# PX4FMUv2_3.net
KiCad netlist of a schematic drawn in EAGLE
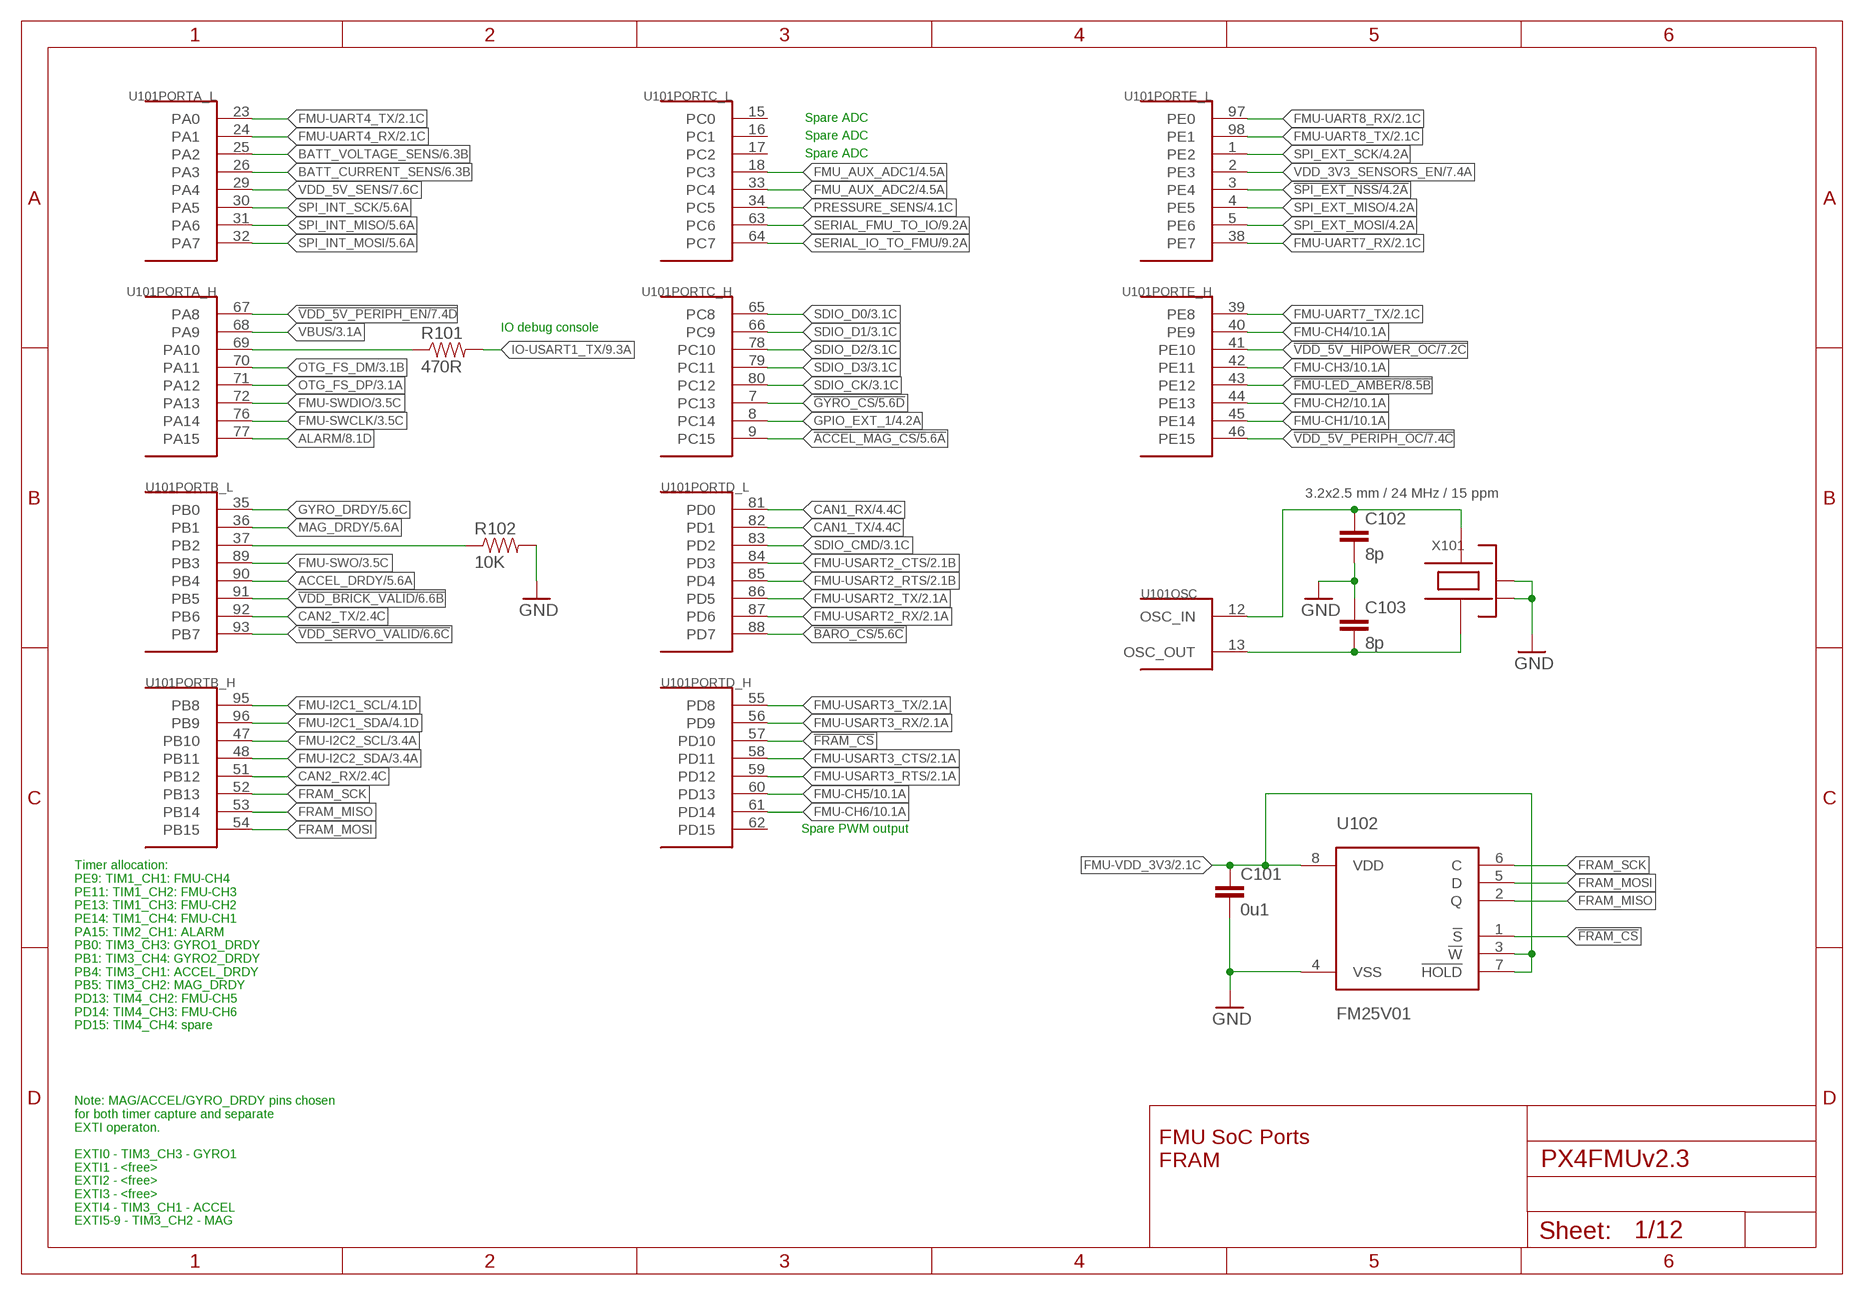
[diagram p0: schematic, sheet 1]
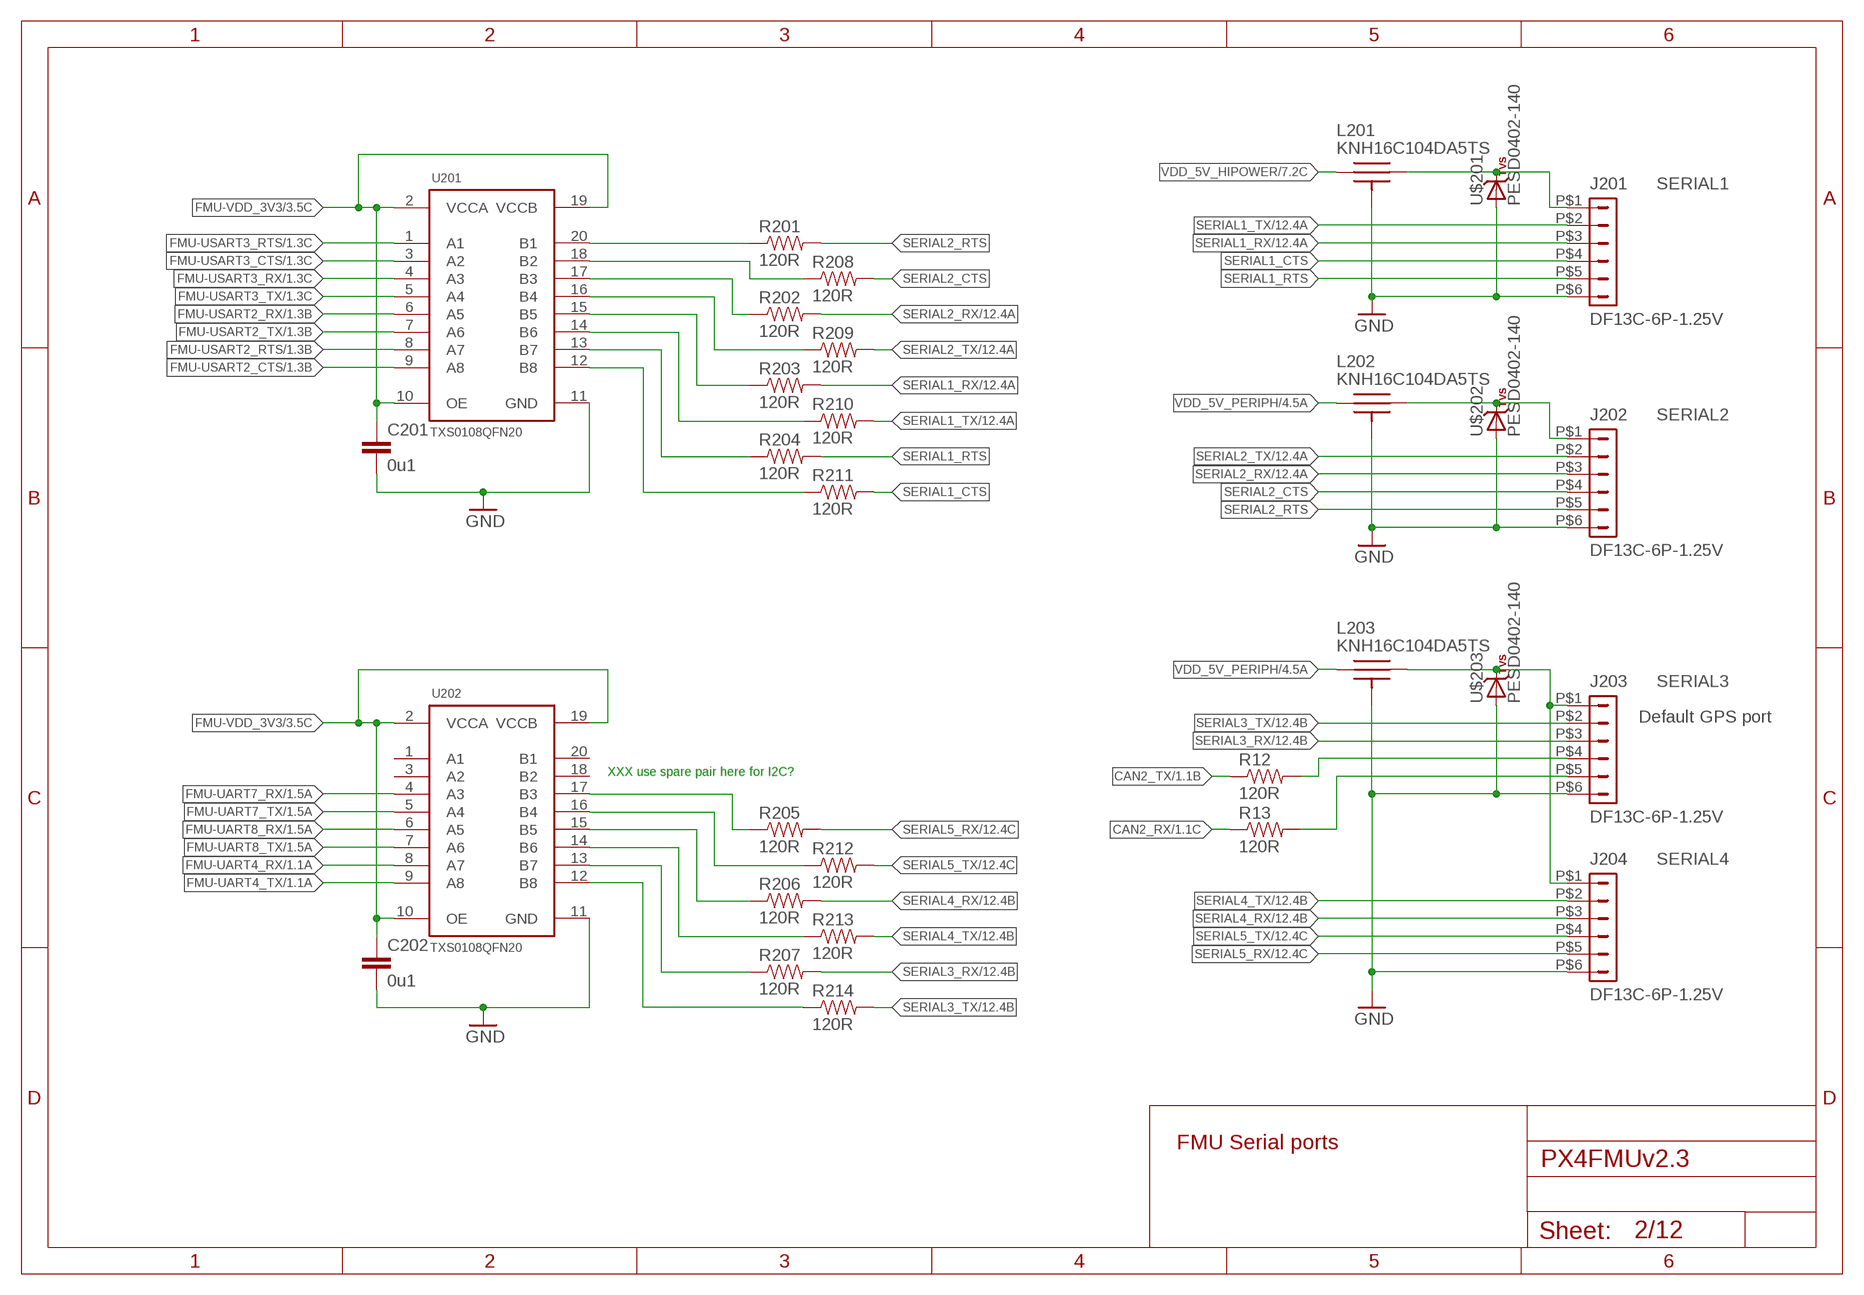
[diagram p1: schematic, sheet 2]
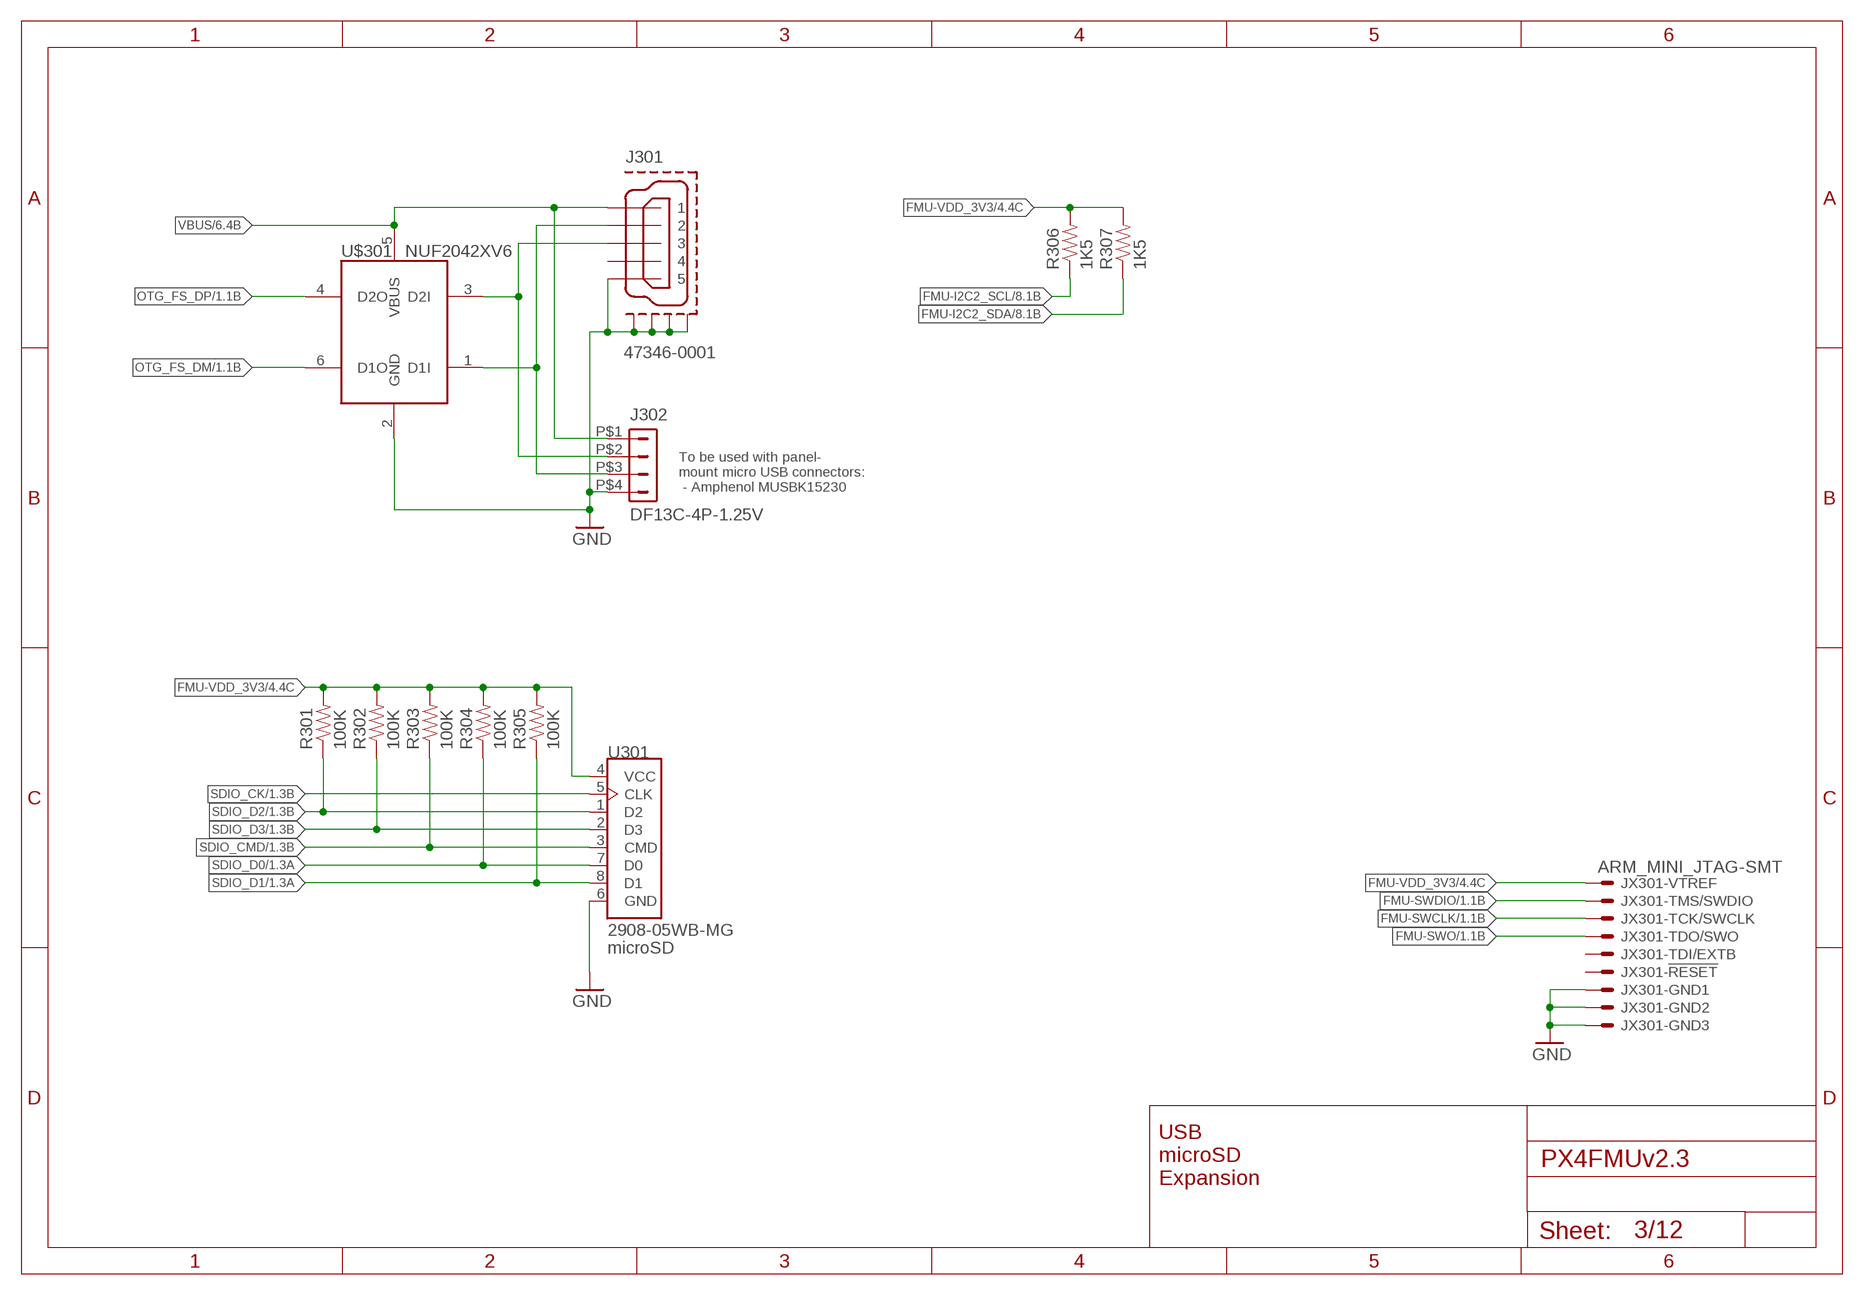
[diagram p2: schematic, sheet 3]
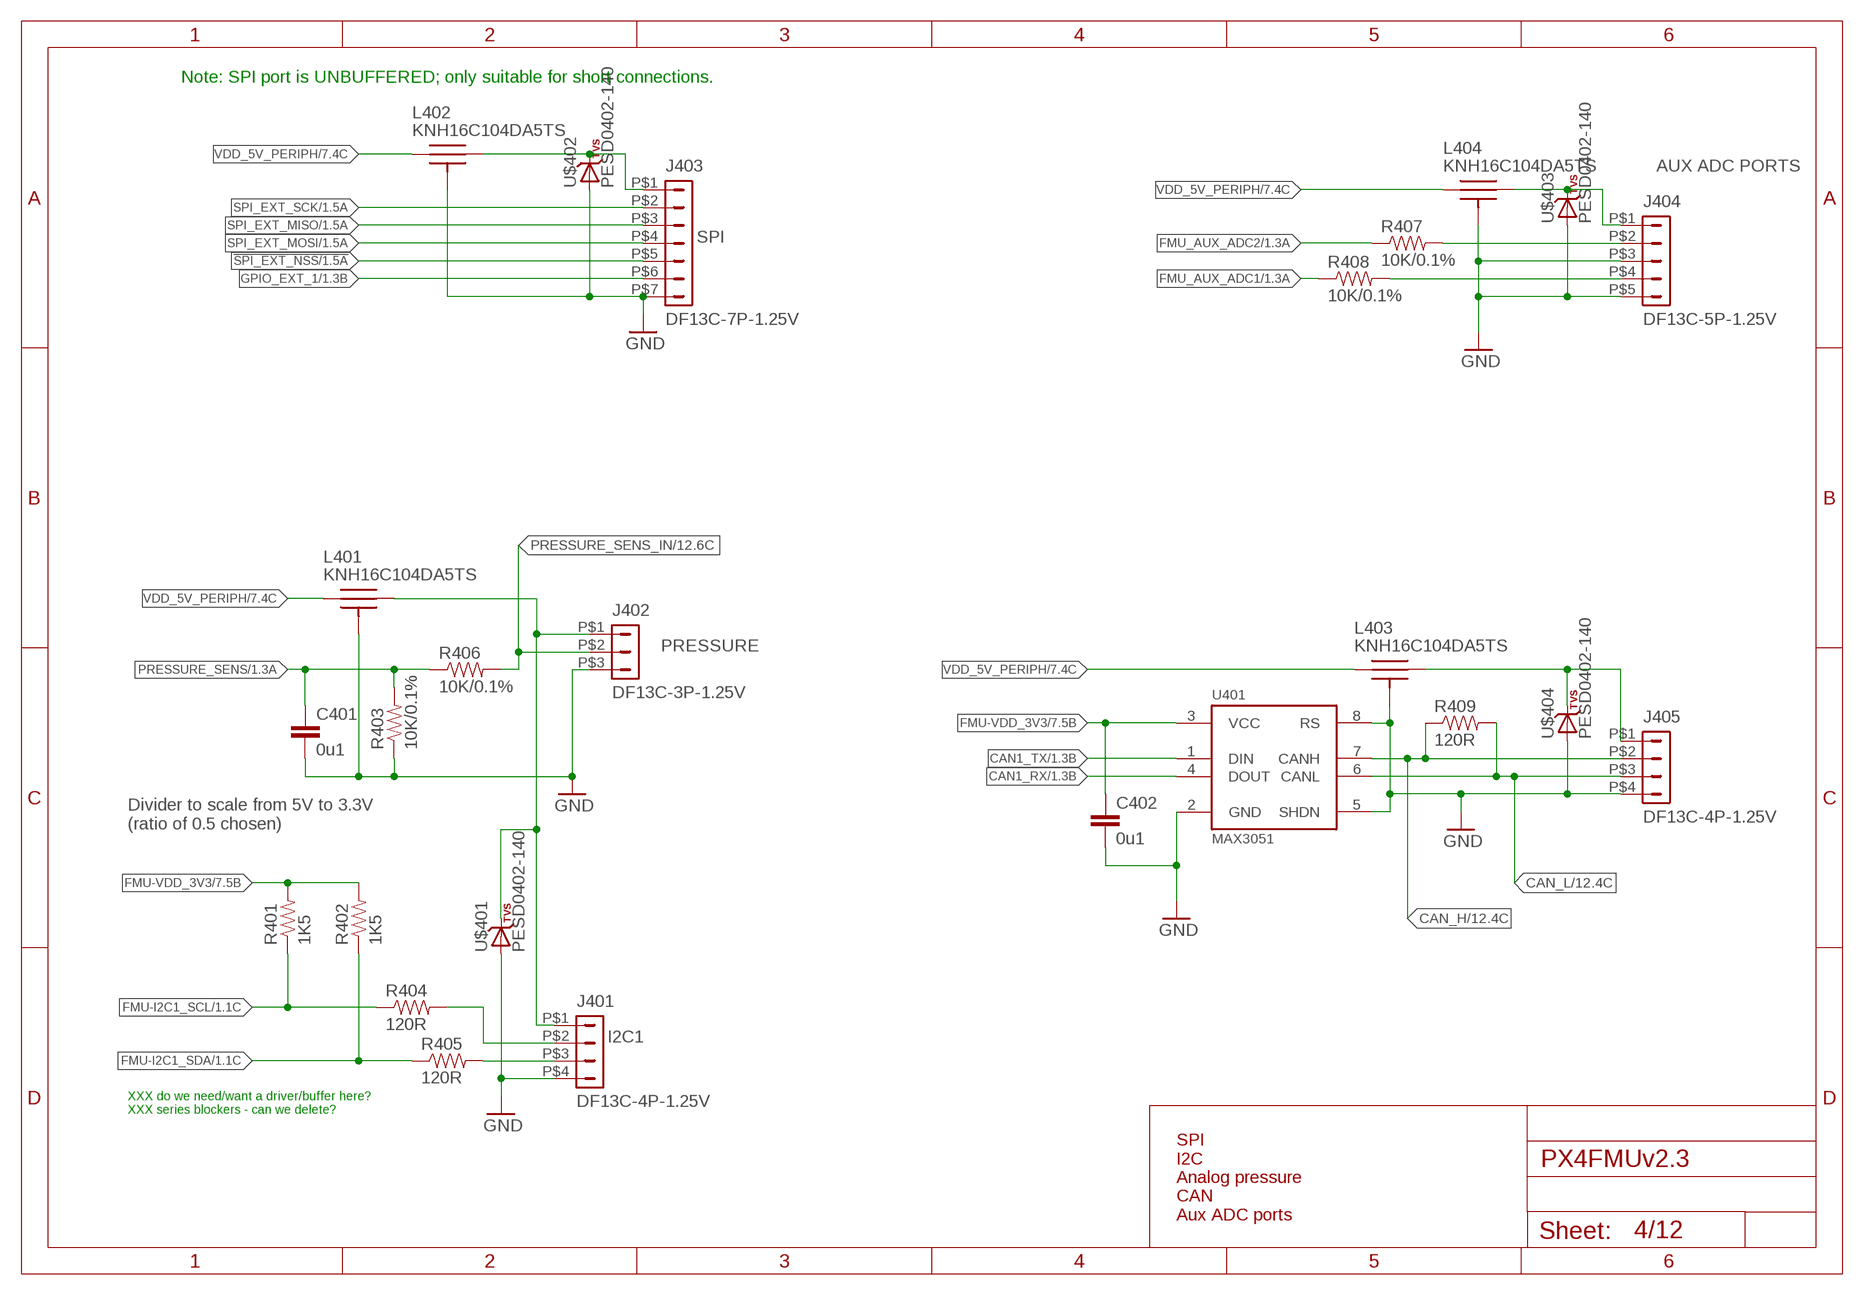
[diagram p3: schematic, sheet 4]
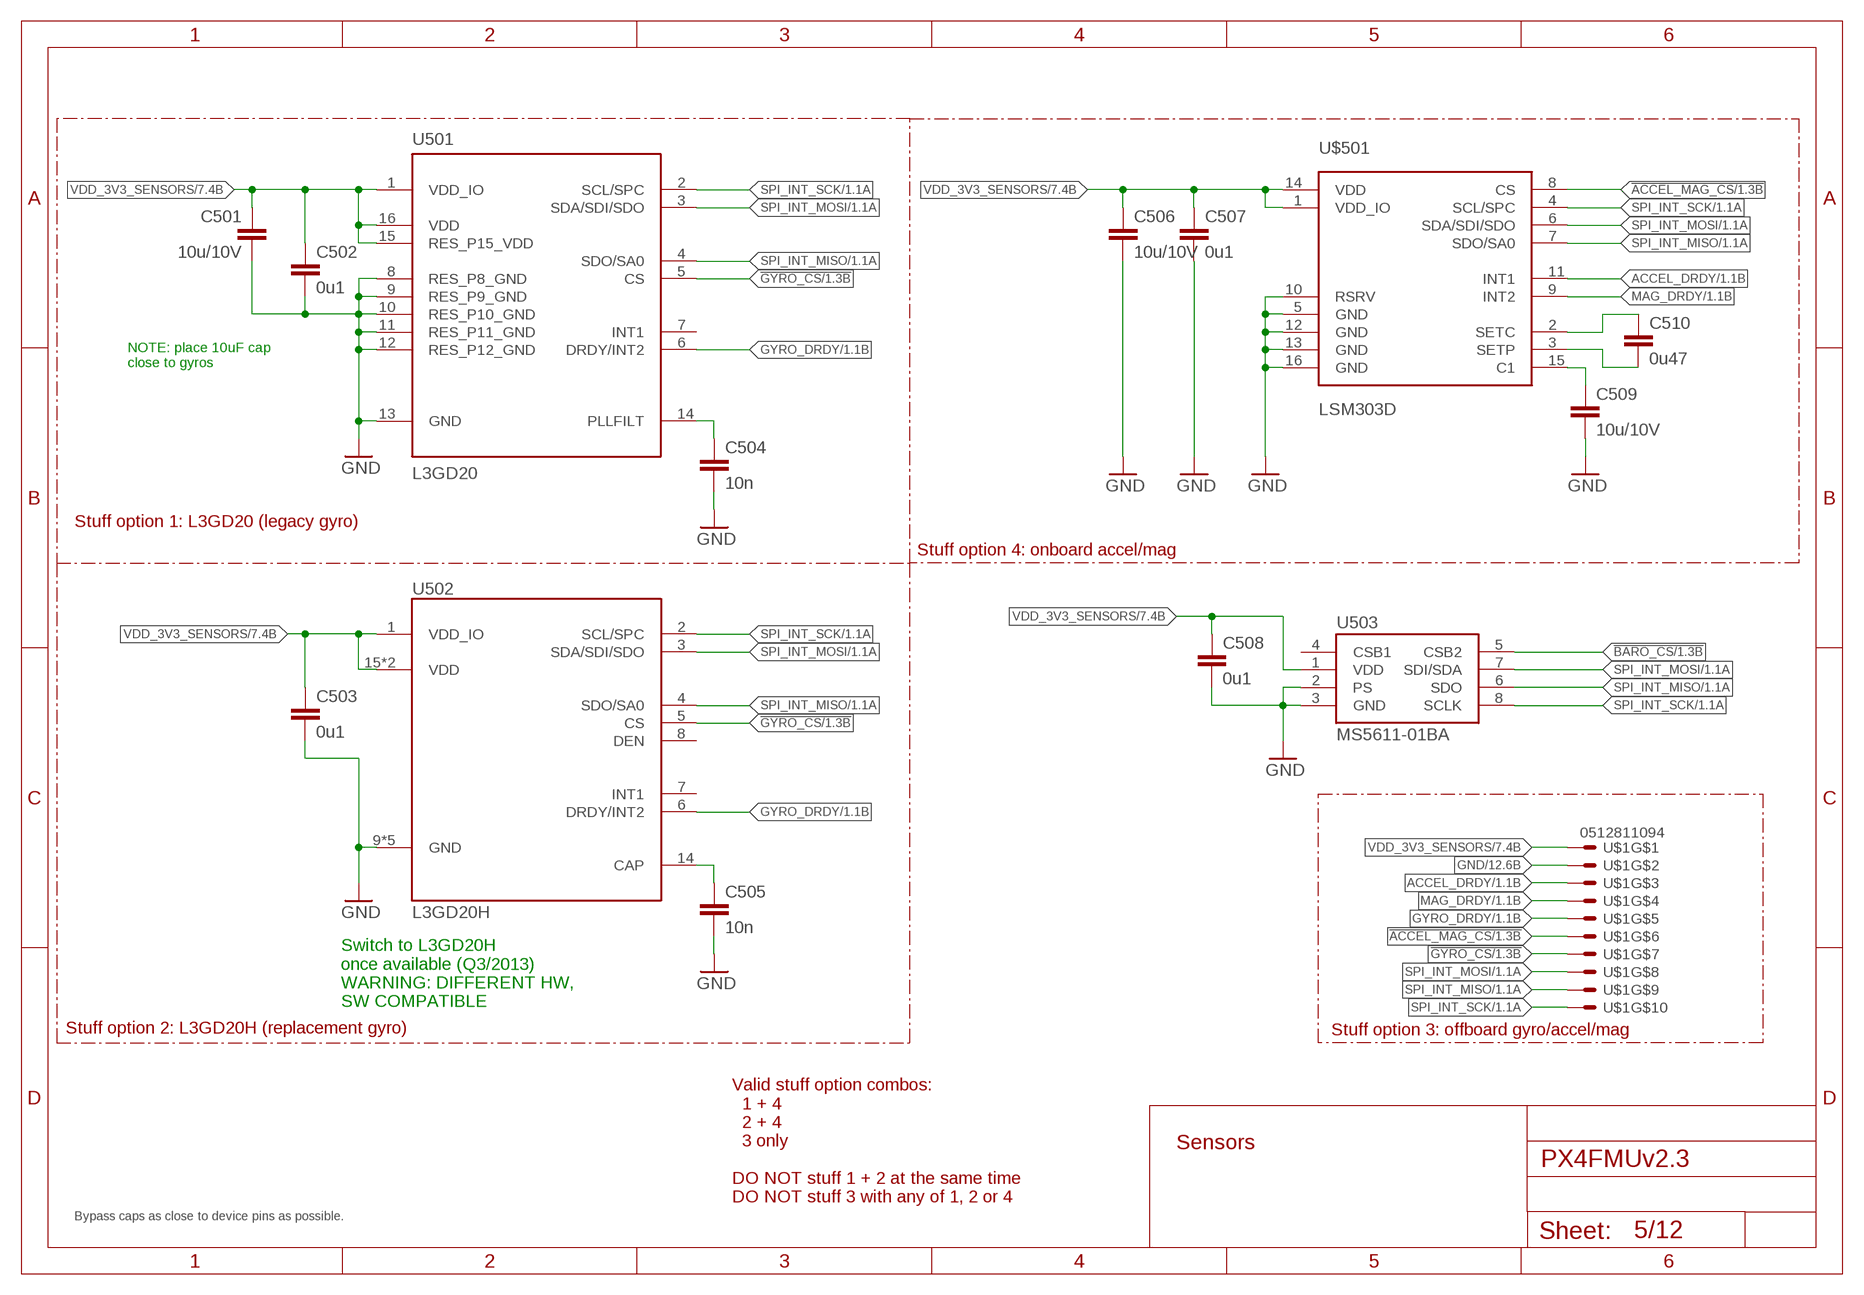
[diagram p4: schematic, sheet 5]
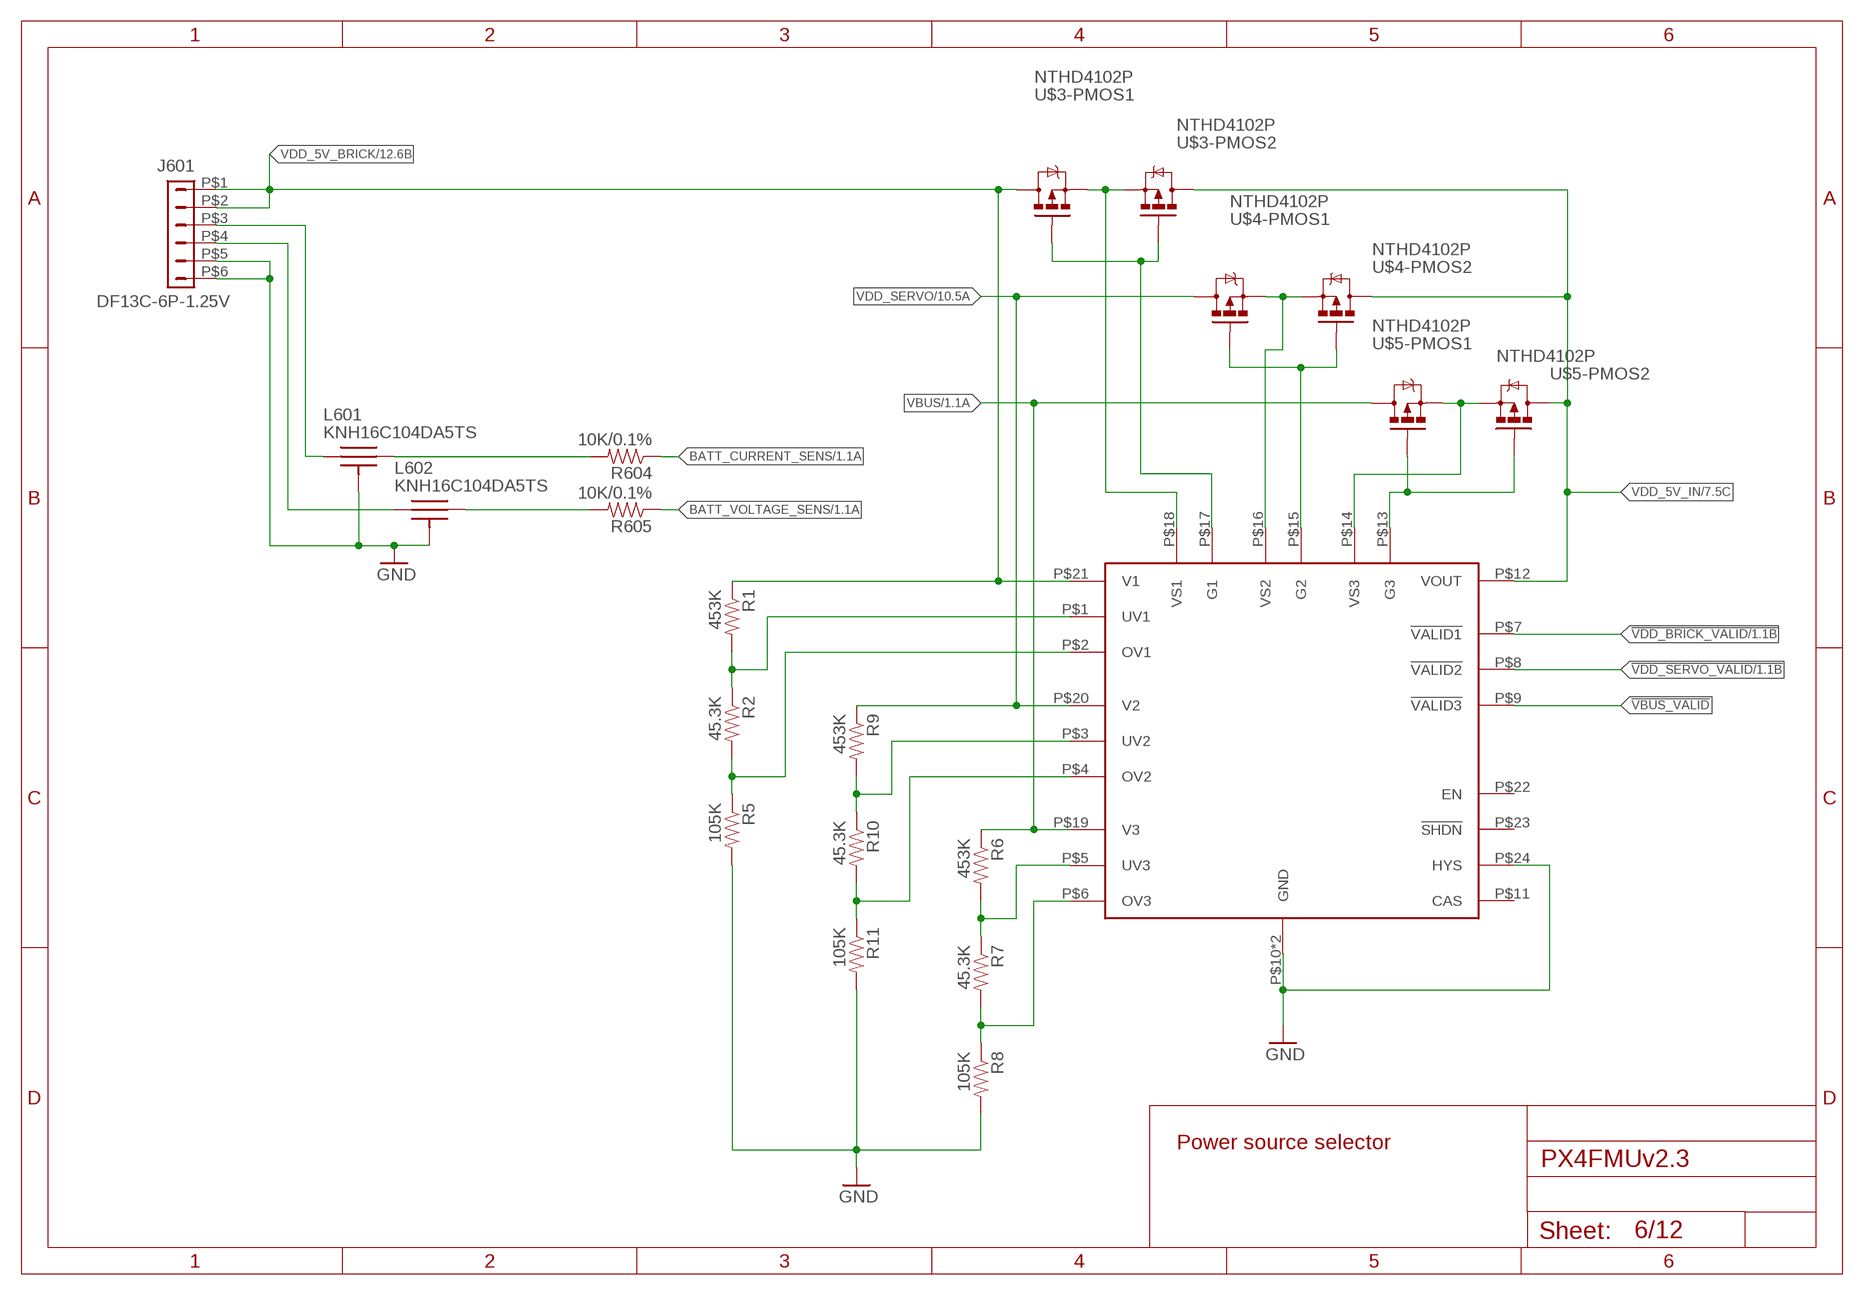
[diagram p5: schematic, sheet 6]
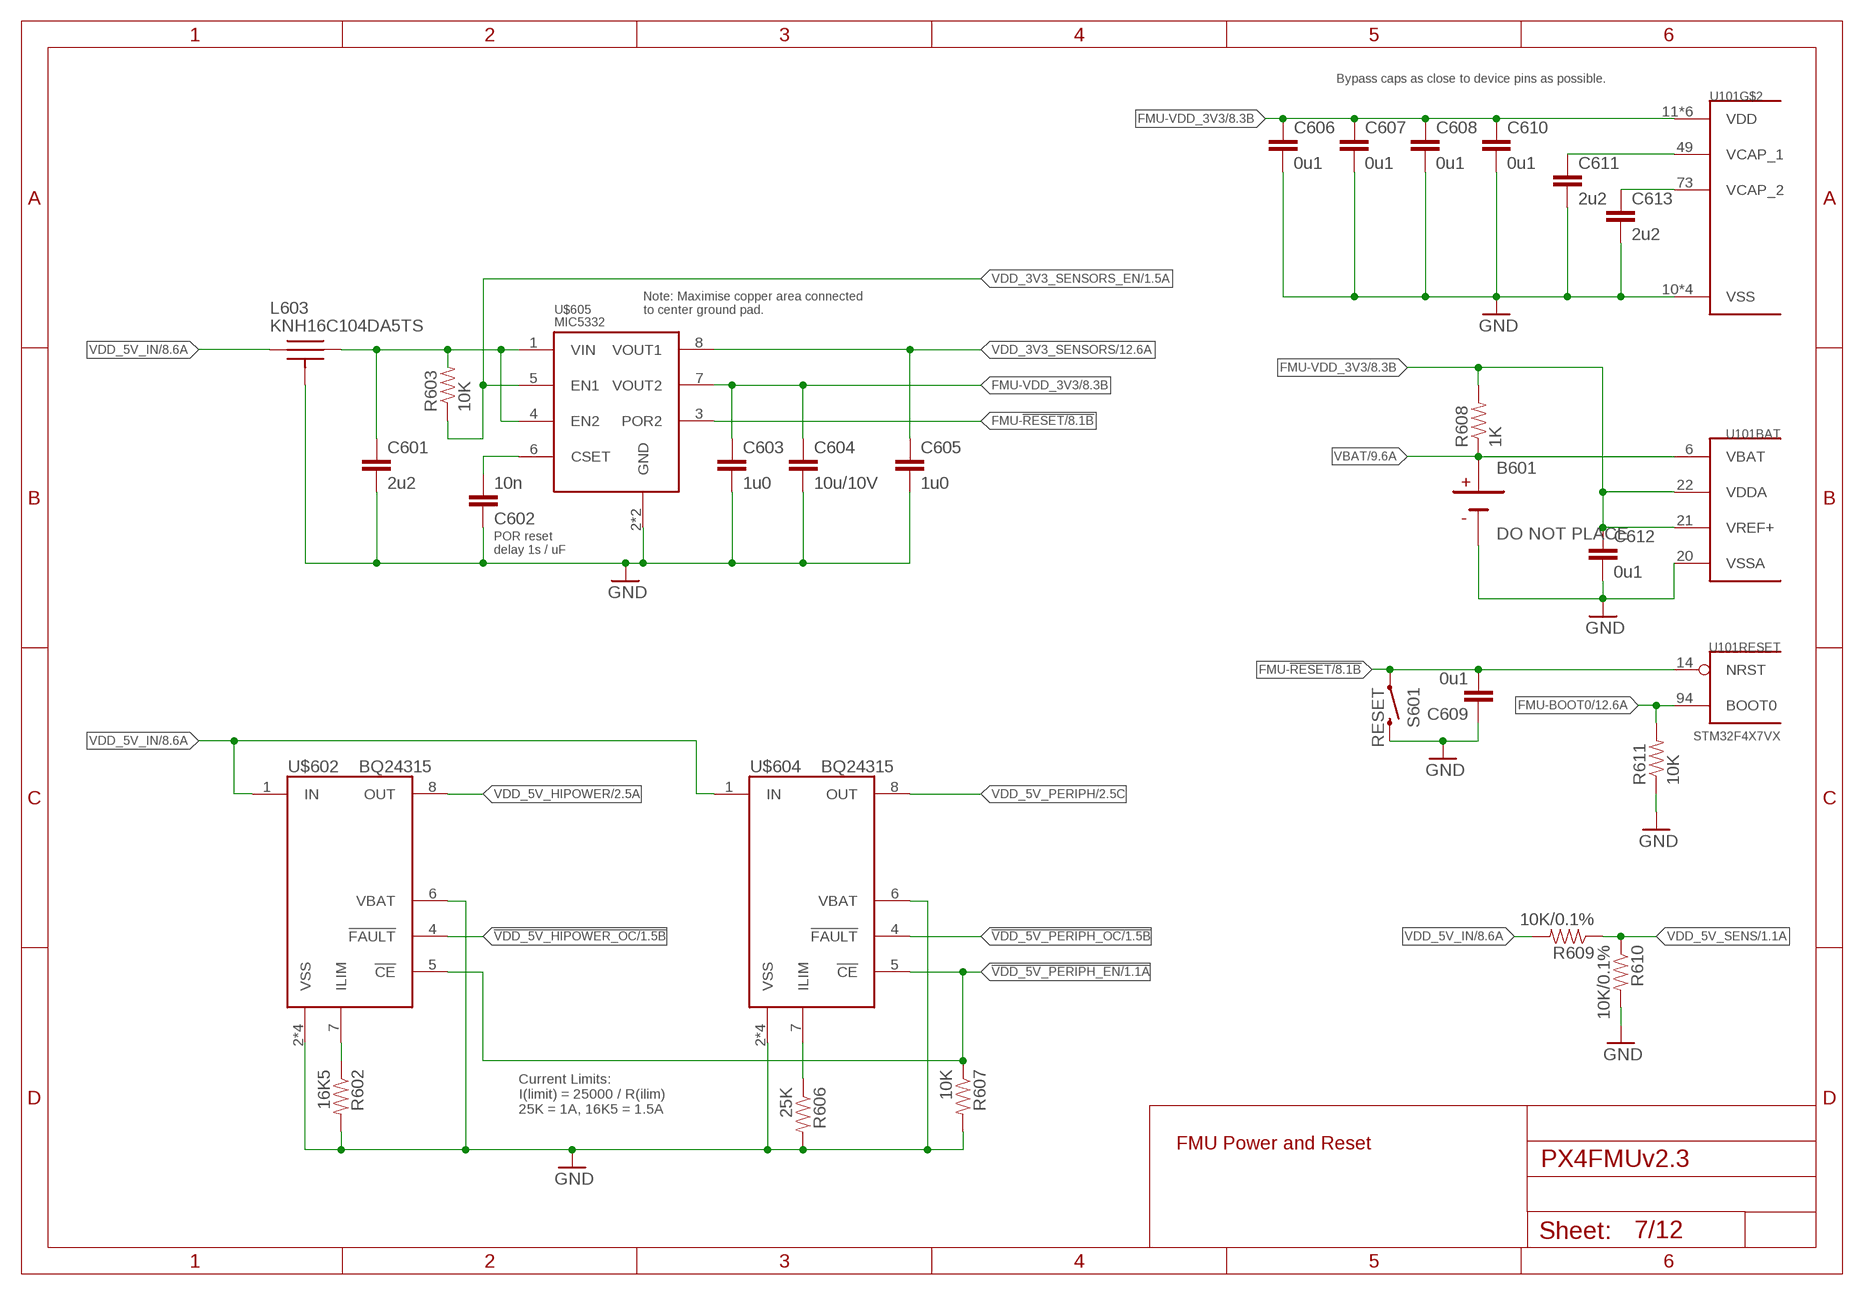
[diagram p6: schematic, sheet 7]
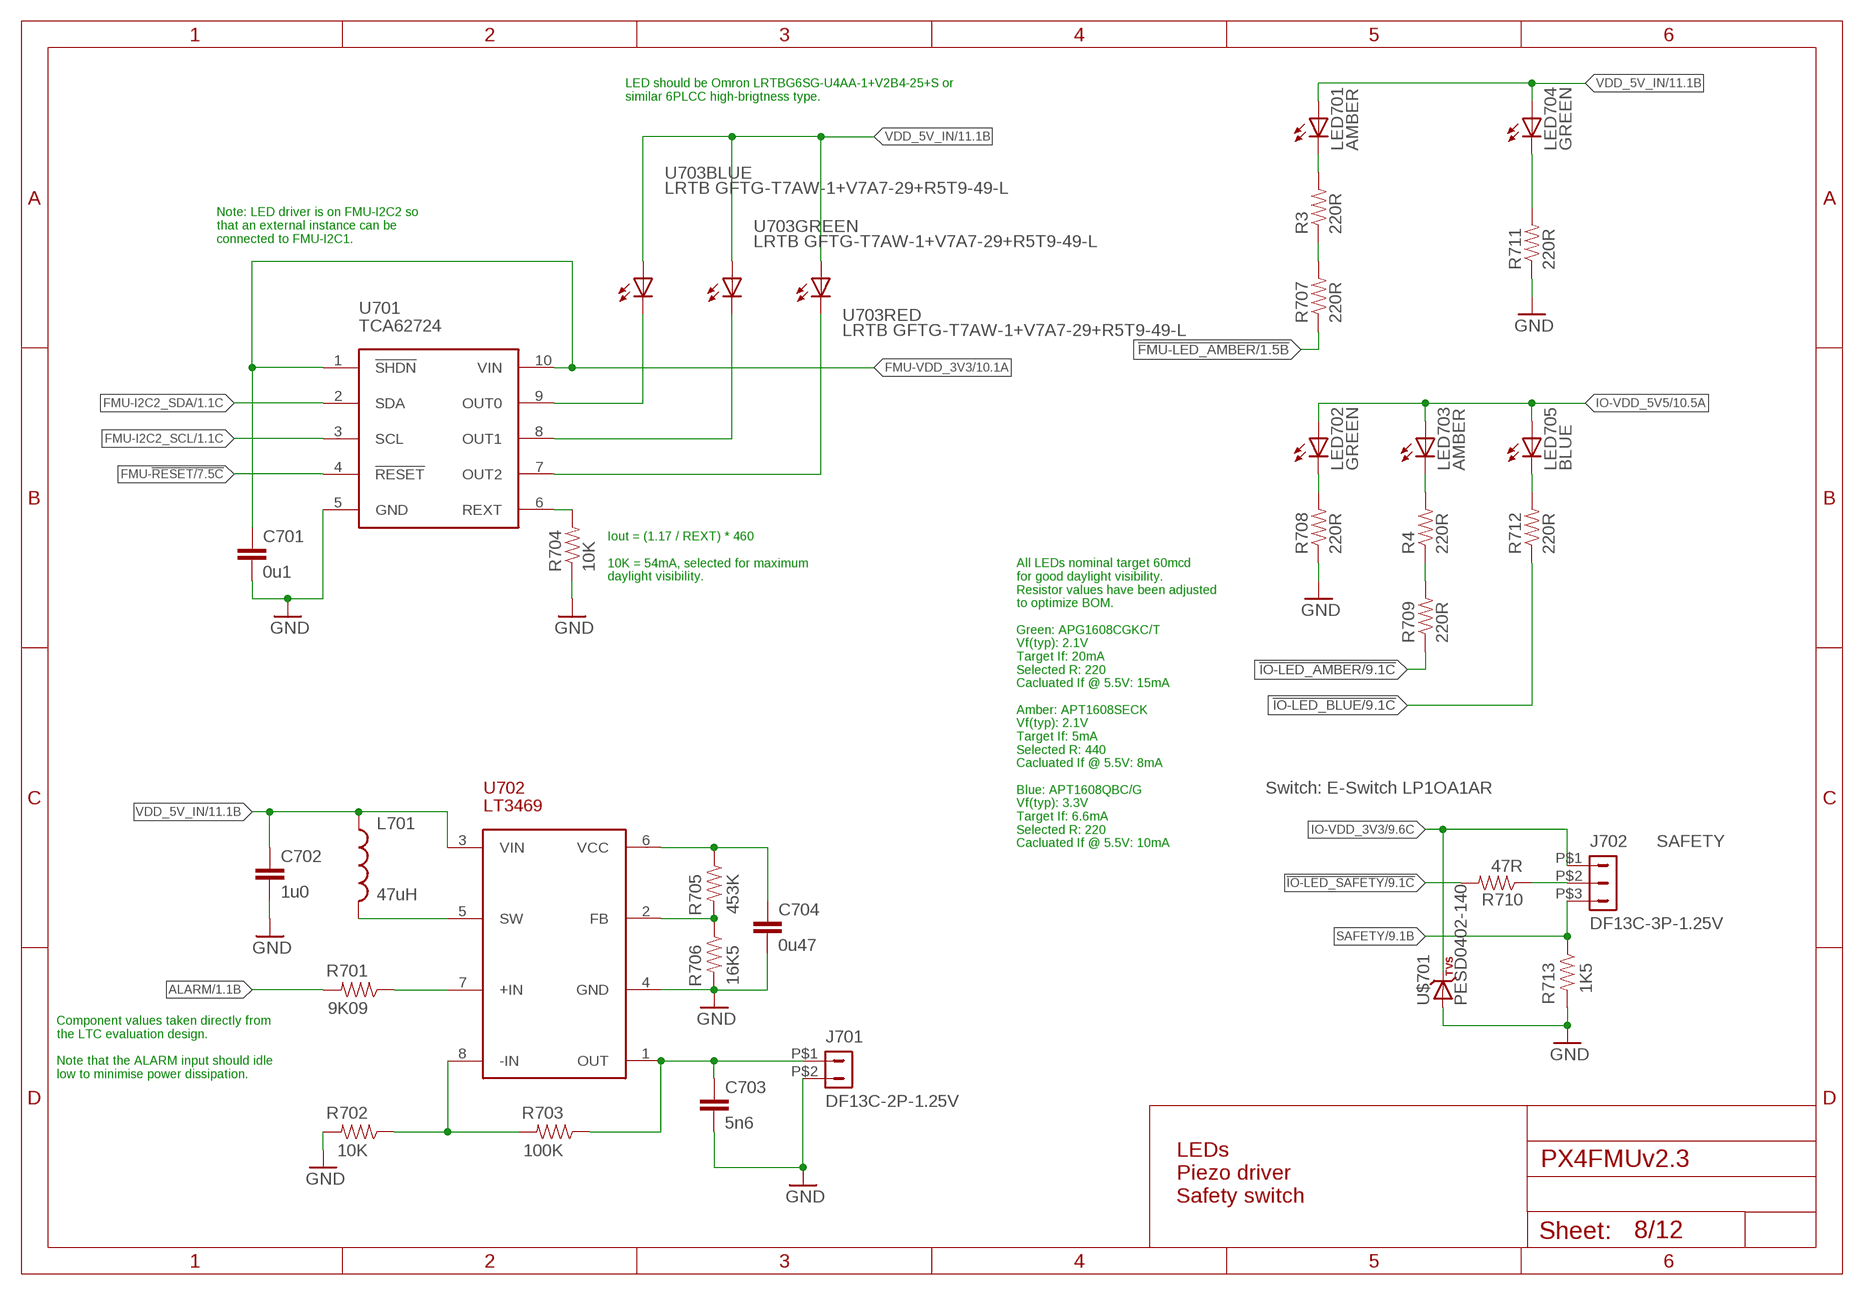
[diagram p7: schematic, sheet 8]
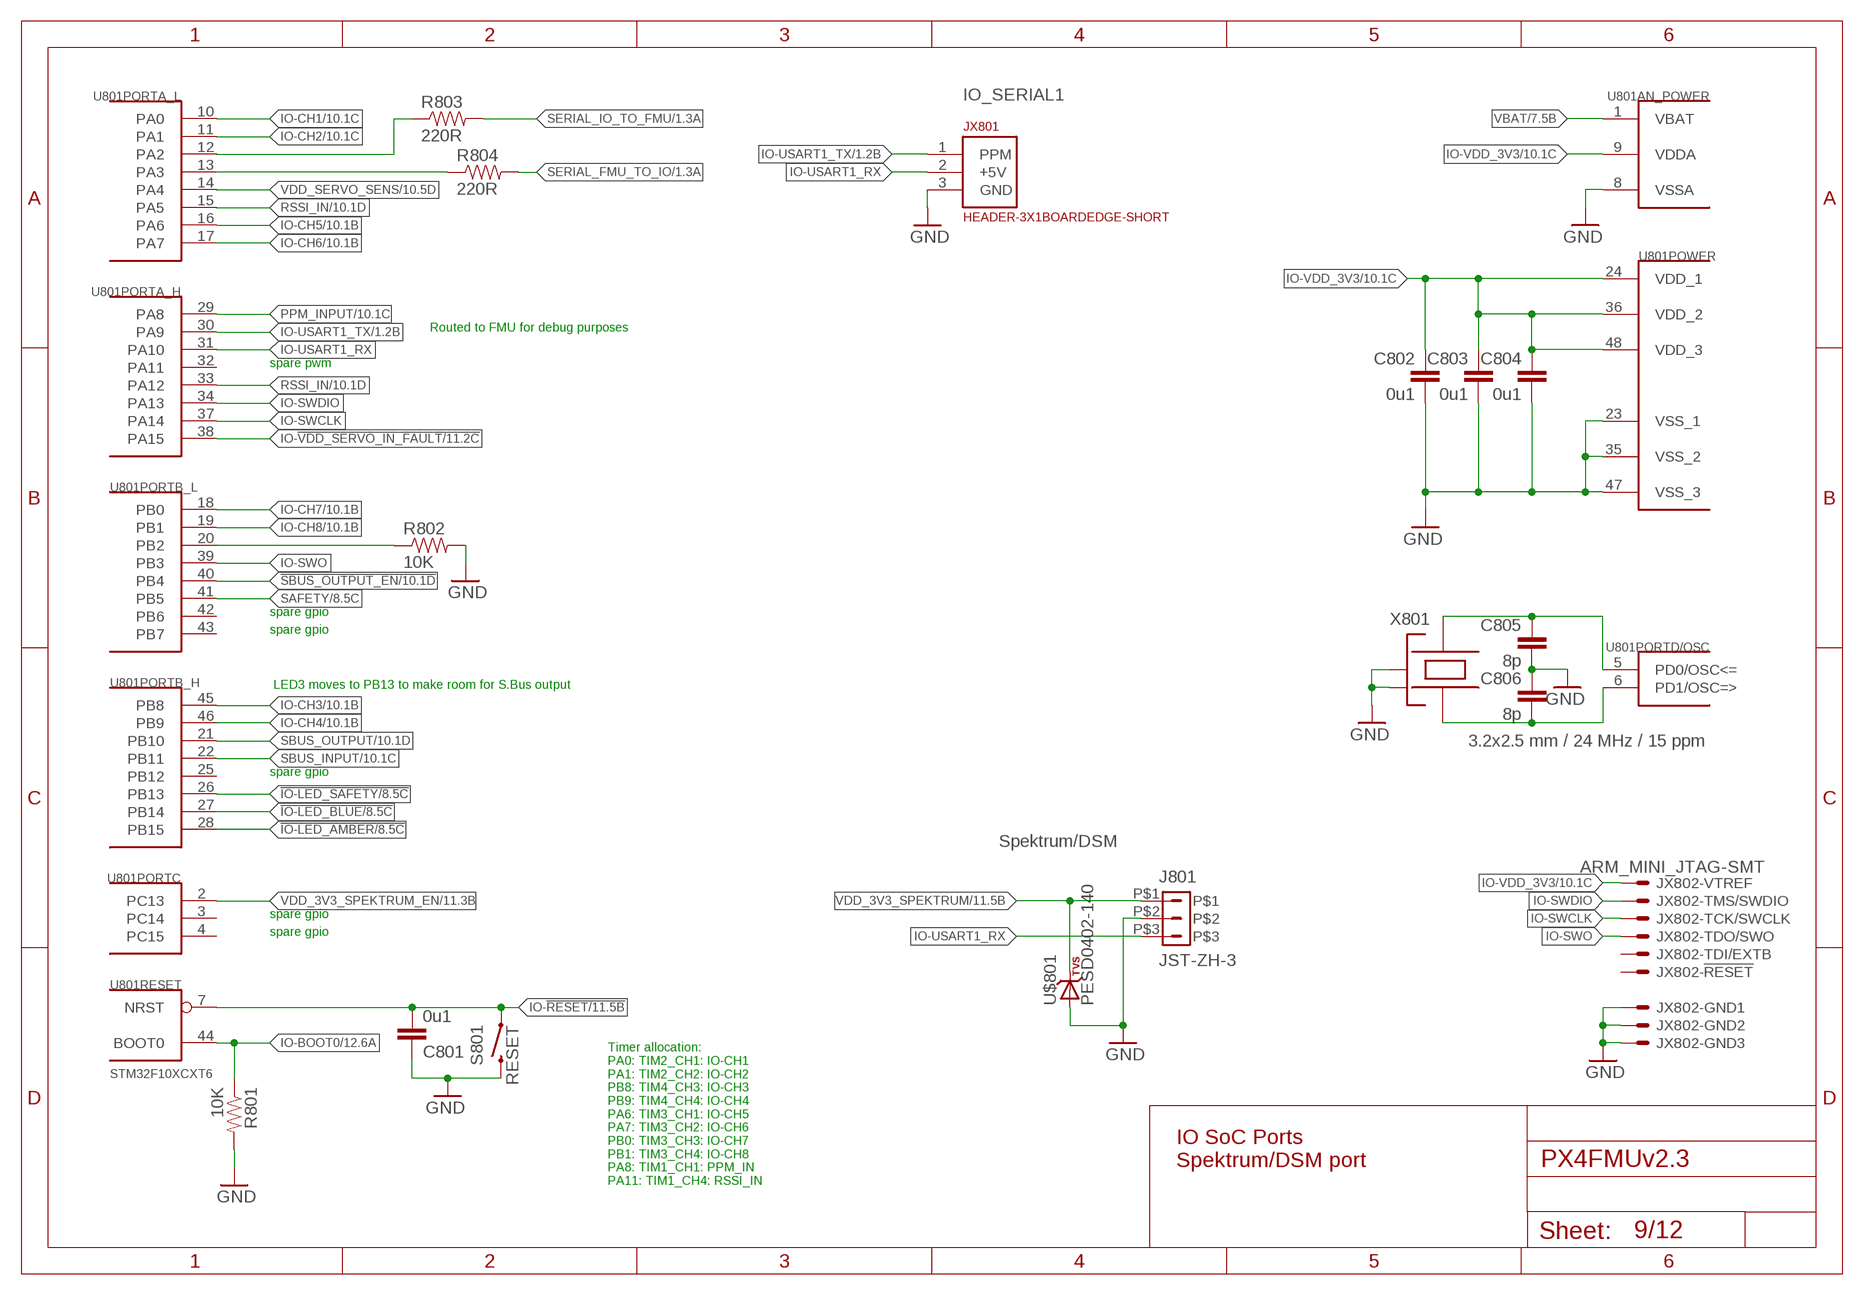
[diagram p8: schematic, sheet 9]
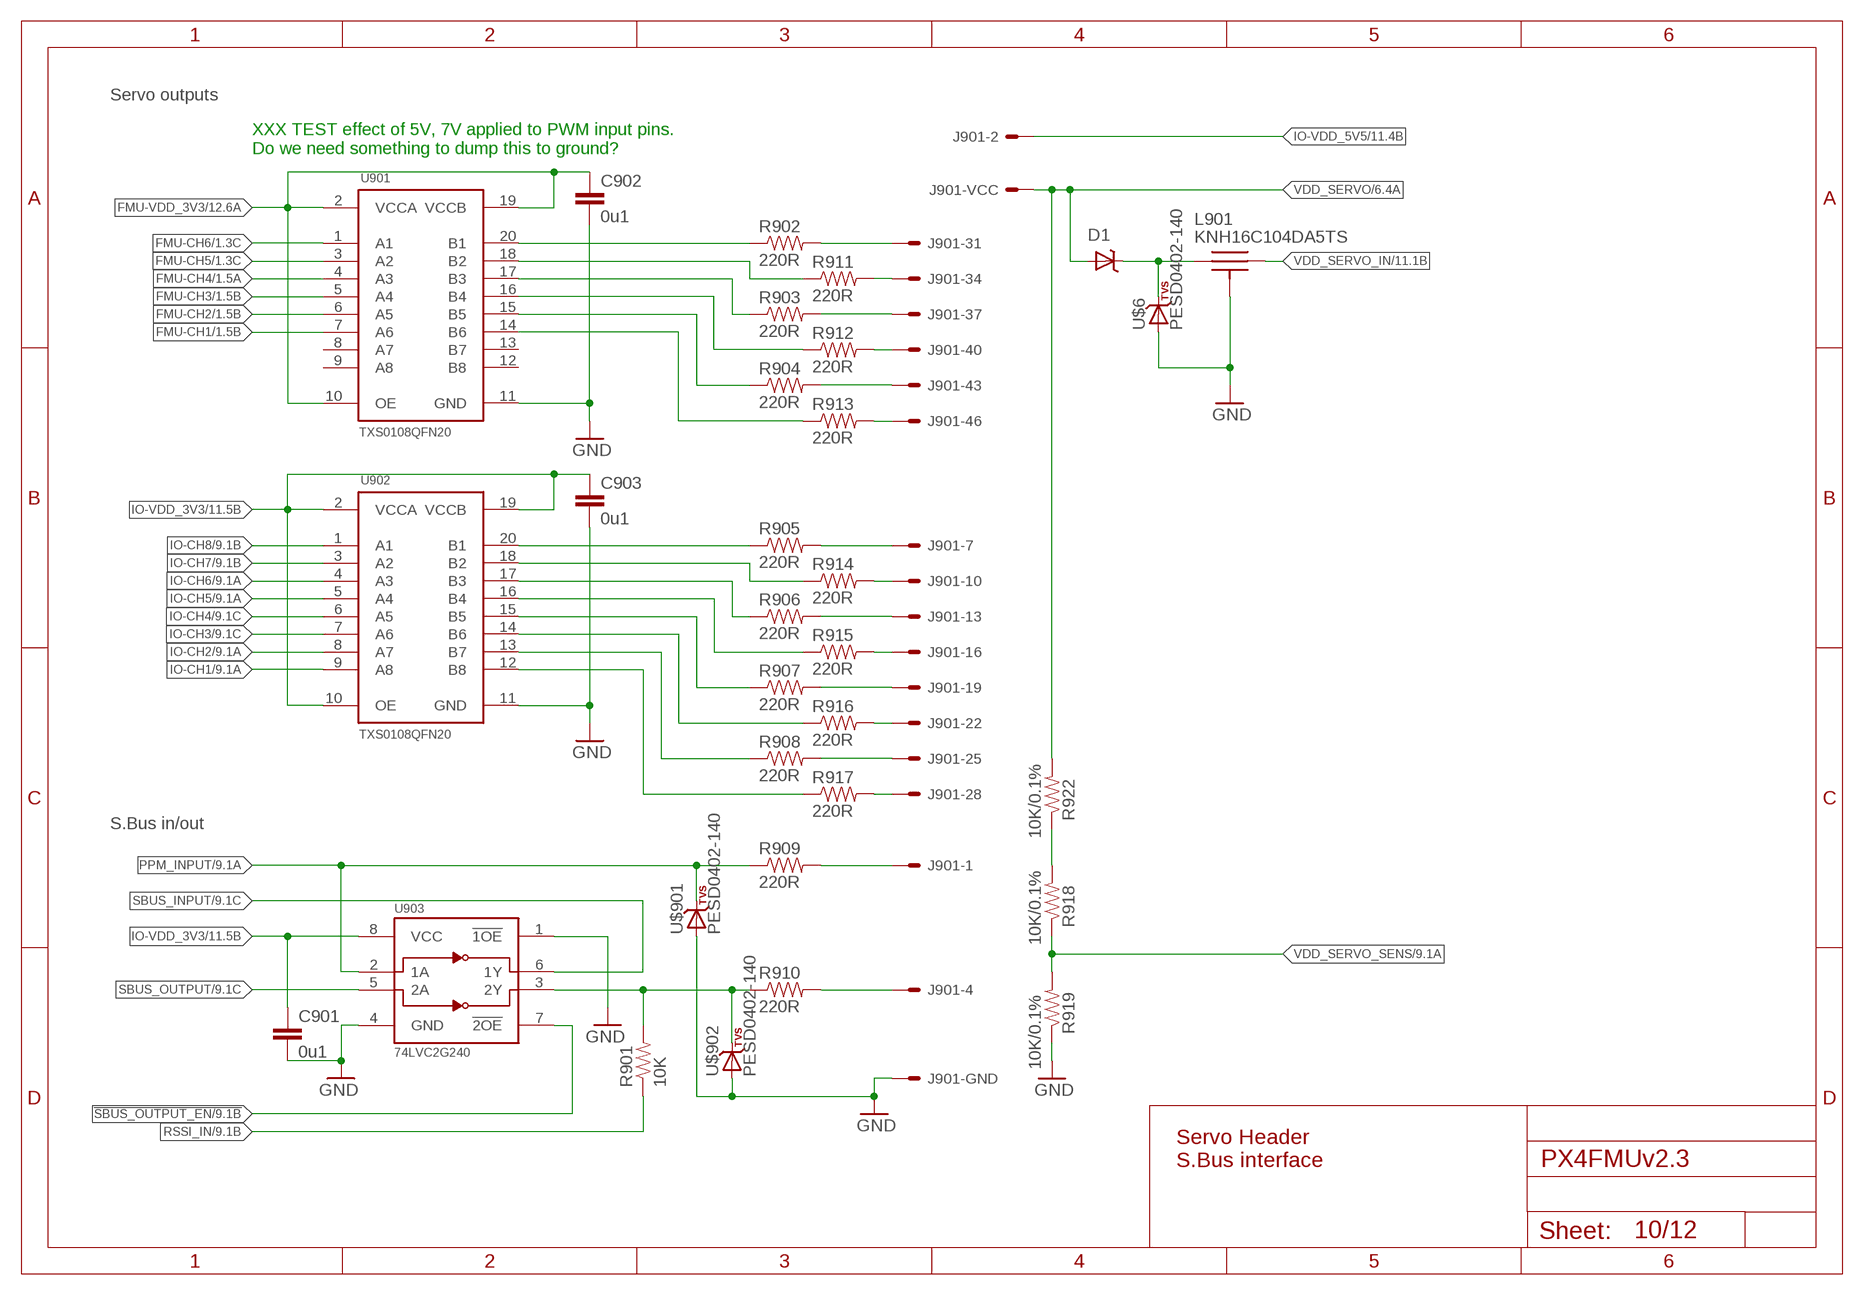
[diagram p9: schematic, sheet 10]
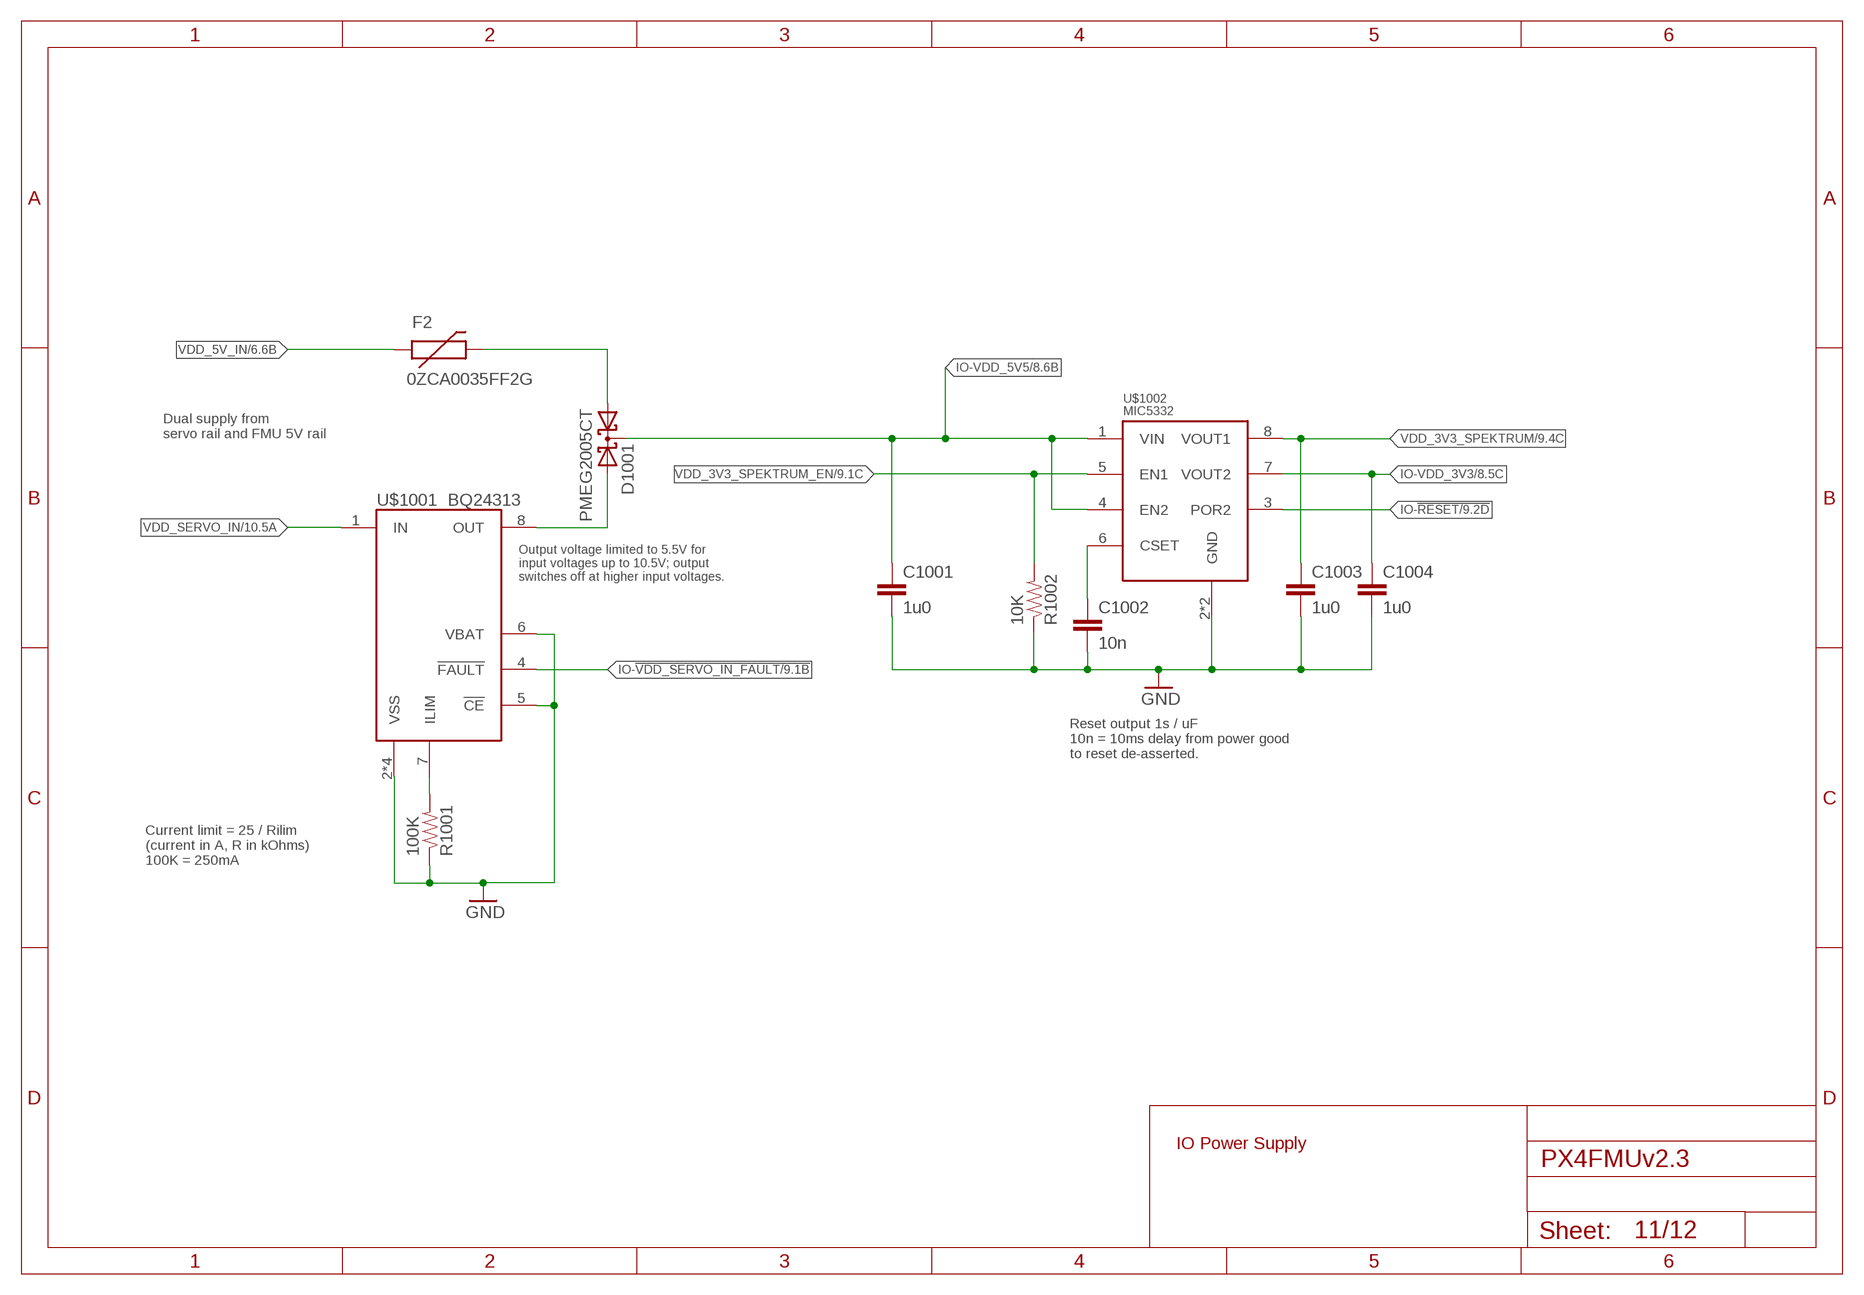
[diagram p10: schematic, sheet 11]
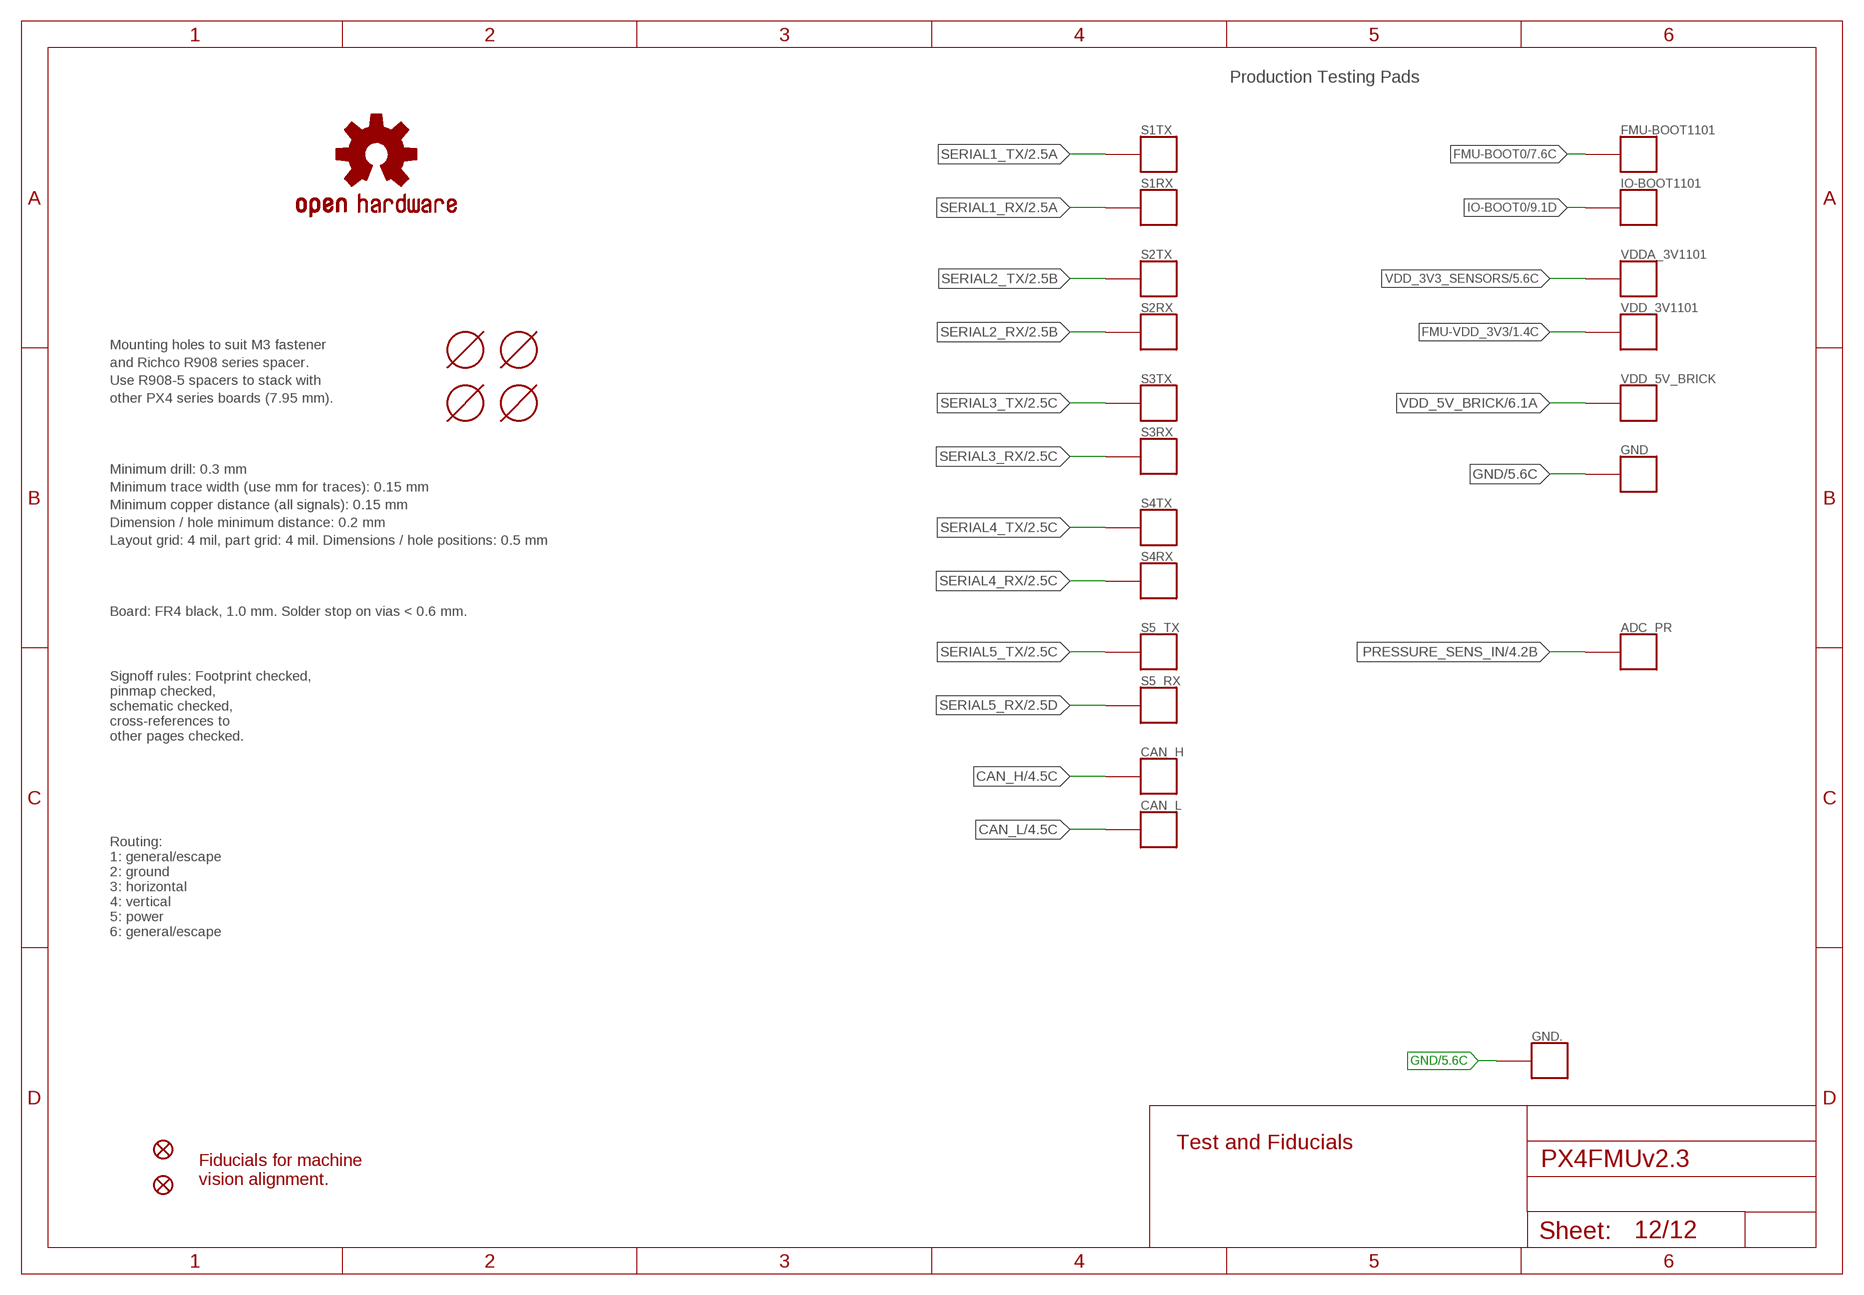
[diagram p11: schematic, sheet 12]

(export (version "E")
  (design (tool "Eeschema 10.0.6"))
  (components
    (comp (ref "C101")
      (value "0u1")
      (footprint "eagle-import:0402-CAP")
      (fields (field (name "PARTNO") "CC0402ZRY5V7BB104"))
      (libsource (lib "eagle-import") (part "CAP0402"))
    )
    (comp (ref "C102")
      (value "8p")
      (footprint "eagle-import:0402-CAP")
      (fields (field (name "PARTNO") "C1005C0G1H080C"))
      (libsource (lib "eagle-import") (part "CAP0402"))
    )
    (comp (ref "C103")
      (value "8p")
      (footprint "eagle-import:0402-CAP")
      (fields (field (name "PARTNO") "C1005C0G1H080C"))
      (libsource (lib "eagle-import") (part "CAP0402"))
    )
    (comp (ref "R101")
      (value "470R")
      (footprint "eagle-import:0402-RES")
      (fields (field (name "PARTNO") "RC0402FR-07470RL"))
      (libsource (lib "eagle-import") (part "RESISTOR0402-RES"))
    )
    (comp (ref "R102")
      (value "10K")
      (footprint "eagle-import:0402-RES")
      (fields (field (name "PARTNO") "RC0402FR-0710KL"))
      (libsource (lib "eagle-import") (part "RESISTOR0402-RES"))
    )
    (comp (ref "U101")
      (value "STM32F4X7VX")
      (footprint "eagle-import:TQFP100")
      (fields (field (name "PARTNO") "STM32F427VI"))
      (libsource (lib "eagle-import") (part "STM32F4X7VX"))
    )
    (comp (ref "U102")
      (value "FM25V01")
      (footprint "eagle-import:SO08")
      (fields (field (name "PARTNO") "FM25V01-G"))
      (libsource (lib "eagle-import") (part "FM25V01"))
    )
    (comp (ref "X101")
      (value "3.2x2.5 mm / 24 MHz / 15 ppm")
      (footprint "eagle-import:OSCILLATOR-3.2X2.5")
      (fields (field (name "PARTNO") "NX3225SA-24.000000MHZ"))
      (libsource (lib "eagle-import") (part "OSCILLATOR-3.2X2.5"))
    )
    (comp (ref "C201")
      (value "0u1")
      (footprint "eagle-import:0402-CAP")
      (fields (field (name "PARTNO") "CC0402ZRY5V7BB104"))
      (libsource (lib "eagle-import") (part "CAP0402"))
    )
    (comp (ref "C202")
      (value "0u1")
      (footprint "eagle-import:0402-CAP")
      (fields (field (name "PARTNO") "CC0402ZRY5V7BB104"))
      (libsource (lib "eagle-import") (part "CAP0402"))
    )
    (comp (ref "J201")
      (value "DF13C-6P-1.25V")
      (footprint "eagle-import:DF13C-6P-1.25V")
      (fields (field (name "PARTNO") "DF13C-6P-1.25V(20)"))
      (libsource (lib "eagle-import") (part "DF13-6P-1.25V"))
    )
    (comp (ref "J202")
      (value "DF13C-6P-1.25V")
      (footprint "eagle-import:DF13C-6P-1.25V")
      (fields (field (name "PARTNO") "DF13C-6P-1.25V(20)"))
      (libsource (lib "eagle-import") (part "DF13-6P-1.25V"))
    )
    (comp (ref "J203")
      (value "DF13C-6P-1.25V")
      (footprint "eagle-import:DF13C-6P-1.25V")
      (fields (field (name "PARTNO") "DF13C-6P-1.25V(20)"))
      (libsource (lib "eagle-import") (part "DF13-6P-1.25V"))
    )
    (comp (ref "J204")
      (value "DF13C-6P-1.25V")
      (footprint "eagle-import:DF13C-6P-1.25V")
      (fields (field (name "PARTNO") "DF13C-6P-1.25V(20)"))
      (libsource (lib "eagle-import") (part "DF13-6P-1.25V"))
    )
    (comp (ref "L201")
      (value "KNH16C104DA5TS")
      (footprint "eagle-import:KYOCERA-KNH16-DA")
      (libsource (lib "eagle-import") (part "KNH16C104DA5TS"))
    )
    (comp (ref "L202")
      (value "KNH16C104DA5TS")
      (footprint "eagle-import:KYOCERA-KNH16-DA")
      (libsource (lib "eagle-import") (part "KNH16C104DA5TS"))
    )
    (comp (ref "L203")
      (value "KNH16C104DA5TS")
      (footprint "eagle-import:KYOCERA-KNH16-DA")
      (libsource (lib "eagle-import") (part "KNH16C104DA5TS"))
    )
    (comp (ref "R12")
      (value "120R")
      (footprint "eagle-import:0402-RES")
      (fields (field (name "PARTNO") "RC0402FR-07120RL"))
      (libsource (lib "eagle-import") (part "RESISTOR0402-RES"))
    )
    (comp (ref "R13")
      (value "120R")
      (footprint "eagle-import:0402-RES")
      (fields (field (name "PARTNO") "RC0402FR-07120RL"))
      (libsource (lib "eagle-import") (part "RESISTOR0402-RES"))
    )
    (comp (ref "R201")
      (value "120R")
      (footprint "eagle-import:0402-RES")
      (fields (field (name "PARTNO") "RC0402FR-07120RL"))
      (libsource (lib "eagle-import") (part "RESISTOR0402-RES"))
    )
    (comp (ref "R202")
      (value "120R")
      (footprint "eagle-import:0402-RES")
      (fields (field (name "PARTNO") "RC0402FR-07120RL"))
      (libsource (lib "eagle-import") (part "RESISTOR0402-RES"))
    )
    (comp (ref "R203")
      (value "120R")
      (footprint "eagle-import:0402-RES")
      (fields (field (name "PARTNO") "RC0402FR-07120RL"))
      (libsource (lib "eagle-import") (part "RESISTOR0402-RES"))
    )
    (comp (ref "R204")
      (value "120R")
      (footprint "eagle-import:0402-RES")
      (fields (field (name "PARTNO") "RC0402FR-07120RL"))
      (libsource (lib "eagle-import") (part "RESISTOR0402-RES"))
    )
    (comp (ref "R205")
      (value "120R")
      (footprint "eagle-import:0402-RES")
      (fields (field (name "PARTNO") "RC0402FR-07120RL"))
      (libsource (lib "eagle-import") (part "RESISTOR0402-RES"))
    )
    (comp (ref "R206")
      (value "120R")
      (footprint "eagle-import:0402-RES")
      (fields (field (name "PARTNO") "RC0402FR-07120RL"))
      (libsource (lib "eagle-import") (part "RESISTOR0402-RES"))
    )
    (comp (ref "R207")
      (value "120R")
      (footprint "eagle-import:0402-RES")
      (fields (field (name "PARTNO") "RC0402FR-07120RL"))
      (libsource (lib "eagle-import") (part "RESISTOR0402-RES"))
    )
    (comp (ref "R208")
      (value "120R")
      (footprint "eagle-import:0402-RES")
      (fields (field (name "PARTNO") "RC0402FR-07120RL"))
      (libsource (lib "eagle-import") (part "RESISTOR0402-RES"))
    )
    (comp (ref "R209")
      (value "120R")
      (footprint "eagle-import:0402-RES")
      (fields (field (name "PARTNO") "RC0402FR-07120RL"))
      (libsource (lib "eagle-import") (part "RESISTOR0402-RES"))
    )
    (comp (ref "R210")
      (value "120R")
      (footprint "eagle-import:0402-RES")
      (fields (field (name "PARTNO") "RC0402FR-07120RL"))
      (libsource (lib "eagle-import") (part "RESISTOR0402-RES"))
    )
    (comp (ref "R211")
      (value "120R")
      (footprint "eagle-import:0402-RES")
      (fields (field (name "PARTNO") "RC0402FR-07120RL"))
      (libsource (lib "eagle-import") (part "RESISTOR0402-RES"))
    )
    (comp (ref "R212")
      (value "120R")
      (footprint "eagle-import:0402-RES")
      (fields (field (name "PARTNO") "RC0402FR-07120RL"))
      (libsource (lib "eagle-import") (part "RESISTOR0402-RES"))
    )
    (comp (ref "R213")
      (value "120R")
      (footprint "eagle-import:0402-RES")
      (fields (field (name "PARTNO") "RC0402FR-07120RL"))
      (libsource (lib "eagle-import") (part "RESISTOR0402-RES"))
    )
    (comp (ref "R214")
      (value "120R")
      (footprint "eagle-import:0402-RES")
      (fields (field (name "PARTNO") "RC0402FR-07120RL"))
      (libsource (lib "eagle-import") (part "RESISTOR0402-RES"))
    )
    (comp (ref "U$201")
      (value "PESD0402-140")
      (footprint "eagle-import:0402-TVS")
      (libsource (lib "eagle-import") (part "DIODE-TVS"))
    )
    (comp (ref "U$202")
      (value "PESD0402-140")
      (footprint "eagle-import:0402-TVS")
      (libsource (lib "eagle-import") (part "DIODE-TVS"))
    )
    (comp (ref "U$203")
      (value "PESD0402-140")
      (footprint "eagle-import:0402-TVS")
      (libsource (lib "eagle-import") (part "DIODE-TVS"))
    )
    (comp (ref "U201")
      (value "TXS0108QFN20")
      (footprint "eagle-import:QFN20-RGY")
      (fields (field (name "PARTNO") "TXS0108ERGYR"))
      (libsource (lib "eagle-import") (part "TXS0108QFN20"))
    )
    (comp (ref "U202")
      (value "TXS0108QFN20")
      (footprint "eagle-import:QFN20-RGY")
      (fields (field (name "PARTNO") "TXS0108ERGYR"))
      (libsource (lib "eagle-import") (part "TXS0108QFN20"))
    )
    (comp (ref "ADC_PR")
      (value "PAD.04")
      (footprint "eagle-import:PAD.04X.04")
      (libsource (lib "eagle-import") (part "PAD.04"))
    )
    (comp (ref "CAN_H")
      (value "PAD.04")
      (footprint "eagle-import:PAD.04X.04")
      (libsource (lib "eagle-import") (part "PAD.04"))
    )
    (comp (ref "CAN_L")
      (value "PAD.04")
      (footprint "eagle-import:PAD.04X.04")
      (libsource (lib "eagle-import") (part "PAD.04"))
    )
    (comp (ref "FMU-BOOT1101")
      (value "PAD.04")
      (footprint "eagle-import:PAD.04X.04")
      (libsource (lib "eagle-import") (part "PAD.04"))
    )
    (comp (ref "GND")
      (value "PAD.04")
      (footprint "eagle-import:PAD.04X.04")
      (libsource (lib "eagle-import") (part "PAD.04"))
    )
    (comp (ref "GND.")
      (value "PAD.04")
      (footprint "eagle-import:PAD.04X.04")
      (libsource (lib "eagle-import") (part "PAD.04"))
    )
    (comp (ref "IO-BOOT1101")
      (value "PAD.04")
      (footprint "eagle-import:PAD.04X.04")
      (libsource (lib "eagle-import") (part "PAD.04"))
    )
    (comp (ref "JP1")
      (value "FIDUCIAL1.5X3")
      (footprint "eagle-import:FIDUCIAL-1.5X3")
      (libsource (lib "eagle-import") (part "FIDUCIAL1.5X3"))
    )
    (comp (ref "JP2")
      (value "FIDUCIAL1.5X3")
      (footprint "eagle-import:FIDUCIAL-1.5X3")
      (libsource (lib "eagle-import") (part "FIDUCIAL1.5X3"))
    )
    (comp (ref "M3_MOUNT1101")
      (value "MOUNT-HOLE3.1MM")
      (footprint "eagle-import:MOUNT-HOLE3.1")
      (libsource (lib "eagle-import") (part "MOUNT-HOLE3.1MM"))
    )
    (comp (ref "M3_MOUNT1102")
      (value "MOUNT-HOLE3.1MM")
      (footprint "eagle-import:MOUNT-HOLE3.1")
      (libsource (lib "eagle-import") (part "MOUNT-HOLE3.1MM"))
    )
    (comp (ref "M3_MOUNT1103")
      (value "MOUNT-HOLE3.1MM")
      (footprint "eagle-import:MOUNT-HOLE3.1")
      (libsource (lib "eagle-import") (part "MOUNT-HOLE3.1MM"))
    )
    (comp (ref "M3_MOUNT1104")
      (value "MOUNT-HOLE3.1MM")
      (footprint "eagle-import:MOUNT-HOLE3.1")
      (libsource (lib "eagle-import") (part "MOUNT-HOLE3.1MM"))
    )
    (comp (ref "OSHW_LOGO")
      (value "OSHW-LOGOS")
      (footprint "eagle-import:OSHW-LOGO-S")
      (libsource (lib "eagle-import") (part "OSHW-LOGOS"))
    )
    (comp (ref "S1RX")
      (value "PAD.04")
      (footprint "eagle-import:PAD.04X.04")
      (libsource (lib "eagle-import") (part "PAD.04"))
    )
    (comp (ref "S1TX")
      (value "PAD.04")
      (footprint "eagle-import:PAD.04X.04")
      (libsource (lib "eagle-import") (part "PAD.04"))
    )
    (comp (ref "S2RX")
      (value "PAD.04")
      (footprint "eagle-import:PAD.04X.04")
      (libsource (lib "eagle-import") (part "PAD.04"))
    )
    (comp (ref "S2TX")
      (value "PAD.04")
      (footprint "eagle-import:PAD.04X.04")
      (libsource (lib "eagle-import") (part "PAD.04"))
    )
    (comp (ref "S3RX")
      (value "PAD.04")
      (footprint "eagle-import:PAD.04X.04")
      (libsource (lib "eagle-import") (part "PAD.04"))
    )
    (comp (ref "S3TX")
      (value "PAD.04")
      (footprint "eagle-import:PAD.04X.04")
      (libsource (lib "eagle-import") (part "PAD.04"))
    )
    (comp (ref "S4RX")
      (value "PAD.04")
      (footprint "eagle-import:PAD.04X.04")
      (libsource (lib "eagle-import") (part "PAD.04"))
    )
    (comp (ref "S4TX")
      (value "PAD.04")
      (footprint "eagle-import:PAD.04X.04")
      (libsource (lib "eagle-import") (part "PAD.04"))
    )
    (comp (ref "S5_RX")
      (value "PAD.04")
      (footprint "eagle-import:PAD.04X.04")
      (libsource (lib "eagle-import") (part "PAD.04"))
    )
    (comp (ref "S5_TX")
      (value "PAD.04")
      (footprint "eagle-import:PAD.04X.04")
      (libsource (lib "eagle-import") (part "PAD.04"))
    )
    (comp (ref "VDDA_3V1101")
      (value "PAD.04")
      (footprint "eagle-import:PAD.04X.04")
      (libsource (lib "eagle-import") (part "PAD.04"))
    )
    (comp (ref "VDD_3V1101")
      (value "PAD.04")
      (footprint "eagle-import:PAD.04X.04")
      (libsource (lib "eagle-import") (part "PAD.04"))
    )
    (comp (ref "VDD_5V_BRICK")
      (value "PAD.04")
      (footprint "eagle-import:PAD.04X.04")
      (libsource (lib "eagle-import") (part "PAD.04"))
    )
    (comp (ref "B601")
      (value "DO NOT PLACE")
      (footprint "eagle-import:MS621FE")
      (fields (field (name "PARTNO") "MS621FE-FL11E"))
      (libsource (lib "eagle-import") (part "MS621FE"))
    )
    (comp (ref "C601")
      (value "2u2")
      (footprint "eagle-import:0603-CAP")
      (fields (field (name "PARTNO") "C1608Y5V1C225Z"))
      (libsource (lib "eagle-import") (part "CAP0603"))
    )
    (comp (ref "C602")
      (value "10n")
      (footprint "eagle-import:0402-CAP")
      (fields (field (name "PARTNO") "CC0402KRX7R7BB103"))
      (libsource (lib "eagle-import") (part "CAP0402"))
    )
    (comp (ref "C603")
      (value "1u0")
      (footprint "eagle-import:0603-CAP")
      (fields (field (name "PARTNO") "CC0603ZRY5V7BB105"))
      (libsource (lib "eagle-import") (part "CAP0603"))
    )
    (comp (ref "C604")
      (value "10u/10V")
      (footprint "eagle-import:0805-CAP")
      (fields (field (name "PARTNO") "CC0805ZKY5V6BB106"))
      (libsource (lib "eagle-import") (part "CAP0805"))
    )
    (comp (ref "C605")
      (value "1u0")
      (footprint "eagle-import:0603-CAP")
      (fields (field (name "PARTNO") "CC0603ZRY5V7BB105"))
      (libsource (lib "eagle-import") (part "CAP0603"))
    )
    (comp (ref "C606")
      (value "0u1")
      (footprint "eagle-import:0402-CAP")
      (fields (field (name "PARTNO") "CC0402ZRY5V7BB104"))
      (libsource (lib "eagle-import") (part "CAP0402"))
    )
    (comp (ref "C607")
      (value "0u1")
      (footprint "eagle-import:0402-CAP")
      (fields (field (name "PARTNO") "CC0402ZRY5V7BB104"))
      (libsource (lib "eagle-import") (part "CAP0402"))
    )
    (comp (ref "C608")
      (value "0u1")
      (footprint "eagle-import:0402-CAP")
      (fields (field (name "PARTNO") "CC0402ZRY5V7BB104"))
      (libsource (lib "eagle-import") (part "CAP0402"))
    )
    (comp (ref "C609")
      (value "0u1")
      (footprint "eagle-import:0402-CAP")
      (fields (field (name "PARTNO") "CC0402ZRY5V7BB104"))
      (libsource (lib "eagle-import") (part "CAP0402"))
    )
    (comp (ref "C610")
      (value "0u1")
      (footprint "eagle-import:0402-CAP")
      (fields (field (name "PARTNO") "CC0402ZRY5V7BB104"))
      (libsource (lib "eagle-import") (part "CAP0402"))
    )
    (comp (ref "C611")
      (value "2u2")
      (footprint "eagle-import:0603-CAP")
      (fields (field (name "PARTNO") "C1608Y5V1C225Z"))
      (libsource (lib "eagle-import") (part "CAP0603"))
    )
    (comp (ref "C612")
      (value "0u1")
      (footprint "eagle-import:0402-CAP")
      (fields (field (name "PARTNO") "CC0402ZRY5V7BB104"))
      (libsource (lib "eagle-import") (part "CAP0402"))
    )
    (comp (ref "C613")
      (value "2u2")
      (footprint "eagle-import:0603-CAP")
      (fields (field (name "PARTNO") "C1608Y5V1C225Z"))
      (libsource (lib "eagle-import") (part "CAP0603"))
    )
    (comp (ref "L603")
      (value "KNH16C104DA5TS")
      (footprint "eagle-import:KYOCERA-KNH16-DA")
      (libsource (lib "eagle-import") (part "KNH16C104DA5TS"))
    )
    (comp (ref "R602")
      (value "16K5")
      (footprint "eagle-import:0402-RES")
      (fields (field (name "PARTNO") "RMCF0402FT16K5"))
      (libsource (lib "eagle-import") (part "RESISTOR0402-RES"))
    )
    (comp (ref "R603")
      (value "10K")
      (footprint "eagle-import:0402-RES")
      (fields (field (name "PARTNO") "RC0402FR-0710KL"))
      (libsource (lib "eagle-import") (part "RESISTOR0402-RES"))
    )
    (comp (ref "R606")
      (value "25K")
      (footprint "eagle-import:0402-RES")
      (fields (field (name "PARTNO") "RMCF0402FT25K5"))
      (libsource (lib "eagle-import") (part "RESISTOR0402-RES"))
    )
    (comp (ref "R607")
      (value "10K")
      (footprint "eagle-import:0402-RES")
      (fields (field (name "PARTNO") "RC0402FR-0710KL"))
      (libsource (lib "eagle-import") (part "RESISTOR0402-RES"))
    )
    (comp (ref "R608")
      (value "1K")
      (footprint "eagle-import:0402-RES")
      (fields (field (name "PARTNO") "RC0402FR-071KL"))
      (libsource (lib "eagle-import") (part "RESISTOR0402-RES"))
    )
    (comp (ref "R609")
      (value "10K/0.1%")
      (footprint "eagle-import:0402-RES")
      (fields (field (name "PARTNO") "ERA-2AEB103X"))
      (libsource (lib "eagle-import") (part "RESISTOR0402-RES"))
    )
    (comp (ref "R610")
      (value "10K/0.1%")
      (footprint "eagle-import:0402-RES")
      (fields (field (name "PARTNO") "ERA-2AEB103X"))
      (libsource (lib "eagle-import") (part "RESISTOR0402-RES"))
    )
    (comp (ref "R611")
      (value "10K")
      (footprint "eagle-import:0402-RES")
      (fields (field (name "PARTNO") "RC0402FR-0710KL"))
      (libsource (lib "eagle-import") (part "RESISTOR0402-RES"))
    )
    (comp (ref "S601")
      (value "RESET")
      (footprint "eagle-import:EVQP7J01K")
      (fields (field (name "PARTNO") "EVQP7J01K"))
      (libsource (lib "eagle-import") (part "SWITCH-MOMENTARY-2"))
    )
    (comp (ref "U$602")
      (value "BQ24315")
      (footprint "eagle-import:QFN8-DSG")
      (fields (field (name "PARTNO") "BQ24315DSGR"))
      (libsource (lib "eagle-import") (part "BQ24315"))
    )
    (comp (ref "U$604")
      (value "BQ24315")
      (footprint "eagle-import:QFN8-DSG")
      (fields (field (name "PARTNO") "BQ24315DSGR"))
      (libsource (lib "eagle-import") (part "BQ24315"))
    )
    (comp (ref "U$605")
      (value "MIC5332")
      (footprint "eagle-import:MLF-8-EPAD")
      (fields (field (name "PARTNO") "MIC5332-SSYMT"))
      (libsource (lib "eagle-import") (part "MIC5332"))
    )
    (comp (ref "J601")
      (value "DF13C-6P-1.25V")
      (footprint "eagle-import:DF13C-6P-1.25V")
      (fields (field (name "PARTNO") "DF13C-6P-1.25V(20)"))
      (libsource (lib "eagle-import") (part "DF13-6P-1.25V"))
    )
    (comp (ref "L601")
      (value "KNH16C104DA5TS")
      (footprint "eagle-import:KYOCERA-KNH16-DA")
      (libsource (lib "eagle-import") (part "KNH16C104DA5TS"))
    )
    (comp (ref "L602")
      (value "KNH16C104DA5TS")
      (footprint "eagle-import:KYOCERA-KNH16-DA")
      (libsource (lib "eagle-import") (part "KNH16C104DA5TS"))
    )
    (comp (ref "R1")
      (value "453K")
      (footprint "eagle-import:0402-RES")
      (fields (field (name "PARTNO") "RMCF0402FT453K"))
      (libsource (lib "eagle-import") (part "RESISTOR0402-RES"))
    )
    (comp (ref "R2")
      (value "45.3K")
      (footprint "eagle-import:0402-RES")
      (libsource (lib "eagle-import") (part "RESISTOR0402-RES"))
    )
    (comp (ref "R5")
      (value "105K")
      (footprint "eagle-import:0402-RES")
      (libsource (lib "eagle-import") (part "RESISTOR0402-RES"))
    )
    (comp (ref "R6")
      (value "453K")
      (footprint "eagle-import:0402-RES")
      (fields (field (name "PARTNO") "RMCF0402FT453K"))
      (libsource (lib "eagle-import") (part "RESISTOR0402-RES"))
    )
    (comp (ref "R7")
      (value "45.3K")
      (footprint "eagle-import:0402-RES")
      (libsource (lib "eagle-import") (part "RESISTOR0402-RES"))
    )
    (comp (ref "R8")
      (value "105K")
      (footprint "eagle-import:0402-RES")
      (libsource (lib "eagle-import") (part "RESISTOR0402-RES"))
    )
    (comp (ref "R9")
      (value "453K")
      (footprint "eagle-import:0402-RES")
      (fields (field (name "PARTNO") "RMCF0402FT453K"))
      (libsource (lib "eagle-import") (part "RESISTOR0402-RES"))
    )
    (comp (ref "R10")
      (value "45.3K")
      (footprint "eagle-import:0402-RES")
      (libsource (lib "eagle-import") (part "RESISTOR0402-RES"))
    )
    (comp (ref "R11")
      (value "105K")
      (footprint "eagle-import:0402-RES")
      (libsource (lib "eagle-import") (part "RESISTOR0402-RES"))
    )
    (comp (ref "R604")
      (value "10K/0.1%")
      (footprint "eagle-import:0402-RES")
      (fields (field (name "PARTNO") "ERA-2AEB103X"))
      (libsource (lib "eagle-import") (part "RESISTOR0402-RES"))
    )
    (comp (ref "R605")
      (value "10K/0.1%")
      (footprint "eagle-import:0402-RES")
      (fields (field (name "PARTNO") "ERA-2AEB103X"))
      (libsource (lib "eagle-import") (part "RESISTOR0402-RES"))
    )
    (comp (ref "U$2")
      (value "LTC4417")
      (footprint "eagle-import:MO-220")
      (libsource (lib "eagle-import") (part "LTC4117"))
    )
    (comp (ref "U$3")
      (value "NTHD4102P")
      (footprint "eagle-import:1206-8")
      (fields (field (name "PARTNO") "*"))
      (libsource (lib "eagle-import") (part "MOSFET-DUAL-PCHANNEL-CHIPFET"))
    )
    (comp (ref "U$4")
      (value "NTHD4102P")
      (footprint "eagle-import:1206-8")
      (fields (field (name "PARTNO") "*"))
      (libsource (lib "eagle-import") (part "MOSFET-DUAL-PCHANNEL-CHIPFET"))
    )
    (comp (ref "U$5")
      (value "NTHD4102P")
      (footprint "eagle-import:1206-8")
      (fields (field (name "PARTNO") "*"))
      (libsource (lib "eagle-import") (part "MOSFET-DUAL-PCHANNEL-CHIPFET"))
    )
    (comp (ref "C701")
      (value "0u1")
      (footprint "eagle-import:0402-CAP")
      (fields (field (name "PARTNO") "CC0402ZRY5V7BB104"))
      (libsource (lib "eagle-import") (part "CAP0402"))
    )
    (comp (ref "C702")
      (value "1u0")
      (footprint "eagle-import:0603-CAP")
      (fields (field (name "PARTNO") "CC0603ZRY5V7BB105"))
      (libsource (lib "eagle-import") (part "CAP0603"))
    )
    (comp (ref "C703")
      (value "5n6")
      (footprint "eagle-import:0402-CAP")
      (fields (field (name "PARTNO") "CC0402KRX7R7BB562"))
      (libsource (lib "eagle-import") (part "CAP0402"))
    )
    (comp (ref "C704")
      (value "0u47")
      (footprint "eagle-import:0402-CAP")
      (fields (field (name "PARTNO") "C1005X5R1C474K050BC"))
      (libsource (lib "eagle-import") (part "CAP0402"))
    )
    (comp (ref "J701")
      (value "DF13C-2P-1.25V")
      (footprint "eagle-import:DF13C-2P-1.25V")
      (fields (field (name "PARTNO") "DF13C-2P-1.25V(20)"))
      (libsource (lib "eagle-import") (part "DF13-2P-1.25V"))
    )
    (comp (ref "J702")
      (value "DF13C-3P-1.25V")
      (footprint "eagle-import:DF13C-3P-1.25V")
      (fields (field (name "PARTNO") "DF13C-3P-1.25V(20)"))
      (libsource (lib "eagle-import") (part "DF13-3P-1.25V"))
    )
    (comp (ref "L701")
      (value "47uH")
      (footprint "eagle-import:0805-IND")
      (fields (field (name "PARTNO") "MLZ2012M470W"))
      (libsource (lib "eagle-import") (part "INDUCTOR0805"))
    )
    (comp (ref "LED701")
      (value "AMBER")
      (footprint "eagle-import:0603-LED")
      (fields (field (name "PARTNO") "APTD1608SECK"))
      (libsource (lib "eagle-import") (part "LED0603"))
    )
    (comp (ref "LED702")
      (value "GREEN")
      (footprint "eagle-import:0603-LED")
      (fields (field (name "PARTNO") "APTD1608CGCK"))
      (libsource (lib "eagle-import") (part "LED0603"))
    )
    (comp (ref "LED703")
      (value "AMBER")
      (footprint "eagle-import:0603-LED")
      (fields (field (name "PARTNO") "APTD1608SECK"))
      (libsource (lib "eagle-import") (part "LED0603"))
    )
    (comp (ref "LED704")
      (value "GREEN")
      (footprint "eagle-import:0603-LED")
      (fields (field (name "PARTNO") "APTD1608CGCK"))
      (libsource (lib "eagle-import") (part "LED0603"))
    )
    (comp (ref "LED705")
      (value "BLUE")
      (footprint "eagle-import:0603-LED")
      (fields (field (name "PARTNO") "APTD1608QBC/D"))
      (libsource (lib "eagle-import") (part "LED0603"))
    )
    (comp (ref "R3")
      (value "220R")
      (footprint "eagle-import:0402-RES")
      (fields (field (name "PARTNO") "RC0402FR-07220RL"))
      (libsource (lib "eagle-import") (part "RESISTOR0402-RES"))
    )
    (comp (ref "R4")
      (value "220R")
      (footprint "eagle-import:0402-RES")
      (fields (field (name "PARTNO") "RC0402FR-07220RL"))
      (libsource (lib "eagle-import") (part "RESISTOR0402-RES"))
    )
    (comp (ref "R701")
      (value "9K09")
      (footprint "eagle-import:0402-RES")
      (fields (field (name "PARTNO") "RMCF0402FT9K09"))
      (libsource (lib "eagle-import") (part "RESISTOR0402-RES"))
    )
    (comp (ref "R702")
      (value "10K")
      (footprint "eagle-import:0402-RES")
      (fields (field (name "PARTNO") "RC0402FR-0710KL"))
      (libsource (lib "eagle-import") (part "RESISTOR0402-RES"))
    )
    (comp (ref "R703")
      (value "100K")
      (footprint "eagle-import:0402-RES")
      (fields (field (name "PARTNO") "RC0402FR-07100KL"))
      (libsource (lib "eagle-import") (part "RESISTOR0402-RES"))
    )
    (comp (ref "R704")
      (value "10K")
      (footprint "eagle-import:0402-RES")
      (fields (field (name "PARTNO") "RC0402FR-0710KL"))
      (libsource (lib "eagle-import") (part "RESISTOR0402-RES"))
    )
    (comp (ref "R705")
      (value "453K")
      (footprint "eagle-import:0402-RES")
      (fields (field (name "PARTNO") "RMCF0402FT453K"))
      (libsource (lib "eagle-import") (part "RESISTOR0402-RES"))
    )
    (comp (ref "R706")
      (value "16K5")
      (footprint "eagle-import:0402-RES")
      (fields (field (name "PARTNO") "RMCF0402FT16K5"))
      (libsource (lib "eagle-import") (part "RESISTOR0402-RES"))
    )
    (comp (ref "R707")
      (value "220R")
      (footprint "eagle-import:0402-RES")
      (fields (field (name "PARTNO") "RC0402FR-07220RL"))
      (libsource (lib "eagle-import") (part "RESISTOR0402-RES"))
    )
    (comp (ref "R708")
      (value "220R")
      (footprint "eagle-import:0402-RES")
      (fields (field (name "PARTNO") "RC0402FR-07220RL"))
      (libsource (lib "eagle-import") (part "RESISTOR0402-RES"))
    )
    (comp (ref "R709")
      (value "220R")
      (footprint "eagle-import:0402-RES")
      (fields (field (name "PARTNO") "RC0402FR-07220RL"))
      (libsource (lib "eagle-import") (part "RESISTOR0402-RES"))
    )
    (comp (ref "R710")
      (value "47R")
      (footprint "eagle-import:0402-RES")
      (fields (field (name "PARTNO") "RC0402JR-0747RL"))
      (libsource (lib "eagle-import") (part "RESISTOR0402-RES"))
    )
    (comp (ref "R711")
      (value "220R")
      (footprint "eagle-import:0402-RES")
      (fields (field (name "PARTNO") "RC0402FR-07220RL"))
      (libsource (lib "eagle-import") (part "RESISTOR0402-RES"))
    )
    (comp (ref "R712")
      (value "220R")
      (footprint "eagle-import:0402-RES")
      (fields (field (name "PARTNO") "RC0402FR-07220RL"))
      (libsource (lib "eagle-import") (part "RESISTOR0402-RES"))
    )
    (comp (ref "R713")
      (value "1K5")
      (footprint "eagle-import:0402-RES")
      (fields (field (name "PARTNO") "RC0402FR-071K5L"))
      (libsource (lib "eagle-import") (part "RESISTOR0402-RES"))
    )
    (comp (ref "U$701")
      (value "PESD0402-140")
      (footprint "eagle-import:0402-TVS")
      (libsource (lib "eagle-import") (part "DIODE-TVS"))
    )
    (comp (ref "U701")
      (value "TCA62724FMG")
      (footprint "eagle-import:SON10")
      (libsource (lib "eagle-import") (part "TCA62724FMG"))
    )
    (comp (ref "U702")
      (value "LT3469")
      (footprint "eagle-import:SOT23-8")
      (fields (field (name "PARTNO") "LT3469ETS8"))
      (libsource (lib "eagle-import") (part "LT3469"))
    )
    (comp (ref "U703")
      (value "LRTB GFTG-T7AW-1+V7A7-29+R5T9-49-L")
      (footprint "eagle-import:6-PLCC")
      (fields (field (name "PARTNO") "LRTB GFTG-T7AW-1+V7A7-29+R5T9-49-L"))
      (libsource (lib "eagle-import") (part "RGB-LED6-PLCC"))
    )
    (comp (ref "C1001")
      (value "1u0")
      (footprint "eagle-import:0603-CAP")
      (fields (field (name "PARTNO") "CC0603ZRY5V7BB105"))
      (libsource (lib "eagle-import") (part "CAP0603"))
    )
    (comp (ref "C1002")
      (value "10n")
      (footprint "eagle-import:0402-CAP")
      (fields (field (name "PARTNO") "CC0402KRX7R7BB103"))
      (libsource (lib "eagle-import") (part "CAP0402"))
    )
    (comp (ref "C1003")
      (value "1u0")
      (footprint "eagle-import:0603-CAP")
      (fields (field (name "PARTNO") "CC0603ZRY5V7BB105"))
      (libsource (lib "eagle-import") (part "CAP0603"))
    )
    (comp (ref "C1004")
      (value "1u0")
      (footprint "eagle-import:0603-CAP")
      (fields (field (name "PARTNO") "CC0603ZRY5V7BB105"))
      (libsource (lib "eagle-import") (part "CAP0603"))
    )
    (comp (ref "D1001")
      (value "PMEG2005CT")
      (footprint "eagle-import:SOT23-3")
      (libsource (lib "eagle-import") (part "PMEG2005CT"))
    )
    (comp (ref "F2")
      (value "0ZCA0035FF2G")
      (footprint "eagle-import:PTC-1206")
      (libsource (lib "eagle-import") (part "PTCSMD"))
    )
    (comp (ref "R1001")
      (value "100K")
      (footprint "eagle-import:0402-RES")
      (fields (field (name "PARTNO") "RC0402FR-07100KL"))
      (libsource (lib "eagle-import") (part "RESISTOR0402-RES"))
    )
    (comp (ref "R1002")
      (value "10K")
      (footprint "eagle-import:0402-RES")
      (fields (field (name "PARTNO") "RC0402FR-0710KL"))
      (libsource (lib "eagle-import") (part "RESISTOR0402-RES"))
    )
    (comp (ref "U$1001")
      (value "BQ24313")
      (footprint "eagle-import:QFN8-DSG")
      (fields (field (name "PARTNO") "BQ24313DSGT"))
      (libsource (lib "eagle-import") (part "BQ24313"))
    )
    (comp (ref "U$1002")
      (value "MIC5332")
      (footprint "eagle-import:MLF-8-EPAD")
      (fields (field (name "PARTNO") "MIC5332-SSYMT"))
      (libsource (lib "eagle-import") (part "MIC5332"))
    )
    (comp (ref "C501")
      (value "10u/10V")
      (footprint "eagle-import:0805-CAP")
      (fields (field (name "PARTNO") "CC0805ZKY5V6BB106"))
      (libsource (lib "eagle-import") (part "CAP0805"))
    )
    (comp (ref "C502")
      (value "0u1")
      (footprint "eagle-import:0402-CAP")
      (fields (field (name "PARTNO") "CC0402ZRY5V7BB104"))
      (libsource (lib "eagle-import") (part "CAP0402"))
    )
    (comp (ref "C503")
      (value "0u1")
      (footprint "eagle-import:0402-CAP")
      (fields (field (name "PARTNO") "CC0402ZRY5V7BB104"))
      (libsource (lib "eagle-import") (part "CAP0402"))
    )
    (comp (ref "C504")
      (value "10n")
      (footprint "eagle-import:0402-CAP")
      (fields (field (name "PARTNO") "CC0402KRX7R7BB103"))
      (libsource (lib "eagle-import") (part "CAP0402"))
    )
    (comp (ref "C505")
      (value "10n")
      (footprint "eagle-import:0402-CAP")
      (fields (field (name "PARTNO") "CC0402KRX7R7BB103"))
      (libsource (lib "eagle-import") (part "CAP0402"))
    )
    (comp (ref "C506")
      (value "10u/10V")
      (footprint "eagle-import:0805-CAP")
      (fields (field (name "PARTNO") "CC0805ZKY5V6BB106"))
      (libsource (lib "eagle-import") (part "CAP0805"))
    )
    (comp (ref "C507")
      (value "0u1")
      (footprint "eagle-import:0402-CAP")
      (fields (field (name "PARTNO") "CC0402ZRY5V7BB104"))
      (libsource (lib "eagle-import") (part "CAP0402"))
    )
    (comp (ref "C508")
      (value "0u1")
      (footprint "eagle-import:0402-CAP")
      (fields (field (name "PARTNO") "CC0402ZRY5V7BB104"))
      (libsource (lib "eagle-import") (part "CAP0402"))
    )
    (comp (ref "C509")
      (value "10u/10V")
      (footprint "eagle-import:0805-CAP")
      (fields (field (name "PARTNO") "CC0805ZKY5V6BB106"))
      (libsource (lib "eagle-import") (part "CAP0805"))
    )
    (comp (ref "C510")
      (value "0u47")
      (footprint "eagle-import:0402-CAP")
      (fields (field (name "PARTNO") "C1005X5R1C474K050BC"))
      (libsource (lib "eagle-import") (part "CAP0402"))
    )
    (comp (ref "U$1")
      (value "0512811094")
      (footprint "eagle-import:51281-1094")
      (fields (field (name "PARTNO") "0781191109"))
      (libsource (lib "eagle-import") (part "CONN_FPC_10RA"))
    )
    (comp (ref "U$501")
      (value "LSM303D")
      (footprint "eagle-import:LGA-16L")
      (libsource (lib "eagle-import") (part "LSM303D"))
    )
    (comp (ref "U501")
      (value "L3GD20")
      (footprint "eagle-import:L3G4200DH-MAN")
      (libsource (lib "eagle-import") (part "L3G4200DH-LL"))
    )
    (comp (ref "U502")
      (value "L3GD20H")
      (footprint "eagle-import:LGA-16L")
      (libsource (lib "eagle-import") (part "L3GD20H"))
    )
    (comp (ref "U503")
      (value "MS5611-01BA")
      (footprint "eagle-import:MS5611-01BA")
      (libsource (lib "eagle-import") (part "MS5611-01BA"))
    )
    (comp (ref "C901")
      (value "0u1")
      (footprint "eagle-import:0402-CAP")
      (fields (field (name "PARTNO") "CC0402ZRY5V7BB104"))
      (libsource (lib "eagle-import") (part "CAP0402"))
    )
    (comp (ref "C902")
      (value "0u1")
      (footprint "eagle-import:0402-CAP")
      (fields (field (name "PARTNO") "CC0402ZRY5V7BB104"))
      (libsource (lib "eagle-import") (part "CAP0402"))
    )
    (comp (ref "C903")
      (value "0u1")
      (footprint "eagle-import:0402-CAP")
      (fields (field (name "PARTNO") "CC0402ZRY5V7BB104"))
      (libsource (lib "eagle-import") (part "CAP0402"))
    )
    (comp (ref "D1")
      (value "MSS1P4-M3")
      (footprint "eagle-import:MICROSMP")
      (fields (field (name "PARTNO") "MSS1P4-M3/89A"))
      (libsource (lib "eagle-import") (part "DIODE-SCHOTTKY_MSMP"))
    )
    (comp (ref "J901")
      (value "HEADER-3X163X16RA")
      (footprint "eagle-import:3X16RA")
      (fields (field (name "BOM") "EXCLUDE"))
      (libsource (lib "eagle-import") (part "HEADER-3X163X16RA"))
    )
    (comp (ref "L901")
      (value "KNH16C104DA5TS")
      (footprint "eagle-import:KYOCERA-KNH16-DA")
      (libsource (lib "eagle-import") (part "KNH16C104DA5TS"))
    )
    (comp (ref "R901")
      (value "10K")
      (footprint "eagle-import:0402-RES")
      (fields (field (name "PARTNO") "RC0402FR-0710KL"))
      (libsource (lib "eagle-import") (part "RESISTOR0402-RES"))
    )
    (comp (ref "R902")
      (value "220R")
      (footprint "eagle-import:0402-RES")
      (fields (field (name "PARTNO") "RC0402FR-07220RL"))
      (libsource (lib "eagle-import") (part "RESISTOR0402-RES"))
    )
    (comp (ref "R903")
      (value "220R")
      (footprint "eagle-import:0402-RES")
      (fields (field (name "PARTNO") "RC0402FR-07220RL"))
      (libsource (lib "eagle-import") (part "RESISTOR0402-RES"))
    )
    (comp (ref "R904")
      (value "220R")
      (footprint "eagle-import:0402-RES")
      (fields (field (name "PARTNO") "RC0402FR-07220RL"))
      (libsource (lib "eagle-import") (part "RESISTOR0402-RES"))
    )
    (comp (ref "R905")
      (value "220R")
      (footprint "eagle-import:0402-RES")
      (fields (field (name "PARTNO") "RC0402FR-07220RL"))
      (libsource (lib "eagle-import") (part "RESISTOR0402-RES"))
    )
    (comp (ref "R906")
      (value "220R")
      (footprint "eagle-import:0402-RES")
      (fields (field (name "PARTNO") "RC0402FR-07220RL"))
      (libsource (lib "eagle-import") (part "RESISTOR0402-RES"))
    )
    (comp (ref "R907")
      (value "220R")
      (footprint "eagle-import:0402-RES")
      (fields (field (name "PARTNO") "RC0402FR-07220RL"))
      (libsource (lib "eagle-import") (part "RESISTOR0402-RES"))
    )
    (comp (ref "R908")
      (value "220R")
      (footprint "eagle-import:0402-RES")
      (fields (field (name "PARTNO") "RC0402FR-07220RL"))
      (libsource (lib "eagle-import") (part "RESISTOR0402-RES"))
    )
    (comp (ref "R909")
      (value "220R")
      (footprint "eagle-import:0402-RES")
      (fields (field (name "PARTNO") "RC0402FR-07220RL"))
      (libsource (lib "eagle-import") (part "RESISTOR0402-RES"))
    )
    (comp (ref "R910")
      (value "220R")
      (footprint "eagle-import:0402-RES")
      (fields (field (name "PARTNO") "RC0402FR-07220RL"))
      (libsource (lib "eagle-import") (part "RESISTOR0402-RES"))
    )
    (comp (ref "R911")
      (value "220R")
      (footprint "eagle-import:0402-RES")
      (fields (field (name "PARTNO") "RC0402FR-07220RL"))
      (libsource (lib "eagle-import") (part "RESISTOR0402-RES"))
    )
    (comp (ref "R912")
      (value "220R")
      (footprint "eagle-import:0402-RES")
      (fields (field (name "PARTNO") "RC0402FR-07220RL"))
      (libsource (lib "eagle-import") (part "RESISTOR0402-RES"))
    )
    (comp (ref "R913")
      (value "220R")
      (footprint "eagle-import:0402-RES")
      (fields (field (name "PARTNO") "RC0402FR-07220RL"))
      (libsource (lib "eagle-import") (part "RESISTOR0402-RES"))
    )
    (comp (ref "R914")
      (value "220R")
      (footprint "eagle-import:0402-RES")
      (fields (field (name "PARTNO") "RC0402FR-07220RL"))
      (libsource (lib "eagle-import") (part "RESISTOR0402-RES"))
    )
    (comp (ref "R915")
      (value "220R")
      (footprint "eagle-import:0402-RES")
      (fields (field (name "PARTNO") "RC0402FR-07220RL"))
      (libsource (lib "eagle-import") (part "RESISTOR0402-RES"))
    )
    (comp (ref "R916")
      (value "220R")
      (footprint "eagle-import:0402-RES")
      (fields (field (name "PARTNO") "RC0402FR-07220RL"))
      (libsource (lib "eagle-import") (part "RESISTOR0402-RES"))
    )
    (comp (ref "R917")
      (value "220R")
      (footprint "eagle-import:0402-RES")
      (fields (field (name "PARTNO") "RC0402FR-07220RL"))
      (libsource (lib "eagle-import") (part "RESISTOR0402-RES"))
    )
    (comp (ref "R918")
      (value "10K/0.1%")
      (footprint "eagle-import:0402-RES")
      (fields (field (name "PARTNO") "ERA-2AEB103X"))
      (libsource (lib "eagle-import") (part "RESISTOR0402-RES"))
    )
    (comp (ref "R919")
      (value "10K/0.1%")
      (footprint "eagle-import:0402-RES")
      (fields (field (name "PARTNO") "ERA-2AEB103X"))
      (libsource (lib "eagle-import") (part "RESISTOR0402-RES"))
    )
    (comp (ref "R922")
      (value "10K/0.1%")
      (footprint "eagle-import:0402-RES")
      (fields (field (name "PARTNO") "ERA-2AEB103X"))
      (libsource (lib "eagle-import") (part "RESISTOR0402-RES"))
    )
    (comp (ref "U$6")
      (value "PESD0402-140")
      (footprint "eagle-import:0402-TVS")
      (libsource (lib "eagle-import") (part "DIODE-TVS"))
    )
    (comp (ref "U$901")
      (value "PESD0402-140")
      (footprint "eagle-import:0402-TVS")
      (libsource (lib "eagle-import") (part "DIODE-TVS"))
    )
    (comp (ref "U$902")
      (value "PESD0402-140")
      (footprint "eagle-import:0402-TVS")
      (libsource (lib "eagle-import") (part "DIODE-TVS"))
    )
    (comp (ref "U901")
      (value "TXS0108QFN20")
      (footprint "eagle-import:QFN20-RGY")
      (fields (field (name "PARTNO") "TXS0108ERGYR"))
      (libsource (lib "eagle-import") (part "TXS0108QFN20"))
    )
    (comp (ref "U902")
      (value "TXS0108QFN20")
      (footprint "eagle-import:QFN20-RGY")
      (fields (field (name "PARTNO") "TXS0108ERGYR"))
      (libsource (lib "eagle-import") (part "TXS0108QFN20"))
    )
    (comp (ref "U903")
      (value "74LVC2G240")
      (footprint "eagle-import:TSSOP8_SOT505-2")
      (fields (field (name "PARTNO") "74LVC2G240DP,125"))
      (libsource (lib "eagle-import") (part "74LVC2G240-TSSOP-8"))
    )
    (comp (ref "C801")
      (value "0u1")
      (footprint "eagle-import:0402-CAP")
      (fields (field (name "PARTNO") "CC0402ZRY5V7BB104"))
      (libsource (lib "eagle-import") (part "CAP0402"))
    )
    (comp (ref "C802")
      (value "0u1")
      (footprint "eagle-import:0402-CAP")
      (fields (field (name "PARTNO") "CC0402ZRY5V7BB104"))
      (libsource (lib "eagle-import") (part "CAP0402"))
    )
    (comp (ref "C803")
      (value "0u1")
      (footprint "eagle-import:0402-CAP")
      (fields (field (name "PARTNO") "CC0402ZRY5V7BB104"))
      (libsource (lib "eagle-import") (part "CAP0402"))
    )
    (comp (ref "C804")
      (value "0u1")
      (footprint "eagle-import:0402-CAP")
      (fields (field (name "PARTNO") "CC0402ZRY5V7BB104"))
      (libsource (lib "eagle-import") (part "CAP0402"))
    )
    (comp (ref "C805")
      (value "8p")
      (footprint "eagle-import:0402-CAP")
      (fields (field (name "PARTNO") "C1005C0G1H080C"))
      (libsource (lib "eagle-import") (part "CAP0402"))
    )
    (comp (ref "C806")
      (value "8p")
      (footprint "eagle-import:0402-CAP")
      (fields (field (name "PARTNO") "C1005C0G1H080C"))
      (libsource (lib "eagle-import") (part "CAP0402"))
    )
    (comp (ref "J801")
      (value "JST-ZH-3")
      (footprint "eagle-import:JST-ZH-SMT-VERTICAL")
      (fields (field (name "PARTNO") "B3B-ZR-SM4-TF (LF)(SN)(P)"))
      (libsource (lib "eagle-import") (part "JST-ZH-3"))
    )
    (comp (ref "JX801")
      (value "HEADER-3X1BOARDEDGE-SHORT")
      (footprint "eagle-import:HEADER_3X01_SMD_H_BOARD_EDGE_SHORT")
      (libsource (lib "eagle-import") (part "HEADER-3X1BOARDEDGE-SHORT"))
    )
    (comp (ref "JX802")
      (value "ARM_MINI_JTAG-SMT")
      (footprint "eagle-import:FTSH-105-01-XXX-DV-K")
      (fields (field (name "BOM") "EXCLUDE") (field (name "PARTNO") "M50-3900542"))
      (libsource (lib "eagle-import") (part "ARM_MINI_JTAG-SMT"))
    )
    (comp (ref "R801")
      (value "10K")
      (footprint "eagle-import:0402-RES")
      (fields (field (name "PARTNO") "RC0402FR-0710KL"))
      (libsource (lib "eagle-import") (part "RESISTOR0402-RES"))
    )
    (comp (ref "R802")
      (value "10K")
      (footprint "eagle-import:0402-RES")
      (fields (field (name "PARTNO") "RC0402FR-0710KL"))
      (libsource (lib "eagle-import") (part "RESISTOR0402-RES"))
    )
    (comp (ref "R803")
      (value "220R")
      (footprint "eagle-import:0402-RES")
      (fields (field (name "PARTNO") "RC0402FR-07220RL"))
      (libsource (lib "eagle-import") (part "RESISTOR0402-RES"))
    )
    (comp (ref "R804")
      (value "220R")
      (footprint "eagle-import:0402-RES")
      (fields (field (name "PARTNO") "RC0402FR-07220RL"))
      (libsource (lib "eagle-import") (part "RESISTOR0402-RES"))
    )
    (comp (ref "S801")
      (value "RESET")
      (footprint "eagle-import:EVQP7J01K")
      (fields (field (name "PARTNO") "EVQP7J01K"))
      (libsource (lib "eagle-import") (part "SWITCH-MOMENTARY-2"))
    )
    (comp (ref "U$801")
      (value "PESD0402-140")
      (footprint "eagle-import:0402-TVS")
      (libsource (lib "eagle-import") (part "DIODE-TVS"))
    )
    (comp (ref "U801")
      (value "STM32F10XCXT6")
      (footprint "eagle-import:TQFP48")
      (fields (field (name "PARTNO") "STM32F100C8T6B"))
      (libsource (lib "eagle-import") (part "STM32F10XCXT6"))
    )
    (comp (ref "X801")
      (value "3.2x2.5 mm / 24 MHz / 15 ppm")
      (footprint "eagle-import:OSCILLATOR-3.2X2.5")
      (fields (field (name "PARTNO") "NX3225SA-24.000000MHZ"))
      (libsource (lib "eagle-import") (part "OSCILLATOR-3.2X2.5"))
    )
    (comp (ref "C401")
      (value "0u1")
      (footprint "eagle-import:0402-CAP")
      (fields (field (name "PARTNO") "CC0402ZRY5V7BB104"))
      (libsource (lib "eagle-import") (part "CAP0402"))
    )
    (comp (ref "C402")
      (value "0u1")
      (footprint "eagle-import:0402-CAP")
      (fields (field (name "PARTNO") "CC0402ZRY5V7BB104"))
      (libsource (lib "eagle-import") (part "CAP0402"))
    )
    (comp (ref "J401")
      (value "DF13C-4P-1.25V")
      (footprint "eagle-import:DF13C-4P-1.25V")
      (fields (field (name "PARTNO") "DF13C-4P-1.25V(20)"))
      (libsource (lib "eagle-import") (part "DF13-4P-1.25V"))
    )
    (comp (ref "J402")
      (value "DF13C-3P-1.25V")
      (footprint "eagle-import:DF13C-3P-1.25V")
      (fields (field (name "PARTNO") "DF13C-3P-1.25V(20)"))
      (libsource (lib "eagle-import") (part "DF13-3P-1.25V"))
    )
    (comp (ref "J403")
      (value "DF13C-7P-1.25V")
      (footprint "eagle-import:DF13C-7P-1.25V")
      (fields (field (name "PARTNO") "DF13C-7P-1.25V(20)"))
      (libsource (lib "eagle-import") (part "DF13-7P-1.25V"))
    )
    (comp (ref "J404")
      (value "DF13C-5P-1.25V")
      (footprint "eagle-import:DF13C-5P-1.25V")
      (fields (field (name "PARTNO") "DF13C-5P-1.25V(20)"))
      (libsource (lib "eagle-import") (part "DF13-5P-1.25V"))
    )
    (comp (ref "J405")
      (value "DF13C-4P-1.25V")
      (footprint "eagle-import:DF13C-4P-1.25V")
      (fields (field (name "PARTNO") "DF13C-4P-1.25V(20)"))
      (libsource (lib "eagle-import") (part "DF13-4P-1.25V"))
    )
    (comp (ref "L401")
      (value "KNH16C104DA5TS")
      (footprint "eagle-import:KYOCERA-KNH16-DA")
      (libsource (lib "eagle-import") (part "KNH16C104DA5TS"))
    )
    (comp (ref "L402")
      (value "KNH16C104DA5TS")
      (footprint "eagle-import:KYOCERA-KNH16-DA")
      (libsource (lib "eagle-import") (part "KNH16C104DA5TS"))
    )
    (comp (ref "L403")
      (value "KNH16C104DA5TS")
      (footprint "eagle-import:KYOCERA-KNH16-DA")
      (libsource (lib "eagle-import") (part "KNH16C104DA5TS"))
    )
    (comp (ref "L404")
      (value "KNH16C104DA5TS")
      (footprint "eagle-import:KYOCERA-KNH16-DA")
      (libsource (lib "eagle-import") (part "KNH16C104DA5TS"))
    )
    (comp (ref "R401")
      (value "1K5")
      (footprint "eagle-import:0402-RES")
      (fields (field (name "PARTNO") "RC0402FR-071K5L"))
      (libsource (lib "eagle-import") (part "RESISTOR0402-RES"))
    )
    (comp (ref "R402")
      (value "1K5")
      (footprint "eagle-import:0402-RES")
      (fields (field (name "PARTNO") "RC0402FR-071K5L"))
      (libsource (lib "eagle-import") (part "RESISTOR0402-RES"))
    )
    (comp (ref "R403")
      (value "10K/0.1%")
      (footprint "eagle-import:0402-RES")
      (fields (field (name "PARTNO") "ERA-2AEB103X"))
      (libsource (lib "eagle-import") (part "RESISTOR0402-RES"))
    )
    (comp (ref "R404")
      (value "120R")
      (footprint "eagle-import:0402-RES")
      (fields (field (name "PARTNO") "RC0402FR-07120RL"))
      (libsource (lib "eagle-import") (part "RESISTOR0402-RES"))
    )
    (comp (ref "R405")
      (value "120R")
      (footprint "eagle-import:0402-RES")
      (fields (field (name "PARTNO") "RC0402FR-07120RL"))
      (libsource (lib "eagle-import") (part "RESISTOR0402-RES"))
    )
    (comp (ref "R406")
      (value "10K/0.1%")
      (footprint "eagle-import:0402-RES")
      (fields (field (name "PARTNO") "ERA-2AEB103X"))
      (libsource (lib "eagle-import") (part "RESISTOR0402-RES"))
    )
    (comp (ref "R407")
      (value "10K/0.1%")
      (footprint "eagle-import:0402-RES")
      (fields (field (name "PARTNO") "ERA-2AEB103X"))
      (libsource (lib "eagle-import") (part "RESISTOR0402-RES"))
    )
    (comp (ref "R408")
      (value "10K/0.1%")
      (footprint "eagle-import:0402-RES")
      (fields (field (name "PARTNO") "ERA-2AEB103X"))
      (libsource (lib "eagle-import") (part "RESISTOR0402-RES"))
    )
    (comp (ref "R409")
      (value "120R")
      (footprint "eagle-import:0402-RES")
      (fields (field (name "PARTNO") "RC0402FR-07120RL"))
      (libsource (lib "eagle-import") (part "RESISTOR0402-RES"))
    )
    (comp (ref "U$401")
      (value "PESD0402-140")
      (footprint "eagle-import:0402-TVS")
      (libsource (lib "eagle-import") (part "DIODE-TVS"))
    )
    (comp (ref "U$402")
      (value "PESD0402-140")
      (footprint "eagle-import:0402-TVS")
      (libsource (lib "eagle-import") (part "DIODE-TVS"))
    )
    (comp (ref "U$403")
      (value "PESD0402-140")
      (footprint "eagle-import:0402-TVS")
      (libsource (lib "eagle-import") (part "DIODE-TVS"))
    )
    (comp (ref "U$404")
      (value "PESD0402-140")
      (footprint "eagle-import:0402-TVS")
      (libsource (lib "eagle-import") (part "DIODE-TVS"))
    )
    (comp (ref "U401")
      (value "MAX3051")
      (footprint "eagle-import:SOT23-8")
      (fields (field (name "PARTNO") "MAX3051EKA"))
      (libsource (lib "eagle-import") (part "MAX3051MAX3051EKA"))
    )
    (comp (ref "J301")
      (value "47346-0001")
      (footprint "eagle-import:MOLEX-47346-0001")
      (libsource (lib "eagle-import") (part "MOLEX-47346-0001"))
    )
    (comp (ref "J302")
      (value "DF13C-4P-1.25V")
      (footprint "eagle-import:DF13C-4P-1.25V")
      (fields (field (name "PARTNO") "DF13C-4P-1.25V(20)"))
      (libsource (lib "eagle-import") (part "DF13-4P-1.25V"))
    )
    (comp (ref "JX301")
      (value "ARM_MINI_JTAG-SMT")
      (footprint "eagle-import:FTSH-105-01-XXX-DV-K")
      (fields (field (name "BOM") "EXCLUDE") (field (name "PARTNO") "M50-3900542"))
      (libsource (lib "eagle-import") (part "ARM_MINI_JTAG-SMT"))
    )
    (comp (ref "R301")
      (value "100K")
      (footprint "eagle-import:0402-RES")
      (fields (field (name "PARTNO") "RC0402FR-07100KL"))
      (libsource (lib "eagle-import") (part "RESISTOR0402-RES"))
    )
    (comp (ref "R302")
      (value "100K")
      (footprint "eagle-import:0402-RES")
      (fields (field (name "PARTNO") "RC0402FR-07100KL"))
      (libsource (lib "eagle-import") (part "RESISTOR0402-RES"))
    )
    (comp (ref "R303")
      (value "100K")
      (footprint "eagle-import:0402-RES")
      (fields (field (name "PARTNO") "RC0402FR-07100KL"))
      (libsource (lib "eagle-import") (part "RESISTOR0402-RES"))
    )
    (comp (ref "R304")
      (value "100K")
      (footprint "eagle-import:0402-RES")
      (fields (field (name "PARTNO") "RC0402FR-07100KL"))
      (libsource (lib "eagle-import") (part "RESISTOR0402-RES"))
    )
    (comp (ref "R305")
      (value "100K")
      (footprint "eagle-import:0402-RES")
      (fields (field (name "PARTNO") "RC0402FR-07100KL"))
      (libsource (lib "eagle-import") (part "RESISTOR0402-RES"))
    )
    (comp (ref "R306")
      (value "1K5")
      (footprint "eagle-import:0402-RES")
      (fields (field (name "PARTNO") "RC0402FR-071K5L"))
      (libsource (lib "eagle-import") (part "RESISTOR0402-RES"))
    )
    (comp (ref "R307")
      (value "1K5")
      (footprint "eagle-import:0402-RES")
      (fields (field (name "PARTNO") "RC0402FR-071K5L"))
      (libsource (lib "eagle-import") (part "RESISTOR0402-RES"))
    )
    (comp (ref "U$301")
      (value "NUF2042XV6")
      (footprint "eagle-import:SOT563-6")
      (fields (field (name "PARTNO") "NUF2042XV6T1G"))
      (libsource (lib "eagle-import") (part "NUF2042XV6"))
    )
    (comp (ref "U301")
      (value "2908-05WB-MG")
      (footprint "eagle-import:MICROSD")
      (libsource (lib "eagle-import") (part "MICROSDSDI"))
    )
  )
  (nets
    (net (code "1") (name "ACCEL_DRDY") (class "Default")
      (node (ref "U$1") (pin "3") (pinfunction "S_3") (pintype "passive"))
      (node (ref "U$501") (pin "11") (pinfunction "INT1_11") (pintype "bidirectional"))
      (node (ref "U101") (pin "90") (pinfunction "PB4_90") (pintype "bidirectional"))
    )
    (net (code "2") (name "ALARM") (class "Default")
      (node (ref "R701") (pin "P$2") (pinfunction "2_P$2") (pintype "passive"))
      (node (ref "U101") (pin "77") (pinfunction "PA15_77") (pintype "bidirectional"))
    )
    (net (code "3") (name "BATT_CURRENT_SENS") (class "Default")
      (node (ref "R604") (pin "P$1") (pinfunction "1_P$1") (pintype "passive"))
      (node (ref "U101") (pin "26") (pinfunction "PA3_26") (pintype "bidirectional"))
    )
    (net (code "4") (name "BATT_VOLTAGE_SENS") (class "Default")
      (node (ref "R605") (pin "P$1") (pinfunction "1_P$1") (pintype "passive"))
      (node (ref "U101") (pin "25") (pinfunction "PA2_25") (pintype "bidirectional"))
    )
    (net (code "5") (name "CAN1_RX") (class "Default")
      (node (ref "U101") (pin "81") (pinfunction "PD0_81") (pintype "bidirectional"))
      (node (ref "U401") (pin "4") (pinfunction "DOUT_4") (pintype "output"))
    )
    (net (code "6") (name "CAN1_TX") (class "Default")
      (node (ref "U101") (pin "82") (pinfunction "PD1_82") (pintype "bidirectional"))
      (node (ref "U401") (pin "1") (pinfunction "DIN_1") (pintype "input"))
    )
    (net (code "7") (name "CAN2_RX") (class "Default")
      (node (ref "R13") (pin "P$1") (pinfunction "1_P$1") (pintype "passive"))
      (node (ref "U101") (pin "51") (pinfunction "PB12_51") (pintype "bidirectional"))
    )
    (net (code "8") (name "CAN2_TX") (class "Default")
      (node (ref "R12") (pin "P$1") (pinfunction "1_P$1") (pintype "passive"))
      (node (ref "U101") (pin "92") (pinfunction "PB6_92") (pintype "bidirectional"))
    )
    (net (code "9") (name "CAN_H") (class "Default")
      (node (ref "CAN_H") (pin "P$1") (pinfunction "P$1_P$1") (pintype "passive"))
      (node (ref "J405") (pin "P$2") (pinfunction "2_P$2") (pintype "passive"))
      (node (ref "R409") (pin "P$1") (pinfunction "1_P$1") (pintype "passive"))
      (node (ref "U401") (pin "7") (pinfunction "CANH_7") (pintype "bidirectional"))
    )
    (net (code "10") (name "CAN_L") (class "Default")
      (node (ref "CAN_L") (pin "P$1") (pinfunction "P$1_P$1") (pintype "passive"))
      (node (ref "J405") (pin "P$3") (pinfunction "3_P$3") (pintype "passive"))
      (node (ref "R409") (pin "P$2") (pinfunction "2_P$2") (pintype "passive"))
      (node (ref "U401") (pin "6") (pinfunction "CANL_6") (pintype "bidirectional"))
    )
    (net (code "11") (name "FMU-BOOT0") (class "Default")
      (node (ref "FMU-BOOT1101") (pin "P$1") (pinfunction "P$1_P$1") (pintype "passive"))
      (node (ref "R611") (pin "P$2") (pinfunction "2_P$2") (pintype "passive"))
      (node (ref "U101") (pin "94") (pinfunction "BOOT0_94") (pintype "input"))
    )
    (net (code "12") (name "FMU-CH1") (class "Default")
      (node (ref "U101") (pin "45") (pinfunction "PE14_45") (pintype "bidirectional"))
      (node (ref "U901") (pin "7") (pinfunction "A6_7") (pintype "bidirectional"))
    )
    (net (code "13") (name "FMU-CH2") (class "Default")
      (node (ref "U101") (pin "44") (pinfunction "PE13_44") (pintype "bidirectional"))
      (node (ref "U901") (pin "6") (pinfunction "A5_6") (pintype "bidirectional"))
    )
    (net (code "14") (name "FMU-CH3") (class "Default")
      (node (ref "U101") (pin "42") (pinfunction "PE11_42") (pintype "bidirectional"))
      (node (ref "U901") (pin "5") (pinfunction "A4_5") (pintype "bidirectional"))
    )
    (net (code "15") (name "FMU-CH4") (class "Default")
      (node (ref "U101") (pin "40") (pinfunction "PE9_40") (pintype "bidirectional"))
      (node (ref "U901") (pin "4") (pinfunction "A3_4") (pintype "bidirectional"))
    )
    (net (code "16") (name "FMU-CH5") (class "Default")
      (node (ref "U101") (pin "60") (pinfunction "PD13_60") (pintype "bidirectional"))
      (node (ref "U901") (pin "3") (pinfunction "A2_3") (pintype "bidirectional"))
    )
    (net (code "17") (name "FMU-CH6") (class "Default")
      (node (ref "U101") (pin "61") (pinfunction "PD14_61") (pintype "bidirectional"))
      (node (ref "U901") (pin "1") (pinfunction "A1_1") (pintype "bidirectional"))
    )
    (net (code "18") (name "FMU-I2C1_SCL") (class "Default")
      (node (ref "R401") (pin "P$1") (pinfunction "1_P$1") (pintype "passive"))
      (node (ref "R404") (pin "P$1") (pinfunction "1_P$1") (pintype "passive"))
      (node (ref "U101") (pin "95") (pinfunction "PB8_95") (pintype "bidirectional"))
    )
    (net (code "19") (name "FMU-I2C1_SDA") (class "Default")
      (node (ref "R402") (pin "P$1") (pinfunction "1_P$1") (pintype "passive"))
      (node (ref "R405") (pin "P$1") (pinfunction "1_P$1") (pintype "passive"))
      (node (ref "U101") (pin "96") (pinfunction "PB9_96") (pintype "bidirectional"))
    )
    (net (code "20") (name "FMU-I2C2_SCL") (class "Default")
      (node (ref "R306") (pin "P$1") (pinfunction "1_P$1") (pintype "passive"))
      (node (ref "U101") (pin "47") (pinfunction "PB10_47") (pintype "bidirectional"))
      (node (ref "U701") (pin "3") (pinfunction "SCL_3") (pintype "bidirectional"))
    )
    (net (code "21") (name "FMU-I2C2_SDA") (class "Default")
      (node (ref "R307") (pin "P$1") (pinfunction "1_P$1") (pintype "passive"))
      (node (ref "U101") (pin "48") (pinfunction "PB11_48") (pintype "bidirectional"))
      (node (ref "U701") (pin "2") (pinfunction "SDA_2") (pintype "bidirectional"))
    )
    (net (code "22") (name "FMU-SWCLK") (class "Default")
      (node (ref "JX301") (pin "4") (pinfunction "S_4") (pintype "passive"))
      (node (ref "U101") (pin "76") (pinfunction "PA14_76") (pintype "bidirectional"))
    )
    (net (code "23") (name "FMU-SWDIO") (class "Default")
      (node (ref "JX301") (pin "2") (pinfunction "S_2") (pintype "passive"))
      (node (ref "U101") (pin "72") (pinfunction "PA13_72") (pintype "bidirectional"))
    )
    (net (code "24") (name "FMU-SWO") (class "Default")
      (node (ref "JX301") (pin "6") (pinfunction "S_6") (pintype "passive"))
      (node (ref "U101") (pin "89") (pinfunction "PB3_89") (pintype "bidirectional"))
    )
    (net (code "25") (name "FMU-UART4_RX") (class "Default")
      (node (ref "U101") (pin "24") (pinfunction "PA1_24") (pintype "bidirectional"))
      (node (ref "U202") (pin "8") (pinfunction "A7_8") (pintype "bidirectional"))
    )
    (net (code "26") (name "FMU-UART4_TX") (class "Default")
      (node (ref "U101") (pin "23") (pinfunction "PA0_23") (pintype "bidirectional"))
      (node (ref "U202") (pin "9") (pinfunction "A8_9") (pintype "bidirectional"))
    )
    (net (code "27") (name "FMU-UART7_RX") (class "Default")
      (node (ref "U101") (pin "38") (pinfunction "PE7_38") (pintype "bidirectional"))
      (node (ref "U202") (pin "4") (pinfunction "A3_4") (pintype "bidirectional"))
    )
    (net (code "28") (name "FMU-UART7_TX") (class "Default")
      (node (ref "U101") (pin "39") (pinfunction "PE8_39") (pintype "bidirectional"))
      (node (ref "U202") (pin "5") (pinfunction "A4_5") (pintype "bidirectional"))
    )
    (net (code "29") (name "FMU-UART8_RX") (class "Default")
      (node (ref "U101") (pin "97") (pinfunction "PE0_97") (pintype "bidirectional"))
      (node (ref "U202") (pin "6") (pinfunction "A5_6") (pintype "bidirectional"))
    )
    (net (code "30") (name "FMU-UART8_TX") (class "Default")
      (node (ref "U101") (pin "98") (pinfunction "PE1_98") (pintype "bidirectional"))
      (node (ref "U202") (pin "7") (pinfunction "A6_7") (pintype "bidirectional"))
    )
    (net (code "31") (name "FMU-USART2_CTS") (class "Default")
      (node (ref "U101") (pin "84") (pinfunction "PD3_84") (pintype "bidirectional"))
      (node (ref "U201") (pin "9") (pinfunction "A8_9") (pintype "bidirectional"))
    )
    (net (code "32") (name "FMU-USART2_RTS") (class "Default")
      (node (ref "U101") (pin "85") (pinfunction "PD4_85") (pintype "bidirectional"))
      (node (ref "U201") (pin "8") (pinfunction "A7_8") (pintype "bidirectional"))
    )
    (net (code "33") (name "FMU-USART2_RX") (class "Default")
      (node (ref "U101") (pin "87") (pinfunction "PD6_87") (pintype "bidirectional"))
      (node (ref "U201") (pin "6") (pinfunction "A5_6") (pintype "bidirectional"))
    )
    (net (code "34") (name "FMU-USART2_TX") (class "Default")
      (node (ref "U101") (pin "86") (pinfunction "PD5_86") (pintype "bidirectional"))
      (node (ref "U201") (pin "7") (pinfunction "A6_7") (pintype "bidirectional"))
    )
    (net (code "35") (name "FMU-USART3_CTS") (class "Default")
      (node (ref "U101") (pin "58") (pinfunction "PD11_58") (pintype "bidirectional"))
      (node (ref "U201") (pin "3") (pinfunction "A2_3") (pintype "bidirectional"))
    )
    (net (code "36") (name "FMU-USART3_RTS") (class "Default")
      (node (ref "U101") (pin "59") (pinfunction "PD12_59") (pintype "bidirectional"))
      (node (ref "U201") (pin "1") (pinfunction "A1_1") (pintype "bidirectional"))
    )
    (net (code "37") (name "FMU-USART3_RX") (class "Default")
      (node (ref "U101") (pin "56") (pinfunction "PD9_56") (pintype "bidirectional"))
      (node (ref "U201") (pin "4") (pinfunction "A3_4") (pintype "bidirectional"))
    )
    (net (code "38") (name "FMU-USART3_TX") (class "Default")
      (node (ref "U101") (pin "55") (pinfunction "PD8_55") (pintype "bidirectional"))
      (node (ref "U201") (pin "5") (pinfunction "A4_5") (pintype "bidirectional"))
    )
    (net (code "39") (name "FMU-VDD_3V3") (class "Default")
      (node (ref "C101") (pin "P$1") (pinfunction "1_P$1") (pintype "passive"))
      (node (ref "C201") (pin "P$1") (pinfunction "1_P$1") (pintype "passive"))
      (node (ref "C202") (pin "P$1") (pinfunction "1_P$1") (pintype "passive"))
      (node (ref "C402") (pin "P$1") (pinfunction "1_P$1") (pintype "passive"))
      (node (ref "C603") (pin "P$1") (pinfunction "1_P$1") (pintype "passive"))
      (node (ref "C604") (pin "P$1") (pinfunction "1_P$1") (pintype "passive"))
      (node (ref "C606") (pin "P$1") (pinfunction "1_P$1") (pintype "passive"))
      (node (ref "C607") (pin "P$1") (pinfunction "1_P$1") (pintype "passive"))
      (node (ref "C608") (pin "P$1") (pinfunction "1_P$1") (pintype "passive"))
      (node (ref "C610") (pin "P$1") (pinfunction "1_P$1") (pintype "passive"))
      (node (ref "C612") (pin "P$1") (pinfunction "1_P$1") (pintype "passive"))
      (node (ref "C701") (pin "P$1") (pinfunction "1_P$1") (pintype "passive"))
      (node (ref "C902") (pin "P$1") (pinfunction "1_P$1") (pintype "passive"))
      (node (ref "JX301") (pin "1") (pinfunction "S_1") (pintype "passive"))
      (node (ref "R301") (pin "P$2") (pinfunction "2_P$2") (pintype "passive"))
      (node (ref "R302") (pin "P$2") (pinfunction "2_P$2") (pintype "passive"))
      (node (ref "R303") (pin "P$2") (pinfunction "2_P$2") (pintype "passive"))
      (node (ref "R304") (pin "P$2") (pinfunction "2_P$2") (pintype "passive"))
      (node (ref "R305") (pin "P$2") (pinfunction "2_P$2") (pintype "passive"))
      (node (ref "R306") (pin "P$2") (pinfunction "2_P$2") (pintype "passive"))
      (node (ref "R307") (pin "P$2") (pinfunction "2_P$2") (pintype "passive"))
      (node (ref "R401") (pin "P$2") (pinfunction "2_P$2") (pintype "passive"))
      (node (ref "R402") (pin "P$2") (pinfunction "2_P$2") (pintype "passive"))
      (node (ref "R608") (pin "P$2") (pinfunction "2_P$2") (pintype "passive"))
      (node (ref "U$605") (pin "7") (pinfunction "VOUT2_7") (pintype "bidirectional"))
      (node (ref "U101") (pin "100") (pinfunction "VDD_100") (pintype "power_in"))
      (node (ref "U101") (pin "11") (pinfunction "VDD_11") (pintype "power_in"))
      (node (ref "U101") (pin "19") (pinfunction "VDD_19") (pintype "power_in"))
      (node (ref "U101") (pin "21") (pinfunction "VREF+_21") (pintype "input"))
      (node (ref "U101") (pin "22") (pinfunction "VDDA_22") (pintype "power_in"))
      (node (ref "U101") (pin "28") (pinfunction "VDD_28") (pintype "power_in"))
      (node (ref "U101") (pin "50") (pinfunction "VDD_50") (pintype "power_in"))
      (node (ref "U101") (pin "75") (pinfunction "VDD_75") (pintype "power_in"))
      (node (ref "U102") (pin "3") (pinfunction "~{W}_3") (pintype "bidirectional"))
      (node (ref "U102") (pin "7") (pinfunction "~{HOLD}_7") (pintype "bidirectional"))
      (node (ref "U102") (pin "8") (pinfunction "VDD_8") (pintype "bidirectional"))
      (node (ref "U201") (pin "10") (pinfunction "OE_10") (pintype "input"))
      (node (ref "U201") (pin "19") (pinfunction "VCCB_19") (pintype "input"))
      (node (ref "U201") (pin "2") (pinfunction "VCCA_2") (pintype "input"))
      (node (ref "U202") (pin "10") (pinfunction "OE_10") (pintype "input"))
      (node (ref "U202") (pin "19") (pinfunction "VCCB_19") (pintype "input"))
      (node (ref "U202") (pin "2") (pinfunction "VCCA_2") (pintype "input"))
      (node (ref "U301") (pin "4") (pinfunction "VCC_4") (pintype "passive"))
      (node (ref "U401") (pin "3") (pinfunction "VCC_3") (pintype "input"))
      (node (ref "U701") (pin "1") (pinfunction "~{SHDN}_1") (pintype "input"))
      (node (ref "U701") (pin "10") (pinfunction "VIN_10") (pintype "power_in"))
      (node (ref "U901") (pin "10") (pinfunction "OE_10") (pintype "input"))
      (node (ref "U901") (pin "19") (pinfunction "VCCB_19") (pintype "input"))
      (node (ref "U901") (pin "2") (pinfunction "VCCA_2") (pintype "input"))
      (node (ref "VDD_3V1101") (pin "P$1") (pinfunction "P$1_P$1") (pintype "passive"))
    )
    (net (code "40") (name "FMU-~{RESET}") (class "Default")
      (node (ref "C609") (pin "P$2") (pinfunction "2_P$2") (pintype "passive"))
      (node (ref "S601") (pin "A1") (pinfunction "1_A1") (pintype "passive"))
      (node (ref "U$605") (pin "3") (pinfunction "POR2_3") (pintype "bidirectional"))
      (node (ref "U101") (pin "14") (pinfunction "NRST_14") (pintype "input"))
      (node (ref "U701") (pin "4") (pinfunction "~{RESET}_4") (pintype "input"))
    )
    (net (code "41") (name "FMU_AUX_ADC1") (class "Default")
      (node (ref "R408") (pin "P$1") (pinfunction "1_P$1") (pintype "passive"))
      (node (ref "U101") (pin "18") (pinfunction "PC3_18") (pintype "bidirectional"))
    )
    (net (code "42") (name "FMU_AUX_ADC2") (class "Default")
      (node (ref "R407") (pin "P$1") (pinfunction "1_P$1") (pintype "passive"))
      (node (ref "U101") (pin "33") (pinfunction "PC4_33") (pintype "bidirectional"))
    )
    (net (code "43") (name "FRAM_MISO") (class "Default")
      (node (ref "U101") (pin "53") (pinfunction "PB14_53") (pintype "bidirectional"))
      (node (ref "U102") (pin "2") (pinfunction "Q_2") (pintype "bidirectional"))
    )
    (net (code "44") (name "FRAM_MOSI") (class "Default")
      (node (ref "U101") (pin "54") (pinfunction "PB15_54") (pintype "bidirectional"))
      (node (ref "U102") (pin "5") (pinfunction "D_5") (pintype "bidirectional"))
    )
    (net (code "45") (name "FRAM_SCK") (class "Default")
      (node (ref "U101") (pin "52") (pinfunction "PB13_52") (pintype "bidirectional"))
      (node (ref "U102") (pin "6") (pinfunction "C_6") (pintype "bidirectional"))
    )
    (net (code "46") (name "GND") (class "Default")
      (node (ref "B601") (pin "2") (pinfunction "NEG_2") (pintype "bidirectional"))
      (node (ref "C1001") (pin "P$2") (pinfunction "2_P$2") (pintype "passive"))
      (node (ref "C1002") (pin "P$2") (pinfunction "2_P$2") (pintype "passive"))
      (node (ref "C1003") (pin "P$2") (pinfunction "2_P$2") (pintype "passive"))
      (node (ref "C1004") (pin "P$2") (pinfunction "2_P$2") (pintype "passive"))
      (node (ref "C101") (pin "P$2") (pinfunction "2_P$2") (pintype "passive"))
      (node (ref "C102") (pin "P$2") (pinfunction "2_P$2") (pintype "passive"))
      (node (ref "C103") (pin "P$1") (pinfunction "1_P$1") (pintype "passive"))
      (node (ref "C201") (pin "P$2") (pinfunction "2_P$2") (pintype "passive"))
      (node (ref "C202") (pin "P$2") (pinfunction "2_P$2") (pintype "passive"))
      (node (ref "C401") (pin "P$2") (pinfunction "2_P$2") (pintype "passive"))
      (node (ref "C402") (pin "P$2") (pinfunction "2_P$2") (pintype "passive"))
      (node (ref "C501") (pin "P$2") (pinfunction "2_P$2") (pintype "passive"))
      (node (ref "C502") (pin "P$2") (pinfunction "2_P$2") (pintype "passive"))
      (node (ref "C503") (pin "P$2") (pinfunction "2_P$2") (pintype "passive"))
      (node (ref "C504") (pin "P$2") (pinfunction "2_P$2") (pintype "passive"))
      (node (ref "C505") (pin "P$2") (pinfunction "2_P$2") (pintype "passive"))
      (node (ref "C506") (pin "P$2") (pinfunction "2_P$2") (pintype "passive"))
      (node (ref "C507") (pin "P$2") (pinfunction "2_P$2") (pintype "passive"))
      (node (ref "C508") (pin "P$2") (pinfunction "2_P$2") (pintype "passive"))
      (node (ref "C509") (pin "P$2") (pinfunction "2_P$2") (pintype "passive"))
      (node (ref "C601") (pin "P$2") (pinfunction "2_P$2") (pintype "passive"))
      (node (ref "C602") (pin "P$1") (pinfunction "1_P$1") (pintype "passive"))
      (node (ref "C603") (pin "P$2") (pinfunction "2_P$2") (pintype "passive"))
      (node (ref "C604") (pin "P$2") (pinfunction "2_P$2") (pintype "passive"))
      (node (ref "C605") (pin "P$2") (pinfunction "2_P$2") (pintype "passive"))
      (node (ref "C606") (pin "P$2") (pinfunction "2_P$2") (pintype "passive"))
      (node (ref "C607") (pin "P$2") (pinfunction "2_P$2") (pintype "passive"))
      (node (ref "C608") (pin "P$2") (pinfunction "2_P$2") (pintype "passive"))
      (node (ref "C609") (pin "P$1") (pinfunction "1_P$1") (pintype "passive"))
      (node (ref "C610") (pin "P$2") (pinfunction "2_P$2") (pintype "passive"))
      (node (ref "C611") (pin "P$2") (pinfunction "2_P$2") (pintype "passive"))
      (node (ref "C612") (pin "P$2") (pinfunction "2_P$2") (pintype "passive"))
      (node (ref "C613") (pin "P$2") (pinfunction "2_P$2") (pintype "passive"))
      (node (ref "C701") (pin "P$2") (pinfunction "2_P$2") (pintype "passive"))
      (node (ref "C702") (pin "P$2") (pinfunction "2_P$2") (pintype "passive"))
      (node (ref "C703") (pin "P$2") (pinfunction "2_P$2") (pintype "passive"))
      (node (ref "C704") (pin "P$2") (pinfunction "2_P$2") (pintype "passive"))
      (node (ref "C801") (pin "P$1") (pinfunction "1_P$1") (pintype "passive"))
      (node (ref "C802") (pin "P$2") (pinfunction "2_P$2") (pintype "passive"))
      (node (ref "C803") (pin "P$2") (pinfunction "2_P$2") (pintype "passive"))
      (node (ref "C804") (pin "P$2") (pinfunction "2_P$2") (pintype "passive"))
      (node (ref "C805") (pin "P$2") (pinfunction "2_P$2") (pintype "passive"))
      (node (ref "C806") (pin "P$1") (pinfunction "1_P$1") (pintype "passive"))
      (node (ref "C901") (pin "P$2") (pinfunction "2_P$2") (pintype "passive"))
      (node (ref "C902") (pin "P$2") (pinfunction "2_P$2") (pintype "passive"))
      (node (ref "C903") (pin "P$2") (pinfunction "2_P$2") (pintype "passive"))
      (node (ref "GND") (pin "P$1") (pinfunction "P$1_P$1") (pintype "passive"))
      (node (ref "GND.") (pin "P$1") (pinfunction "P$1_P$1") (pintype "passive"))
      (node (ref "J201") (pin "P$6") (pinfunction "6_P$6") (pintype "passive"))
      (node (ref "J202") (pin "P$6") (pinfunction "6_P$6") (pintype "passive"))
      (node (ref "J203") (pin "P$6") (pinfunction "6_P$6") (pintype "passive"))
      (node (ref "J204") (pin "P$6") (pinfunction "6_P$6") (pintype "passive"))
      (node (ref "J301") (pin "GND") (pinfunction "5_GND") (pintype "power_in"))
      (node (ref "J301") (pin "GND1") (pinfunction "GND1_GND1") (pintype "bidirectional"))
      (node (ref "J301") (pin "GND2") (pinfunction "GND2_GND2") (pintype "bidirectional"))
      (node (ref "J301") (pin "GND3") (pinfunction "GND3_GND3") (pintype "bidirectional"))
      (node (ref "J301") (pin "GND4") (pinfunction "GND4_GND4") (pintype "bidirectional"))
      (node (ref "J302") (pin "P$4") (pinfunction "4_P$4") (pintype "passive"))
      (node (ref "J401") (pin "P$4") (pinfunction "4_P$4") (pintype "passive"))
      (node (ref "J402") (pin "P$3") (pinfunction "3_P$3") (pintype "passive"))
      (node (ref "J403") (pin "P$7") (pinfunction "7_P$7") (pintype "passive"))
      (node (ref "J404") (pin "P$3") (pinfunction "3_P$3") (pintype "passive"))
      (node (ref "J404") (pin "P$5") (pinfunction "5_P$5") (pintype "passive"))
      (node (ref "J405") (pin "P$4") (pinfunction "4_P$4") (pintype "passive"))
      (node (ref "J601") (pin "P$5") (pinfunction "5_P$5") (pintype "passive"))
      (node (ref "J601") (pin "P$6") (pinfunction "6_P$6") (pintype "passive"))
      (node (ref "J701") (pin "P$2") (pinfunction "2_P$2") (pintype "passive"))
      (node (ref "J801") (pin "P$2") (pinfunction "P$2_P$2") (pintype "bidirectional"))
      (node (ref "J901") (pin "12") (pinfunction "S_12") (pintype "passive"))
      (node (ref "J901") (pin "15") (pinfunction "S_15") (pintype "passive"))
      (node (ref "J901") (pin "18") (pinfunction "S_18") (pintype "passive"))
      (node (ref "J901") (pin "21") (pinfunction "S_21") (pintype "passive"))
      (node (ref "J901") (pin "24") (pinfunction "S_24") (pintype "passive"))
      (node (ref "J901") (pin "27") (pinfunction "S_27") (pintype "passive"))
      (node (ref "J901") (pin "3") (pinfunction "S_3") (pintype "passive"))
      (node (ref "J901") (pin "30") (pinfunction "S_30") (pintype "passive"))
      (node (ref "J901") (pin "33") (pinfunction "S_33") (pintype "passive"))
      (node (ref "J901") (pin "36") (pinfunction "S_36") (pintype "passive"))
      (node (ref "J901") (pin "39") (pinfunction "S_39") (pintype "passive"))
      (node (ref "J901") (pin "42") (pinfunction "S_42") (pintype "passive"))
      (node (ref "J901") (pin "45") (pinfunction "S_45") (pintype "passive"))
      (node (ref "J901") (pin "48") (pinfunction "S_48") (pintype "passive"))
      (node (ref "J901") (pin "6") (pinfunction "S_6") (pintype "passive"))
      (node (ref "J901") (pin "9") (pinfunction "S_9") (pintype "passive"))
      (node (ref "JX301") (pin "3") (pinfunction "S_3") (pintype "passive"))
      (node (ref "JX301") (pin "5") (pinfunction "S_5") (pintype "passive"))
      (node (ref "JX301") (pin "9") (pinfunction "S_9") (pintype "passive"))
      (node (ref "JX801") (pin "3") (pinfunction "GND_3") (pintype "bidirectional"))
      (node (ref "JX802") (pin "3") (pinfunction "S_3") (pintype "passive"))
      (node (ref "JX802") (pin "5") (pinfunction "S_5") (pintype "passive"))
      (node (ref "JX802") (pin "9") (pinfunction "S_9") (pintype "passive"))
      (node (ref "L201") (pin "P$3") (pinfunction "P$3_P$3") (pintype "bidirectional"))
      (node (ref "L201") (pin "P$4") (pinfunction "P$3_P$4") (pintype "bidirectional"))
      (node (ref "L201") (pin "P$5") (pinfunction "P$3_P$5") (pintype "bidirectional"))
      (node (ref "L202") (pin "P$3") (pinfunction "P$3_P$3") (pintype "bidirectional"))
      (node (ref "L202") (pin "P$4") (pinfunction "P$3_P$4") (pintype "bidirectional"))
      (node (ref "L202") (pin "P$5") (pinfunction "P$3_P$5") (pintype "bidirectional"))
      (node (ref "L203") (pin "P$3") (pinfunction "P$3_P$3") (pintype "bidirectional"))
      (node (ref "L203") (pin "P$4") (pinfunction "P$3_P$4") (pintype "bidirectional"))
      (node (ref "L203") (pin "P$5") (pinfunction "P$3_P$5") (pintype "bidirectional"))
      (node (ref "L401") (pin "P$3") (pinfunction "P$3_P$3") (pintype "bidirectional"))
      (node (ref "L401") (pin "P$4") (pinfunction "P$3_P$4") (pintype "bidirectional"))
      (node (ref "L401") (pin "P$5") (pinfunction "P$3_P$5") (pintype "bidirectional"))
      (node (ref "L402") (pin "P$3") (pinfunction "P$3_P$3") (pintype "bidirectional"))
      (node (ref "L402") (pin "P$4") (pinfunction "P$3_P$4") (pintype "bidirectional"))
      (node (ref "L402") (pin "P$5") (pinfunction "P$3_P$5") (pintype "bidirectional"))
      (node (ref "L403") (pin "P$3") (pinfunction "P$3_P$3") (pintype "bidirectional"))
      (node (ref "L403") (pin "P$4") (pinfunction "P$3_P$4") (pintype "bidirectional"))
      (node (ref "L403") (pin "P$5") (pinfunction "P$3_P$5") (pintype "bidirectional"))
      (node (ref "L404") (pin "P$3") (pinfunction "P$3_P$3") (pintype "bidirectional"))
      (node (ref "L404") (pin "P$4") (pinfunction "P$3_P$4") (pintype "bidirectional"))
      (node (ref "L404") (pin "P$5") (pinfunction "P$3_P$5") (pintype "bidirectional"))
      (node (ref "L601") (pin "P$3") (pinfunction "P$3_P$3") (pintype "bidirectional"))
      (node (ref "L601") (pin "P$4") (pinfunction "P$3_P$4") (pintype "bidirectional"))
      (node (ref "L601") (pin "P$5") (pinfunction "P$3_P$5") (pintype "bidirectional"))
      (node (ref "L602") (pin "P$3") (pinfunction "P$3_P$3") (pintype "bidirectional"))
      (node (ref "L602") (pin "P$4") (pinfunction "P$3_P$4") (pintype "bidirectional"))
      (node (ref "L602") (pin "P$5") (pinfunction "P$3_P$5") (pintype "bidirectional"))
      (node (ref "L603") (pin "P$3") (pinfunction "P$3_P$3") (pintype "bidirectional"))
      (node (ref "L603") (pin "P$4") (pinfunction "P$3_P$4") (pintype "bidirectional"))
      (node (ref "L603") (pin "P$5") (pinfunction "P$3_P$5") (pintype "bidirectional"))
      (node (ref "L901") (pin "P$3") (pinfunction "P$3_P$3") (pintype "bidirectional"))
      (node (ref "L901") (pin "P$4") (pinfunction "P$3_P$4") (pintype "bidirectional"))
      (node (ref "L901") (pin "P$5") (pinfunction "P$3_P$5") (pintype "bidirectional"))
      (node (ref "R1001") (pin "P$1") (pinfunction "1_P$1") (pintype "passive"))
      (node (ref "R1002") (pin "P$1") (pinfunction "1_P$1") (pintype "passive"))
      (node (ref "R102") (pin "P$2") (pinfunction "2_P$2") (pintype "passive"))
      (node (ref "R11") (pin "P$2") (pinfunction "2_P$2") (pintype "passive"))
      (node (ref "R403") (pin "P$1") (pinfunction "1_P$1") (pintype "passive"))
      (node (ref "R5") (pin "P$2") (pinfunction "2_P$2") (pintype "passive"))
      (node (ref "R602") (pin "P$2") (pinfunction "2_P$2") (pintype "passive"))
      (node (ref "R606") (pin "P$2") (pinfunction "2_P$2") (pintype "passive"))
      (node (ref "R607") (pin "P$2") (pinfunction "2_P$2") (pintype "passive"))
      (node (ref "R610") (pin "P$2") (pinfunction "2_P$2") (pintype "passive"))
      (node (ref "R611") (pin "P$1") (pinfunction "1_P$1") (pintype "passive"))
      (node (ref "R702") (pin "P$2") (pinfunction "2_P$2") (pintype "passive"))
      (node (ref "R704") (pin "P$1") (pinfunction "1_P$1") (pintype "passive"))
      (node (ref "R706") (pin "P$2") (pinfunction "2_P$2") (pintype "passive"))
      (node (ref "R708") (pin "P$1") (pinfunction "1_P$1") (pintype "passive"))
      (node (ref "R711") (pin "P$1") (pinfunction "1_P$1") (pintype "passive"))
      (node (ref "R713") (pin "P$2") (pinfunction "2_P$2") (pintype "passive"))
      (node (ref "R8") (pin "P$2") (pinfunction "2_P$2") (pintype "passive"))
      (node (ref "R801") (pin "P$2") (pinfunction "2_P$2") (pintype "passive"))
      (node (ref "R802") (pin "P$2") (pinfunction "2_P$2") (pintype "passive"))
      (node (ref "R919") (pin "P$1") (pinfunction "1_P$1") (pintype "passive"))
      (node (ref "S601") (pin "B3") (pinfunction "2_B3") (pintype "passive"))
      (node (ref "S801") (pin "B3") (pinfunction "2_B3") (pintype "passive"))
      (node (ref "U$1") (pin "2") (pinfunction "S_2") (pintype "passive"))
      (node (ref "U$1001") (pin "2") (pinfunction "VSS_2") (pintype "bidirectional"))
      (node (ref "U$1001") (pin "5") (pinfunction "~{CE}_5") (pintype "bidirectional"))
      (node (ref "U$1001") (pin "6") (pinfunction "VBAT_6") (pintype "bidirectional"))
      (node (ref "U$1001") (pin "GND") (pinfunction "VSS_GND") (pintype "bidirectional"))
      (node (ref "U$1001") (pin "P$2") (pinfunction "VSS_P$2") (pintype "bidirectional"))
      (node (ref "U$1001") (pin "P$3") (pinfunction "VSS_P$3") (pintype "bidirectional"))
      (node (ref "U$1002") (pin "2") (pinfunction "GND_2") (pintype "bidirectional"))
      (node (ref "U$1002") (pin "GND") (pinfunction "GND_GND") (pintype "bidirectional"))
      (node (ref "U$2") (pin "P$10") (pinfunction "GND_P$10") (pintype "bidirectional"))
      (node (ref "U$2") (pin "P$24") (pinfunction "HYS_P$24") (pintype "bidirectional"))
      (node (ref "U$2") (pin "P$25") (pinfunction "GND_P$25") (pintype "bidirectional"))
      (node (ref "U$201") (pin "A") (pinfunction "A_A") (pintype "passive"))
      (node (ref "U$202") (pin "A") (pinfunction "A_A") (pintype "passive"))
      (node (ref "U$203") (pin "A") (pinfunction "A_A") (pintype "passive"))
      (node (ref "U$301") (pin "2") (pinfunction "GND_2") (pintype "bidirectional"))
      (node (ref "U$401") (pin "A") (pinfunction "A_A") (pintype "passive"))
      (node (ref "U$402") (pin "A") (pinfunction "A_A") (pintype "passive"))
      (node (ref "U$403") (pin "A") (pinfunction "A_A") (pintype "passive"))
      (node (ref "U$404") (pin "A") (pinfunction "A_A") (pintype "passive"))
      (node (ref "U$501") (pin "10") (pinfunction "RSRV_10") (pintype "bidirectional"))
      (node (ref "U$501") (pin "12") (pinfunction "GND_12") (pintype "bidirectional"))
      (node (ref "U$501") (pin "13") (pinfunction "GND_13") (pintype "bidirectional"))
      (node (ref "U$501") (pin "16") (pinfunction "GND_16") (pintype "bidirectional"))
      (node (ref "U$501") (pin "5") (pinfunction "GND_5") (pintype "bidirectional"))
      (node (ref "U$6") (pin "A") (pinfunction "A_A") (pintype "passive"))
      (node (ref "U$602") (pin "2") (pinfunction "VSS_2") (pintype "bidirectional"))
      (node (ref "U$602") (pin "6") (pinfunction "VBAT_6") (pintype "bidirectional"))
      (node (ref "U$602") (pin "GND") (pinfunction "VSS_GND") (pintype "bidirectional"))
      (node (ref "U$602") (pin "P$2") (pinfunction "VSS_P$2") (pintype "bidirectional"))
      (node (ref "U$602") (pin "P$3") (pinfunction "VSS_P$3") (pintype "bidirectional"))
      (node (ref "U$604") (pin "2") (pinfunction "VSS_2") (pintype "bidirectional"))
      (node (ref "U$604") (pin "6") (pinfunction "VBAT_6") (pintype "bidirectional"))
      (node (ref "U$604") (pin "GND") (pinfunction "VSS_GND") (pintype "bidirectional"))
      (node (ref "U$604") (pin "P$2") (pinfunction "VSS_P$2") (pintype "bidirectional"))
      (node (ref "U$604") (pin "P$3") (pinfunction "VSS_P$3") (pintype "bidirectional"))
      (node (ref "U$605") (pin "2") (pinfunction "GND_2") (pintype "bidirectional"))
      (node (ref "U$605") (pin "GND") (pinfunction "GND_GND") (pintype "bidirectional"))
      (node (ref "U$701") (pin "A") (pinfunction "A_A") (pintype "passive"))
      (node (ref "U$801") (pin "A") (pinfunction "A_A") (pintype "passive"))
      (node (ref "U$901") (pin "A") (pinfunction "A_A") (pintype "passive"))
      (node (ref "U$902") (pin "A") (pinfunction "A_A") (pintype "passive"))
      (node (ref "U101") (pin "10") (pinfunction "VSS_10") (pintype "power_in"))
      (node (ref "U101") (pin "20") (pinfunction "VSSA_20") (pintype "power_in"))
      (node (ref "U101") (pin "27") (pinfunction "VSS_27") (pintype "power_in"))
      (node (ref "U101") (pin "74") (pinfunction "VSS_74") (pintype "power_in"))
      (node (ref "U101") (pin "99") (pinfunction "VSS_99") (pintype "power_in"))
      (node (ref "U102") (pin "4") (pinfunction "VSS_4") (pintype "bidirectional"))
      (node (ref "U201") (pin "11") (pinfunction "GND_11") (pintype "power_in"))
      (node (ref "U202") (pin "11") (pinfunction "GND_11") (pintype "power_in"))
      (node (ref "U301") (pin "6") (pinfunction "GND_6") (pintype "power_in"))
      (node (ref "U401") (pin "2") (pinfunction "GND_2") (pintype "power_in"))
      (node (ref "U401") (pin "5") (pinfunction "SHDN_5") (pintype "input"))
      (node (ref "U401") (pin "8") (pinfunction "RS_8") (pintype "input"))
      (node (ref "U501") (pin "10") (pinfunction "RES_P10_GND_10") (pintype "bidirectional"))
      (node (ref "U501") (pin "11") (pinfunction "RES_P11_GND_11") (pintype "bidirectional"))
      (node (ref "U501") (pin "12") (pinfunction "RES_P12_GND_12") (pintype "bidirectional"))
      (node (ref "U501") (pin "13") (pinfunction "GND_13") (pintype "bidirectional"))
      (node (ref "U501") (pin "8") (pinfunction "RES_P8_GND_8") (pintype "bidirectional"))
      (node (ref "U501") (pin "9") (pinfunction "RES_P9_GND_9") (pintype "bidirectional"))
      (node (ref "U502") (pin "10") (pinfunction "GND_10") (pintype "bidirectional"))
      (node (ref "U502") (pin "11") (pinfunction "GND_11") (pintype "bidirectional"))
      (node (ref "U502") (pin "12") (pinfunction "GND_12") (pintype "bidirectional"))
      (node (ref "U502") (pin "13") (pinfunction "GND_13") (pintype "bidirectional"))
      (node (ref "U502") (pin "9") (pinfunction "GND_9") (pintype "bidirectional"))
      (node (ref "U503") (pin "2") (pinfunction "PS_2") (pintype "bidirectional"))
      (node (ref "U503") (pin "3") (pinfunction "GND_3") (pintype "bidirectional"))
      (node (ref "U701") (pin "5") (pinfunction "GND_5") (pintype "power_in"))
      (node (ref "U702") (pin "4") (pinfunction "GND_4") (pintype "power_in"))
      (node (ref "U801") (pin "23") (pinfunction "VSS_1_23") (pintype "power_in"))
      (node (ref "U801") (pin "35") (pinfunction "VSS_2_35") (pintype "power_in"))
      (node (ref "U801") (pin "47") (pinfunction "VSS_3_47") (pintype "power_in"))
      (node (ref "U801") (pin "8") (pinfunction "VSSA_8") (pintype "power_in"))
      (node (ref "U901") (pin "11") (pinfunction "GND_11") (pintype "power_in"))
      (node (ref "U902") (pin "11") (pinfunction "GND_11") (pintype "power_in"))
      (node (ref "U903") (pin "1") (pinfunction "~{1OE}_1") (pintype "input"))
      (node (ref "U903") (pin "4") (pinfunction "GND_4") (pintype "power_in"))
      (node (ref "X101") (pin "2") (pinfunction "NC_2_2") (pintype "power_in"))
      (node (ref "X101") (pin "4") (pinfunction "NC_4_4") (pintype "power_in"))
      (node (ref "X801") (pin "2") (pinfunction "NC_2_2") (pintype "power_in"))
      (node (ref "X801") (pin "4") (pinfunction "NC_4_4") (pintype "power_in"))
    )
    (net (code "47") (name "GPIO_EXT_1") (class "Default")
      (node (ref "J403") (pin "P$6") (pinfunction "6_P$6") (pintype "passive"))
      (node (ref "U101") (pin "8") (pinfunction "PC14_8") (pintype "bidirectional"))
    )
    (net (code "48") (name "GYRO_DRDY") (class "Default")
      (node (ref "U$1") (pin "5") (pinfunction "S_5") (pintype "passive"))
      (node (ref "U101") (pin "35") (pinfunction "PB0_35") (pintype "bidirectional"))
      (node (ref "U501") (pin "6") (pinfunction "DRDY/INT2_6") (pintype "output"))
      (node (ref "U502") (pin "6") (pinfunction "DRDY/INT2_6") (pintype "bidirectional"))
    )
    (net (code "49") (name "IO-BOOT0") (class "Default")
      (node (ref "IO-BOOT1101") (pin "P$1") (pinfunction "P$1_P$1") (pintype "passive"))
      (node (ref "R801") (pin "P$1") (pinfunction "1_P$1") (pintype "passive"))
      (node (ref "U801") (pin "44") (pinfunction "BOOT0_44") (pintype "input"))
    )
    (net (code "50") (name "IO-CH1") (class "Default")
      (node (ref "U801") (pin "10") (pinfunction "PA0_10") (pintype "bidirectional"))
      (node (ref "U902") (pin "9") (pinfunction "A8_9") (pintype "bidirectional"))
    )
    (net (code "51") (name "IO-CH2") (class "Default")
      (node (ref "U801") (pin "11") (pinfunction "PA1_11") (pintype "bidirectional"))
      (node (ref "U902") (pin "8") (pinfunction "A7_8") (pintype "bidirectional"))
    )
    (net (code "52") (name "IO-CH3") (class "Default")
      (node (ref "U801") (pin "45") (pinfunction "PB8_45") (pintype "bidirectional"))
      (node (ref "U902") (pin "7") (pinfunction "A6_7") (pintype "bidirectional"))
    )
    (net (code "53") (name "IO-CH4") (class "Default")
      (node (ref "U801") (pin "46") (pinfunction "PB9_46") (pintype "bidirectional"))
      (node (ref "U902") (pin "6") (pinfunction "A5_6") (pintype "bidirectional"))
    )
    (net (code "54") (name "IO-CH5") (class "Default")
      (node (ref "U801") (pin "16") (pinfunction "PA6_16") (pintype "bidirectional"))
      (node (ref "U902") (pin "5") (pinfunction "A4_5") (pintype "bidirectional"))
    )
    (net (code "55") (name "IO-CH6") (class "Default")
      (node (ref "U801") (pin "17") (pinfunction "PA7_17") (pintype "bidirectional"))
      (node (ref "U902") (pin "4") (pinfunction "A3_4") (pintype "bidirectional"))
    )
    (net (code "56") (name "IO-CH7") (class "Default")
      (node (ref "U801") (pin "18") (pinfunction "PB0_18") (pintype "bidirectional"))
      (node (ref "U902") (pin "3") (pinfunction "A2_3") (pintype "bidirectional"))
    )
    (net (code "57") (name "IO-CH8") (class "Default")
      (node (ref "U801") (pin "19") (pinfunction "PB1_19") (pintype "bidirectional"))
      (node (ref "U902") (pin "1") (pinfunction "A1_1") (pintype "bidirectional"))
    )
    (net (code "58") (name "IO-SWCLK") (class "Default")
      (node (ref "JX802") (pin "4") (pinfunction "S_4") (pintype "passive"))
      (node (ref "U801") (pin "37") (pinfunction "PA14_37") (pintype "bidirectional"))
    )
    (net (code "59") (name "IO-SWDIO") (class "Default")
      (node (ref "JX802") (pin "2") (pinfunction "S_2") (pintype "passive"))
      (node (ref "U801") (pin "34") (pinfunction "PA13_34") (pintype "bidirectional"))
    )
    (net (code "60") (name "IO-SWO") (class "Default")
      (node (ref "JX802") (pin "6") (pinfunction "S_6") (pintype "passive"))
      (node (ref "U801") (pin "39") (pinfunction "PB3_39") (pintype "bidirectional"))
    )
    (net (code "61") (name "IO-USART1_RX") (class "Default")
      (node (ref "J801") (pin "P$3") (pinfunction "P$3_P$3") (pintype "bidirectional"))
      (node (ref "JX801") (pin "2") (pinfunction "+5V_2") (pintype "bidirectional"))
      (node (ref "U801") (pin "31") (pinfunction "PA10_31") (pintype "bidirectional"))
    )
    (net (code "62") (name "IO-USART1_TX") (class "Default")
      (node (ref "JX801") (pin "1") (pinfunction "PPM_1") (pintype "bidirectional"))
      (node (ref "R101") (pin "P$2") (pinfunction "2_P$2") (pintype "passive"))
      (node (ref "U801") (pin "30") (pinfunction "PA9_30") (pintype "bidirectional"))
    )
    (net (code "63") (name "IO-VDD_3V3") (class "Default")
      (node (ref "C1004") (pin "P$1") (pinfunction "1_P$1") (pintype "passive"))
      (node (ref "C802") (pin "P$1") (pinfunction "1_P$1") (pintype "passive"))
      (node (ref "C803") (pin "P$1") (pinfunction "1_P$1") (pintype "passive"))
      (node (ref "C804") (pin "P$1") (pinfunction "1_P$1") (pintype "passive"))
      (node (ref "C901") (pin "P$1") (pinfunction "1_P$1") (pintype "passive"))
      (node (ref "C903") (pin "P$1") (pinfunction "1_P$1") (pintype "passive"))
      (node (ref "J702") (pin "P$1") (pinfunction "1_P$1") (pintype "passive"))
      (node (ref "JX802") (pin "1") (pinfunction "S_1") (pintype "passive"))
      (node (ref "U$1002") (pin "7") (pinfunction "VOUT2_7") (pintype "bidirectional"))
      (node (ref "U$701") (pin "C") (pinfunction "C_C") (pintype "passive"))
      (node (ref "U801") (pin "24") (pinfunction "VDD_1_24") (pintype "power_in"))
      (node (ref "U801") (pin "36") (pinfunction "VDD_2_36") (pintype "power_in"))
      (node (ref "U801") (pin "48") (pinfunction "VDD_3_48") (pintype "power_in"))
      (node (ref "U801") (pin "9") (pinfunction "VDDA_9") (pintype "power_in"))
      (node (ref "U902") (pin "10") (pinfunction "OE_10") (pintype "input"))
      (node (ref "U902") (pin "19") (pinfunction "VCCB_19") (pintype "input"))
      (node (ref "U902") (pin "2") (pinfunction "VCCA_2") (pintype "input"))
      (node (ref "U903") (pin "8") (pinfunction "VCC_8") (pintype "power_in"))
    )
    (net (code "64") (name "IO-VDD_5V5") (class "Default")
      (node (ref "C1001") (pin "P$1") (pinfunction "1_P$1") (pintype "passive"))
      (node (ref "D1001") (pin "3") (pinfunction "CC_3") (pintype "passive"))
      (node (ref "J901") (pin "2") (pinfunction "S_2") (pintype "passive"))
      (node (ref "LED702") (pin "A") (pinfunction "A_A") (pintype "passive"))
      (node (ref "LED703") (pin "A") (pinfunction "A_A") (pintype "passive"))
      (node (ref "LED705") (pin "A") (pinfunction "A_A") (pintype "passive"))
      (node (ref "U$1002") (pin "1") (pinfunction "VIN_1") (pintype "bidirectional"))
      (node (ref "U$1002") (pin "4") (pinfunction "EN2_4") (pintype "bidirectional"))
    )
    (net (code "65") (name "IO-~{RESET}") (class "Default")
      (node (ref "C801") (pin "P$2") (pinfunction "2_P$2") (pintype "passive"))
      (node (ref "S801") (pin "A1") (pinfunction "1_A1") (pintype "passive"))
      (node (ref "U$1002") (pin "3") (pinfunction "POR2_3") (pintype "bidirectional"))
      (node (ref "U801") (pin "7") (pinfunction "NRST_7") (pintype "input"))
    )
    (net (code "66") (name "IO-~{VDD_SERVO_IN_FAULT}") (class "Default")
      (node (ref "U$1001") (pin "4") (pinfunction "~{FAULT}_4") (pintype "bidirectional"))
      (node (ref "U801") (pin "38") (pinfunction "PA15_38") (pintype "bidirectional"))
    )
    (net (code "67") (name "MAG_DRDY") (class "Default")
      (node (ref "U$1") (pin "4") (pinfunction "S_4") (pintype "passive"))
      (node (ref "U$501") (pin "9") (pinfunction "INT2_9") (pintype "bidirectional"))
      (node (ref "U101") (pin "36") (pinfunction "PB1_36") (pintype "bidirectional"))
    )
    (net (code "68") (name "Net-(C102-1)") (class "Default")
      (node (ref "C102") (pin "P$1") (pinfunction "1_P$1") (pintype "passive"))
      (node (ref "U101") (pin "12") (pinfunction "OSC_IN_12") (pintype "input"))
      (node (ref "X101") (pin "3") (pinfunction "3_3") (pintype "bidirectional"))
    )
    (net (code "69") (name "Net-(C103-2)") (class "Default")
      (node (ref "C103") (pin "P$2") (pinfunction "2_P$2") (pintype "passive"))
      (node (ref "U101") (pin "13") (pinfunction "OSC_OUT_13") (pintype "output"))
      (node (ref "X101") (pin "1") (pinfunction "1_1") (pintype "bidirectional"))
    )
    (net (code "70") (name "Net-(C504-1)") (class "Default")
      (node (ref "C504") (pin "P$1") (pinfunction "1_P$1") (pintype "passive"))
      (node (ref "U501") (pin "14") (pinfunction "PLLFILT_14") (pintype "bidirectional"))
    )
    (net (code "71") (name "Net-(C505-1)") (class "Default")
      (node (ref "C505") (pin "P$1") (pinfunction "1_P$1") (pintype "passive"))
      (node (ref "U502") (pin "14") (pinfunction "CAP_14") (pintype "bidirectional"))
    )
    (net (code "72") (name "Net-(C509-1)") (class "Default")
      (node (ref "C509") (pin "P$1") (pinfunction "1_P$1") (pintype "passive"))
      (node (ref "U$501") (pin "15") (pinfunction "C1_15") (pintype "bidirectional"))
    )
    (net (code "73") (name "Net-(C510-1)") (class "Default")
      (node (ref "C510") (pin "P$1") (pinfunction "1_P$1") (pintype "passive"))
      (node (ref "U$501") (pin "2") (pinfunction "SETC_2") (pintype "bidirectional"))
    )
    (net (code "74") (name "Net-(C510-2)") (class "Default")
      (node (ref "C510") (pin "P$2") (pinfunction "2_P$2") (pintype "passive"))
      (node (ref "U$501") (pin "3") (pinfunction "SETP_3") (pintype "bidirectional"))
    )
    (net (code "75") (name "Net-(C601-1)") (class "Default")
      (node (ref "C601") (pin "P$1") (pinfunction "1_P$1") (pintype "passive"))
      (node (ref "L603") (pin "P$2") (pinfunction "P$2_P$2") (pintype "bidirectional"))
      (node (ref "R603") (pin "P$2") (pinfunction "2_P$2") (pintype "passive"))
      (node (ref "U$605") (pin "1") (pinfunction "VIN_1") (pintype "bidirectional"))
      (node (ref "U$605") (pin "4") (pinfunction "EN2_4") (pintype "bidirectional"))
    )
    (net (code "76") (name "Net-(C602-2)") (class "Default")
      (node (ref "C602") (pin "P$2") (pinfunction "2_P$2") (pintype "passive"))
      (node (ref "U$605") (pin "6") (pinfunction "CSET_6") (pintype "bidirectional"))
    )
    (net (code "77") (name "Net-(C611-1)") (class "Default")
      (node (ref "C611") (pin "P$1") (pinfunction "1_P$1") (pintype "passive"))
      (node (ref "U101") (pin "49") (pinfunction "VCAP_1_49") (pintype "power_in"))
    )
    (net (code "78") (name "Net-(C613-1)") (class "Default")
      (node (ref "C613") (pin "P$1") (pinfunction "1_P$1") (pintype "passive"))
      (node (ref "U101") (pin "73") (pinfunction "VCAP_2_73") (pintype "power_in"))
    )
    (net (code "79") (name "Net-(C703-1)") (class "Default")
      (node (ref "C703") (pin "P$1") (pinfunction "1_P$1") (pintype "passive"))
      (node (ref "J701") (pin "P$1") (pinfunction "1_P$1") (pintype "passive"))
      (node (ref "R703") (pin "P$1") (pinfunction "1_P$1") (pintype "passive"))
      (node (ref "U702") (pin "1") (pinfunction "OUT_1") (pintype "output"))
    )
    (net (code "80") (name "Net-(C704-1)") (class "Default")
      (node (ref "C704") (pin "P$1") (pinfunction "1_P$1") (pintype "passive"))
      (node (ref "R705") (pin "P$1") (pinfunction "1_P$1") (pintype "passive"))
      (node (ref "U702") (pin "6") (pinfunction "VCC_6") (pintype "bidirectional"))
    )
    (net (code "81") (name "Net-(C805-1)") (class "Default")
      (node (ref "C805") (pin "P$1") (pinfunction "1_P$1") (pintype "passive"))
      (node (ref "U801") (pin "5") (pinfunction "PD0/OSC<=_5") (pintype "bidirectional"))
      (node (ref "X801") (pin "3") (pinfunction "3_3") (pintype "bidirectional"))
    )
    (net (code "82") (name "Net-(C806-2)") (class "Default")
      (node (ref "C806") (pin "P$2") (pinfunction "2_P$2") (pintype "passive"))
      (node (ref "U801") (pin "6") (pinfunction "PD1/OSC=>_6") (pintype "bidirectional"))
      (node (ref "X801") (pin "1") (pinfunction "1_1") (pintype "bidirectional"))
    )
    (net (code "83") (name "Net-(C1002-1)") (class "Default")
      (node (ref "C1002") (pin "P$1") (pinfunction "1_P$1") (pintype "passive"))
      (node (ref "U$1002") (pin "6") (pinfunction "CSET_6") (pintype "bidirectional"))
    )
    (net (code "84") (name "Net-(D1-C)") (class "Default")
      (node (ref "D1") (pin "CATHODE") (pinfunction "C_CATHODE") (pintype "passive"))
      (node (ref "L901") (pin "P$1") (pinfunction "P$1_P$1") (pintype "bidirectional"))
      (node (ref "U$6") (pin "C") (pinfunction "C_C") (pintype "passive"))
    )
    (net (code "85") (name "Net-(D1001-A1)") (class "Default")
      (node (ref "D1001") (pin "1") (pinfunction "A1_1") (pintype "passive"))
      (node (ref "F2") (pin "2") (pinfunction "2_2") (pintype "bidirectional"))
    )
    (net (code "86") (name "Net-(D1001-A2)") (class "Default")
      (node (ref "D1001") (pin "2") (pinfunction "A2_2") (pintype "passive"))
      (node (ref "U$1001") (pin "8") (pinfunction "OUT_8") (pintype "bidirectional"))
    )
    (net (code "87") (name "Net-(J201-1)") (class "Default")
      (node (ref "J201") (pin "P$1") (pinfunction "1_P$1") (pintype "passive"))
      (node (ref "L201") (pin "P$2") (pinfunction "P$2_P$2") (pintype "bidirectional"))
      (node (ref "U$201") (pin "C") (pinfunction "C_C") (pintype "passive"))
    )
    (net (code "88") (name "Net-(J202-1)") (class "Default")
      (node (ref "J202") (pin "P$1") (pinfunction "1_P$1") (pintype "passive"))
      (node (ref "L202") (pin "P$2") (pinfunction "P$2_P$2") (pintype "bidirectional"))
      (node (ref "U$202") (pin "C") (pinfunction "C_C") (pintype "passive"))
    )
    (net (code "89") (name "Net-(J203-1)") (class "Default")
      (node (ref "J203") (pin "P$1") (pinfunction "1_P$1") (pintype "passive"))
      (node (ref "J204") (pin "P$1") (pinfunction "1_P$1") (pintype "passive"))
      (node (ref "L203") (pin "P$2") (pinfunction "P$2_P$2") (pintype "bidirectional"))
      (node (ref "U$203") (pin "C") (pinfunction "C_C") (pintype "passive"))
    )
    (net (code "90") (name "Net-(J203-4)") (class "Default")
      (node (ref "J203") (pin "P$4") (pinfunction "4_P$4") (pintype "passive"))
      (node (ref "R12") (pin "P$2") (pinfunction "2_P$2") (pintype "passive"))
    )
    (net (code "91") (name "Net-(J203-5)") (class "Default")
      (node (ref "J203") (pin "P$5") (pinfunction "5_P$5") (pintype "passive"))
      (node (ref "R13") (pin "P$2") (pinfunction "2_P$2") (pintype "passive"))
    )
    (net (code "92") (name "Net-(J301-2)") (class "Default")
      (node (ref "J301") (pin "D-") (pinfunction "2_D-") (pintype "bidirectional"))
      (node (ref "J302") (pin "P$3") (pinfunction "3_P$3") (pintype "passive"))
      (node (ref "U$301") (pin "1") (pinfunction "D1I_1") (pintype "bidirectional"))
    )
    (net (code "93") (name "Net-(J301-3)") (class "Default")
      (node (ref "J301") (pin "D+") (pinfunction "3_D+") (pintype "bidirectional"))
      (node (ref "J302") (pin "P$2") (pinfunction "2_P$2") (pintype "passive"))
      (node (ref "U$301") (pin "3") (pinfunction "D2I_3") (pintype "bidirectional"))
    )
    (net (code "94") (name "Net-(J401-1)") (class "Default")
      (node (ref "J401") (pin "P$1") (pinfunction "1_P$1") (pintype "passive"))
      (node (ref "J402") (pin "P$1") (pinfunction "1_P$1") (pintype "passive"))
      (node (ref "L401") (pin "P$2") (pinfunction "P$2_P$2") (pintype "bidirectional"))
      (node (ref "U$401") (pin "C") (pinfunction "C_C") (pintype "passive"))
    )
    (net (code "95") (name "Net-(J401-2)") (class "Default")
      (node (ref "J401") (pin "P$2") (pinfunction "2_P$2") (pintype "passive"))
      (node (ref "R404") (pin "P$2") (pinfunction "2_P$2") (pintype "passive"))
    )
    (net (code "96") (name "Net-(J401-3)") (class "Default")
      (node (ref "J401") (pin "P$3") (pinfunction "3_P$3") (pintype "passive"))
      (node (ref "R405") (pin "P$2") (pinfunction "2_P$2") (pintype "passive"))
    )
    (net (code "97") (name "Net-(J403-1)") (class "Default")
      (node (ref "J403") (pin "P$1") (pinfunction "1_P$1") (pintype "passive"))
      (node (ref "L402") (pin "P$2") (pinfunction "P$2_P$2") (pintype "bidirectional"))
      (node (ref "U$402") (pin "C") (pinfunction "C_C") (pintype "passive"))
    )
    (net (code "98") (name "Net-(J404-1)") (class "Default")
      (node (ref "J404") (pin "P$1") (pinfunction "1_P$1") (pintype "passive"))
      (node (ref "L404") (pin "P$2") (pinfunction "P$2_P$2") (pintype "bidirectional"))
      (node (ref "U$403") (pin "C") (pinfunction "C_C") (pintype "passive"))
    )
    (net (code "99") (name "Net-(J404-2)") (class "Default")
      (node (ref "J404") (pin "P$2") (pinfunction "2_P$2") (pintype "passive"))
      (node (ref "R407") (pin "P$2") (pinfunction "2_P$2") (pintype "passive"))
    )
    (net (code "100") (name "Net-(J404-4)") (class "Default")
      (node (ref "J404") (pin "P$4") (pinfunction "4_P$4") (pintype "passive"))
      (node (ref "R408") (pin "P$2") (pinfunction "2_P$2") (pintype "passive"))
    )
    (net (code "101") (name "Net-(J405-1)") (class "Default")
      (node (ref "J405") (pin "P$1") (pinfunction "1_P$1") (pintype "passive"))
      (node (ref "L403") (pin "P$2") (pinfunction "P$2_P$2") (pintype "bidirectional"))
      (node (ref "U$404") (pin "C") (pinfunction "C_C") (pintype "passive"))
    )
    (net (code "102") (name "Net-(J601-3)") (class "Default")
      (node (ref "J601") (pin "P$3") (pinfunction "3_P$3") (pintype "passive"))
      (node (ref "L601") (pin "P$1") (pinfunction "P$1_P$1") (pintype "bidirectional"))
    )
    (net (code "103") (name "Net-(J601-4)") (class "Default")
      (node (ref "J601") (pin "P$4") (pinfunction "4_P$4") (pintype "passive"))
      (node (ref "L602") (pin "P$1") (pinfunction "P$1_P$1") (pintype "bidirectional"))
    )
    (net (code "104") (name "Net-(J702-2)") (class "Default")
      (node (ref "J702") (pin "P$2") (pinfunction "2_P$2") (pintype "passive"))
      (node (ref "R710") (pin "P$1") (pinfunction "1_P$1") (pintype "passive"))
    )
    (net (code "105") (name "Net-(J901A-S)") (class "Default")
      (node (ref "J901") (pin "1") (pinfunction "S_1") (pintype "passive"))
      (node (ref "R909") (pin "P$2") (pinfunction "2_P$2") (pintype "passive"))
    )
    (net (code "106") (name "Net-(J901B-S)") (class "Default")
      (node (ref "J901") (pin "10") (pinfunction "S_10") (pintype "passive"))
      (node (ref "R914") (pin "P$2") (pinfunction "2_P$2") (pintype "passive"))
    )
    (net (code "107") (name "Net-(J901C-S)") (class "Default")
      (node (ref "J901") (pin "13") (pinfunction "S_13") (pintype "passive"))
      (node (ref "R906") (pin "P$2") (pinfunction "2_P$2") (pintype "passive"))
    )
    (net (code "108") (name "Net-(J901D-S)") (class "Default")
      (node (ref "J901") (pin "16") (pinfunction "S_16") (pintype "passive"))
      (node (ref "R915") (pin "P$2") (pinfunction "2_P$2") (pintype "passive"))
    )
    (net (code "109") (name "Net-(J901E-S)") (class "Default")
      (node (ref "J901") (pin "19") (pinfunction "S_19") (pintype "passive"))
      (node (ref "R907") (pin "P$2") (pinfunction "2_P$2") (pintype "passive"))
    )
    (net (code "110") (name "Net-(J901G-S)") (class "Default")
      (node (ref "J901") (pin "22") (pinfunction "S_22") (pintype "passive"))
      (node (ref "R916") (pin "P$2") (pinfunction "2_P$2") (pintype "passive"))
    )
    (net (code "111") (name "Net-(J901H-S)") (class "Default")
      (node (ref "J901") (pin "25") (pinfunction "S_25") (pintype "passive"))
      (node (ref "R908") (pin "P$2") (pinfunction "2_P$2") (pintype "passive"))
    )
    (net (code "112") (name "Net-(J901I-S)") (class "Default")
      (node (ref "J901") (pin "28") (pinfunction "S_28") (pintype "passive"))
      (node (ref "R917") (pin "P$2") (pinfunction "2_P$2") (pintype "passive"))
    )
    (net (code "113") (name "Net-(J901J-S)") (class "Default")
      (node (ref "J901") (pin "31") (pinfunction "S_31") (pintype "passive"))
      (node (ref "R902") (pin "P$2") (pinfunction "2_P$2") (pintype "passive"))
    )
    (net (code "114") (name "Net-(J901K-S)") (class "Default")
      (node (ref "J901") (pin "34") (pinfunction "S_34") (pintype "passive"))
      (node (ref "R911") (pin "P$2") (pinfunction "2_P$2") (pintype "passive"))
    )
    (net (code "115") (name "Net-(J901L-S)") (class "Default")
      (node (ref "J901") (pin "37") (pinfunction "S_37") (pintype "passive"))
      (node (ref "R903") (pin "P$2") (pinfunction "2_P$2") (pintype "passive"))
    )
    (net (code "116") (name "Net-(J901M-S)") (class "Default")
      (node (ref "J901") (pin "4") (pinfunction "S_4") (pintype "passive"))
      (node (ref "R910") (pin "P$2") (pinfunction "2_P$2") (pintype "passive"))
    )
    (net (code "117") (name "Net-(J901N-S)") (class "Default")
      (node (ref "J901") (pin "40") (pinfunction "S_40") (pintype "passive"))
      (node (ref "R912") (pin "P$2") (pinfunction "2_P$2") (pintype "passive"))
    )
    (net (code "118") (name "Net-(J901O-S)") (class "Default")
      (node (ref "J901") (pin "43") (pinfunction "S_43") (pintype "passive"))
      (node (ref "R904") (pin "P$2") (pinfunction "2_P$2") (pintype "passive"))
    )
    (net (code "119") (name "Net-(J901P-S)") (class "Default")
      (node (ref "J901") (pin "46") (pinfunction "S_46") (pintype "passive"))
      (node (ref "R913") (pin "P$2") (pinfunction "2_P$2") (pintype "passive"))
    )
    (net (code "120") (name "Net-(J901Q-S)") (class "Default")
      (node (ref "J901") (pin "7") (pinfunction "S_7") (pintype "passive"))
      (node (ref "R905") (pin "P$2") (pinfunction "2_P$2") (pintype "passive"))
    )
    (net (code "121") (name "Net-(L701-2)") (class "Default")
      (node (ref "L701") (pin "P$2") (pinfunction "2_P$2") (pintype "passive"))
      (node (ref "U702") (pin "5") (pinfunction "SW_5") (pintype "passive"))
    )
    (net (code "122") (name "Net-(R1-2)") (class "Default")
      (node (ref "R1") (pin "P$2") (pinfunction "2_P$2") (pintype "passive"))
      (node (ref "R2") (pin "P$1") (pinfunction "1_P$1") (pintype "passive"))
      (node (ref "U$2") (pin "P$1") (pinfunction "UV1_P$1") (pintype "bidirectional"))
    )
    (net (code "123") (name "Net-(R2-2)") (class "Default")
      (node (ref "R2") (pin "P$2") (pinfunction "2_P$2") (pintype "passive"))
      (node (ref "R5") (pin "P$1") (pinfunction "1_P$1") (pintype "passive"))
      (node (ref "U$2") (pin "P$2") (pinfunction "OV1_P$2") (pintype "bidirectional"))
    )
    (net (code "124") (name "Net-(R3-1)") (class "Default")
      (node (ref "R3") (pin "P$1") (pinfunction "1_P$1") (pintype "passive"))
      (node (ref "R707") (pin "P$2") (pinfunction "2_P$2") (pintype "passive"))
    )
    (net (code "125") (name "Net-(R3-2)") (class "Default")
      (node (ref "LED701") (pin "C") (pinfunction "C_C") (pintype "passive"))
      (node (ref "R3") (pin "P$2") (pinfunction "2_P$2") (pintype "passive"))
    )
    (net (code "126") (name "Net-(R4-1)") (class "Default")
      (node (ref "R4") (pin "P$1") (pinfunction "1_P$1") (pintype "passive"))
      (node (ref "R709") (pin "P$2") (pinfunction "2_P$2") (pintype "passive"))
    )
    (net (code "127") (name "Net-(R4-2)") (class "Default")
      (node (ref "LED703") (pin "C") (pinfunction "C_C") (pintype "passive"))
      (node (ref "R4") (pin "P$2") (pinfunction "2_P$2") (pintype "passive"))
    )
    (net (code "128") (name "Net-(R6-2)") (class "Default")
      (node (ref "R6") (pin "P$2") (pinfunction "2_P$2") (pintype "passive"))
      (node (ref "R7") (pin "P$1") (pinfunction "1_P$1") (pintype "passive"))
      (node (ref "U$2") (pin "P$5") (pinfunction "UV3_P$5") (pintype "bidirectional"))
    )
    (net (code "129") (name "Net-(R7-2)") (class "Default")
      (node (ref "R7") (pin "P$2") (pinfunction "2_P$2") (pintype "passive"))
      (node (ref "R8") (pin "P$1") (pinfunction "1_P$1") (pintype "passive"))
      (node (ref "U$2") (pin "P$6") (pinfunction "OV3_P$6") (pintype "bidirectional"))
    )
    (net (code "130") (name "Net-(R10-1)") (class "Default")
      (node (ref "R10") (pin "P$1") (pinfunction "1_P$1") (pintype "passive"))
      (node (ref "R9") (pin "P$2") (pinfunction "2_P$2") (pintype "passive"))
      (node (ref "U$2") (pin "P$3") (pinfunction "UV2_P$3") (pintype "bidirectional"))
    )
    (net (code "131") (name "Net-(R10-2)") (class "Default")
      (node (ref "R10") (pin "P$2") (pinfunction "2_P$2") (pintype "passive"))
      (node (ref "R11") (pin "P$1") (pinfunction "1_P$1") (pintype "passive"))
      (node (ref "U$2") (pin "P$4") (pinfunction "OV2_P$4") (pintype "bidirectional"))
    )
    (net (code "132") (name "Net-(R101-1)") (class "Default")
      (node (ref "R101") (pin "P$1") (pinfunction "1_P$1") (pintype "passive"))
      (node (ref "U101") (pin "69") (pinfunction "PA10_69") (pintype "bidirectional"))
    )
    (net (code "133") (name "Net-(R102-1)") (class "Default")
      (node (ref "R102") (pin "P$1") (pinfunction "1_P$1") (pintype "passive"))
      (node (ref "U101") (pin "37") (pinfunction "PB2_37") (pintype "bidirectional"))
    )
    (net (code "134") (name "Net-(R201-1)") (class "Default")
      (node (ref "R201") (pin "P$1") (pinfunction "1_P$1") (pintype "passive"))
      (node (ref "U201") (pin "20") (pinfunction "B1_20") (pintype "bidirectional"))
    )
    (net (code "135") (name "Net-(R202-1)") (class "Default")
      (node (ref "R202") (pin "P$1") (pinfunction "1_P$1") (pintype "passive"))
      (node (ref "U201") (pin "17") (pinfunction "B3_17") (pintype "bidirectional"))
    )
    (net (code "136") (name "Net-(R203-1)") (class "Default")
      (node (ref "R203") (pin "P$1") (pinfunction "1_P$1") (pintype "passive"))
      (node (ref "U201") (pin "15") (pinfunction "B5_15") (pintype "bidirectional"))
    )
    (net (code "137") (name "Net-(R204-1)") (class "Default")
      (node (ref "R204") (pin "P$1") (pinfunction "1_P$1") (pintype "passive"))
      (node (ref "U201") (pin "13") (pinfunction "B7_13") (pintype "bidirectional"))
    )
    (net (code "138") (name "Net-(R205-1)") (class "Default")
      (node (ref "R205") (pin "P$1") (pinfunction "1_P$1") (pintype "passive"))
      (node (ref "U202") (pin "17") (pinfunction "B3_17") (pintype "bidirectional"))
    )
    (net (code "139") (name "Net-(R206-1)") (class "Default")
      (node (ref "R206") (pin "P$1") (pinfunction "1_P$1") (pintype "passive"))
      (node (ref "U202") (pin "15") (pinfunction "B5_15") (pintype "bidirectional"))
    )
    (net (code "140") (name "Net-(R207-1)") (class "Default")
      (node (ref "R207") (pin "P$1") (pinfunction "1_P$1") (pintype "passive"))
      (node (ref "U202") (pin "13") (pinfunction "B7_13") (pintype "bidirectional"))
    )
    (net (code "141") (name "Net-(R208-1)") (class "Default")
      (node (ref "R208") (pin "P$1") (pinfunction "1_P$1") (pintype "passive"))
      (node (ref "U201") (pin "18") (pinfunction "B2_18") (pintype "bidirectional"))
    )
    (net (code "142") (name "Net-(R209-1)") (class "Default")
      (node (ref "R209") (pin "P$1") (pinfunction "1_P$1") (pintype "passive"))
      (node (ref "U201") (pin "16") (pinfunction "B4_16") (pintype "bidirectional"))
    )
    (net (code "143") (name "Net-(R210-1)") (class "Default")
      (node (ref "R210") (pin "P$1") (pinfunction "1_P$1") (pintype "passive"))
      (node (ref "U201") (pin "14") (pinfunction "B6_14") (pintype "bidirectional"))
    )
    (net (code "144") (name "Net-(R211-1)") (class "Default")
      (node (ref "R211") (pin "P$1") (pinfunction "1_P$1") (pintype "passive"))
      (node (ref "U201") (pin "12") (pinfunction "B8_12") (pintype "bidirectional"))
    )
    (net (code "145") (name "Net-(R212-1)") (class "Default")
      (node (ref "R212") (pin "P$1") (pinfunction "1_P$1") (pintype "passive"))
      (node (ref "U202") (pin "16") (pinfunction "B4_16") (pintype "bidirectional"))
    )
    (net (code "146") (name "Net-(R213-1)") (class "Default")
      (node (ref "R213") (pin "P$1") (pinfunction "1_P$1") (pintype "passive"))
      (node (ref "U202") (pin "14") (pinfunction "B6_14") (pintype "bidirectional"))
    )
    (net (code "147") (name "Net-(R214-1)") (class "Default")
      (node (ref "R214") (pin "P$1") (pinfunction "1_P$1") (pintype "passive"))
      (node (ref "U202") (pin "12") (pinfunction "B8_12") (pintype "bidirectional"))
    )
    (net (code "148") (name "Net-(R602-1)") (class "Default")
      (node (ref "R602") (pin "P$1") (pinfunction "1_P$1") (pintype "passive"))
      (node (ref "U$602") (pin "7") (pinfunction "ILIM_7") (pintype "bidirectional"))
    )
    (net (code "149") (name "Net-(R604-2)") (class "Default")
      (node (ref "L601") (pin "P$2") (pinfunction "P$2_P$2") (pintype "bidirectional"))
      (node (ref "R604") (pin "P$2") (pinfunction "2_P$2") (pintype "passive"))
    )
    (net (code "150") (name "Net-(R605-2)") (class "Default")
      (node (ref "L602") (pin "P$2") (pinfunction "P$2_P$2") (pintype "bidirectional"))
      (node (ref "R605") (pin "P$2") (pinfunction "2_P$2") (pintype "passive"))
    )
    (net (code "151") (name "Net-(R606-1)") (class "Default")
      (node (ref "R606") (pin "P$1") (pinfunction "1_P$1") (pintype "passive"))
      (node (ref "U$604") (pin "7") (pinfunction "ILIM_7") (pintype "bidirectional"))
    )
    (net (code "152") (name "Net-(R701-1)") (class "Default")
      (node (ref "R701") (pin "P$1") (pinfunction "1_P$1") (pintype "passive"))
      (node (ref "U702") (pin "7") (pinfunction "+IN_7") (pintype "input"))
    )
    (net (code "153") (name "Net-(R702-1)") (class "Default")
      (node (ref "R702") (pin "P$1") (pinfunction "1_P$1") (pintype "passive"))
      (node (ref "R703") (pin "P$2") (pinfunction "2_P$2") (pintype "passive"))
      (node (ref "U702") (pin "8") (pinfunction "-IN_8") (pintype "input"))
    )
    (net (code "154") (name "Net-(R704-2)") (class "Default")
      (node (ref "R704") (pin "P$2") (pinfunction "2_P$2") (pintype "passive"))
      (node (ref "U701") (pin "6") (pinfunction "REXT_6") (pintype "bidirectional"))
    )
    (net (code "155") (name "Net-(R705-2)") (class "Default")
      (node (ref "R705") (pin "P$2") (pinfunction "2_P$2") (pintype "passive"))
      (node (ref "R706") (pin "P$1") (pinfunction "1_P$1") (pintype "passive"))
      (node (ref "U702") (pin "2") (pinfunction "FB_2") (pintype "bidirectional"))
    )
    (net (code "156") (name "Net-(R708-2)") (class "Default")
      (node (ref "LED702") (pin "C") (pinfunction "C_C") (pintype "passive"))
      (node (ref "R708") (pin "P$2") (pinfunction "2_P$2") (pintype "passive"))
    )
    (net (code "157") (name "Net-(R711-2)") (class "Default")
      (node (ref "LED704") (pin "C") (pinfunction "C_C") (pintype "passive"))
      (node (ref "R711") (pin "P$2") (pinfunction "2_P$2") (pintype "passive"))
    )
    (net (code "158") (name "Net-(R712-2)") (class "Default")
      (node (ref "LED705") (pin "C") (pinfunction "C_C") (pintype "passive"))
      (node (ref "R712") (pin "P$2") (pinfunction "2_P$2") (pintype "passive"))
    )
    (net (code "159") (name "Net-(R802-1)") (class "Default")
      (node (ref "R802") (pin "P$1") (pinfunction "1_P$1") (pintype "passive"))
      (node (ref "U801") (pin "20") (pinfunction "PB2_20") (pintype "bidirectional"))
    )
    (net (code "160") (name "Net-(R803-1)") (class "Default")
      (node (ref "R803") (pin "P$1") (pinfunction "1_P$1") (pintype "passive"))
      (node (ref "U801") (pin "12") (pinfunction "PA2_12") (pintype "bidirectional"))
    )
    (net (code "161") (name "Net-(R804-1)") (class "Default")
      (node (ref "R804") (pin "P$1") (pinfunction "1_P$1") (pintype "passive"))
      (node (ref "U801") (pin "13") (pinfunction "PA3_13") (pintype "bidirectional"))
    )
    (net (code "162") (name "Net-(R901-2)") (class "Default")
      (node (ref "R901") (pin "P$2") (pinfunction "2_P$2") (pintype "passive"))
      (node (ref "R910") (pin "P$1") (pinfunction "1_P$1") (pintype "passive"))
      (node (ref "U$902") (pin "C") (pinfunction "C_C") (pintype "passive"))
      (node (ref "U903") (pin "3") (pinfunction "2Y_3") (pintype "bidirectional"))
    )
    (net (code "163") (name "Net-(R902-1)") (class "Default")
      (node (ref "R902") (pin "P$1") (pinfunction "1_P$1") (pintype "passive"))
      (node (ref "U901") (pin "20") (pinfunction "B1_20") (pintype "bidirectional"))
    )
    (net (code "164") (name "Net-(R903-1)") (class "Default")
      (node (ref "R903") (pin "P$1") (pinfunction "1_P$1") (pintype "passive"))
      (node (ref "U901") (pin "17") (pinfunction "B3_17") (pintype "bidirectional"))
    )
    (net (code "165") (name "Net-(R904-1)") (class "Default")
      (node (ref "R904") (pin "P$1") (pinfunction "1_P$1") (pintype "passive"))
      (node (ref "U901") (pin "15") (pinfunction "B5_15") (pintype "bidirectional"))
    )
    (net (code "166") (name "Net-(R905-1)") (class "Default")
      (node (ref "R905") (pin "P$1") (pinfunction "1_P$1") (pintype "passive"))
      (node (ref "U902") (pin "20") (pinfunction "B1_20") (pintype "bidirectional"))
    )
    (net (code "167") (name "Net-(R906-1)") (class "Default")
      (node (ref "R906") (pin "P$1") (pinfunction "1_P$1") (pintype "passive"))
      (node (ref "U902") (pin "17") (pinfunction "B3_17") (pintype "bidirectional"))
    )
    (net (code "168") (name "Net-(R907-1)") (class "Default")
      (node (ref "R907") (pin "P$1") (pinfunction "1_P$1") (pintype "passive"))
      (node (ref "U902") (pin "15") (pinfunction "B5_15") (pintype "bidirectional"))
    )
    (net (code "169") (name "Net-(R908-1)") (class "Default")
      (node (ref "R908") (pin "P$1") (pinfunction "1_P$1") (pintype "passive"))
      (node (ref "U902") (pin "13") (pinfunction "B7_13") (pintype "bidirectional"))
    )
    (net (code "170") (name "Net-(R911-1)") (class "Default")
      (node (ref "R911") (pin "P$1") (pinfunction "1_P$1") (pintype "passive"))
      (node (ref "U901") (pin "18") (pinfunction "B2_18") (pintype "bidirectional"))
    )
    (net (code "171") (name "Net-(R912-1)") (class "Default")
      (node (ref "R912") (pin "P$1") (pinfunction "1_P$1") (pintype "passive"))
      (node (ref "U901") (pin "16") (pinfunction "B4_16") (pintype "bidirectional"))
    )
    (net (code "172") (name "Net-(R913-1)") (class "Default")
      (node (ref "R913") (pin "P$1") (pinfunction "1_P$1") (pintype "passive"))
      (node (ref "U901") (pin "14") (pinfunction "B6_14") (pintype "bidirectional"))
    )
    (net (code "173") (name "Net-(R914-1)") (class "Default")
      (node (ref "R914") (pin "P$1") (pinfunction "1_P$1") (pintype "passive"))
      (node (ref "U902") (pin "18") (pinfunction "B2_18") (pintype "bidirectional"))
    )
    (net (code "174") (name "Net-(R915-1)") (class "Default")
      (node (ref "R915") (pin "P$1") (pinfunction "1_P$1") (pintype "passive"))
      (node (ref "U902") (pin "16") (pinfunction "B4_16") (pintype "bidirectional"))
    )
    (net (code "175") (name "Net-(R916-1)") (class "Default")
      (node (ref "R916") (pin "P$1") (pinfunction "1_P$1") (pintype "passive"))
      (node (ref "U902") (pin "14") (pinfunction "B6_14") (pintype "bidirectional"))
    )
    (net (code "176") (name "Net-(R917-1)") (class "Default")
      (node (ref "R917") (pin "P$1") (pinfunction "1_P$1") (pintype "passive"))
      (node (ref "U902") (pin "12") (pinfunction "B8_12") (pintype "bidirectional"))
    )
    (net (code "177") (name "Net-(R918-2)") (class "Default")
      (node (ref "R918") (pin "P$2") (pinfunction "2_P$2") (pintype "passive"))
      (node (ref "R922") (pin "P$1") (pinfunction "1_P$1") (pintype "passive"))
    )
    (net (code "178") (name "Net-(R1001-2)") (class "Default")
      (node (ref "R1001") (pin "P$2") (pinfunction "2_P$2") (pintype "passive"))
      (node (ref "U$1001") (pin "7") (pinfunction "ILIM_7") (pintype "bidirectional"))
    )
    (net (code "179") (name "Net-(U$2-G1)") (class "Default")
      (node (ref "U$2") (pin "P$17") (pinfunction "G1_P$17") (pintype "bidirectional"))
      (node (ref "U$3") (pin "P$2") (pinfunction "G_P$2") (pintype "passive"))
      (node (ref "U$3") (pin "P$4") (pinfunction "G_P$4") (pintype "passive"))
    )
    (net (code "180") (name "Net-(U$2-G2)") (class "Default")
      (node (ref "U$2") (pin "P$15") (pinfunction "G2_P$15") (pintype "bidirectional"))
      (node (ref "U$4") (pin "P$2") (pinfunction "G_P$2") (pintype "passive"))
      (node (ref "U$4") (pin "P$4") (pinfunction "G_P$4") (pintype "passive"))
    )
    (net (code "181") (name "Net-(U$2-G3)") (class "Default")
      (node (ref "U$2") (pin "P$13") (pinfunction "G3_P$13") (pintype "bidirectional"))
      (node (ref "U$5") (pin "P$2") (pinfunction "G_P$2") (pintype "passive"))
      (node (ref "U$5") (pin "P$4") (pinfunction "G_P$4") (pintype "passive"))
    )
    (net (code "182") (name "Net-(U$2-VS1)") (class "Default")
      (node (ref "U$2") (pin "P$18") (pinfunction "VS1_P$18") (pintype "bidirectional"))
      (node (ref "U$3") (pin "P$1") (pinfunction "S_P$1") (pintype "passive"))
      (node (ref "U$3") (pin "P$3") (pinfunction "S_P$3") (pintype "passive"))
    )
    (net (code "183") (name "Net-(U$2-VS2)") (class "Default")
      (node (ref "U$2") (pin "P$16") (pinfunction "VS2_P$16") (pintype "bidirectional"))
      (node (ref "U$4") (pin "P$1") (pinfunction "S_P$1") (pintype "passive"))
      (node (ref "U$4") (pin "P$3") (pinfunction "S_P$3") (pintype "passive"))
    )
    (net (code "184") (name "Net-(U$2-VS3)") (class "Default")
      (node (ref "U$2") (pin "P$14") (pinfunction "VS3_P$14") (pintype "bidirectional"))
      (node (ref "U$5") (pin "P$1") (pinfunction "S_P$1") (pintype "passive"))
      (node (ref "U$5") (pin "P$3") (pinfunction "S_P$3") (pintype "passive"))
    )
    (net (code "185") (name "Net-(U701-OUT0)") (class "Default")
      (node (ref "U701") (pin "9") (pinfunction "OUT0_9") (pintype "open_collector"))
      (node (ref "U703") (pin "C1") (pinfunction "C_C1") (pintype "passive"))
    )
    (net (code "186") (name "Net-(U701-OUT1)") (class "Default")
      (node (ref "U701") (pin "8") (pinfunction "OUT1_8") (pintype "open_collector"))
      (node (ref "U703") (pin "C2") (pinfunction "C_C2") (pintype "passive"))
    )
    (net (code "187") (name "Net-(U701-OUT2)") (class "Default")
      (node (ref "U701") (pin "7") (pinfunction "OUT2_7") (pintype "open_collector"))
      (node (ref "U703") (pin "C3") (pinfunction "C_C3") (pintype "passive"))
    )
    (net (code "188") (name "OTG_FS_DM") (class "Default")
      (node (ref "U$301") (pin "6") (pinfunction "D1O_6") (pintype "bidirectional"))
      (node (ref "U101") (pin "70") (pinfunction "PA11_70") (pintype "bidirectional"))
    )
    (net (code "189") (name "OTG_FS_DP") (class "Default")
      (node (ref "U$301") (pin "4") (pinfunction "D2O_4") (pintype "bidirectional"))
      (node (ref "U101") (pin "71") (pinfunction "PA12_71") (pintype "bidirectional"))
    )
    (net (code "190") (name "PPM_INPUT") (class "Default")
      (node (ref "R909") (pin "P$1") (pinfunction "1_P$1") (pintype "passive"))
      (node (ref "U$901") (pin "C") (pinfunction "C_C") (pintype "passive"))
      (node (ref "U801") (pin "29") (pinfunction "PA8_29") (pintype "bidirectional"))
      (node (ref "U903") (pin "2") (pinfunction "1A_2") (pintype "bidirectional"))
    )
    (net (code "191") (name "PRESSURE_SENS") (class "Default")
      (node (ref "C401") (pin "P$1") (pinfunction "1_P$1") (pintype "passive"))
      (node (ref "R403") (pin "P$2") (pinfunction "2_P$2") (pintype "passive"))
      (node (ref "R406") (pin "P$1") (pinfunction "1_P$1") (pintype "passive"))
      (node (ref "U101") (pin "34") (pinfunction "PC5_34") (pintype "bidirectional"))
    )
    (net (code "192") (name "PRESSURE_SENS_IN") (class "Default")
      (node (ref "ADC_PR") (pin "P$1") (pinfunction "P$1_P$1") (pintype "passive"))
      (node (ref "J402") (pin "P$2") (pinfunction "2_P$2") (pintype "passive"))
      (node (ref "R406") (pin "P$2") (pinfunction "2_P$2") (pintype "passive"))
    )
    (net (code "193") (name "RSSI_IN") (class "Default")
      (node (ref "R901") (pin "P$1") (pinfunction "1_P$1") (pintype "passive"))
      (node (ref "U801") (pin "15") (pinfunction "PA5_15") (pintype "bidirectional"))
      (node (ref "U801") (pin "33") (pinfunction "PA12_33") (pintype "bidirectional"))
    )
    (net (code "194") (name "SAFETY") (class "Default")
      (node (ref "J702") (pin "P$3") (pinfunction "3_P$3") (pintype "passive"))
      (node (ref "R713") (pin "P$1") (pinfunction "1_P$1") (pintype "passive"))
      (node (ref "U801") (pin "41") (pinfunction "PB5_41") (pintype "bidirectional"))
    )
    (net (code "195") (name "SBUS_INPUT") (class "Default")
      (node (ref "U801") (pin "22") (pinfunction "PB11_22") (pintype "bidirectional"))
      (node (ref "U903") (pin "6") (pinfunction "1Y_6") (pintype "bidirectional"))
    )
    (net (code "196") (name "SBUS_OUTPUT") (class "Default")
      (node (ref "U801") (pin "21") (pinfunction "PB10_21") (pintype "bidirectional"))
      (node (ref "U903") (pin "5") (pinfunction "2A_5") (pintype "bidirectional"))
    )
    (net (code "197") (name "SDIO_CK") (class "Default")
      (node (ref "U101") (pin "80") (pinfunction "PC12_80") (pintype "bidirectional"))
      (node (ref "U301") (pin "5") (pinfunction "CLK_5") (pintype "bidirectional"))
    )
    (net (code "198") (name "SDIO_CMD") (class "Default")
      (node (ref "R303") (pin "P$1") (pinfunction "1_P$1") (pintype "passive"))
      (node (ref "U101") (pin "83") (pinfunction "PD2_83") (pintype "bidirectional"))
      (node (ref "U301") (pin "3") (pinfunction "CMD_3") (pintype "bidirectional"))
    )
    (net (code "199") (name "SDIO_D0") (class "Default")
      (node (ref "R304") (pin "P$1") (pinfunction "1_P$1") (pintype "passive"))
      (node (ref "U101") (pin "65") (pinfunction "PC8_65") (pintype "bidirectional"))
      (node (ref "U301") (pin "7") (pinfunction "D0_7") (pintype "bidirectional"))
    )
    (net (code "200") (name "SDIO_D1") (class "Default")
      (node (ref "R305") (pin "P$1") (pinfunction "1_P$1") (pintype "passive"))
      (node (ref "U101") (pin "66") (pinfunction "PC9_66") (pintype "bidirectional"))
      (node (ref "U301") (pin "8") (pinfunction "D1_8") (pintype "bidirectional"))
    )
    (net (code "201") (name "SDIO_D2") (class "Default")
      (node (ref "R301") (pin "P$1") (pinfunction "1_P$1") (pintype "passive"))
      (node (ref "U101") (pin "78") (pinfunction "PC10_78") (pintype "bidirectional"))
      (node (ref "U301") (pin "1") (pinfunction "D2_1") (pintype "bidirectional"))
    )
    (net (code "202") (name "SDIO_D3") (class "Default")
      (node (ref "R302") (pin "P$1") (pinfunction "1_P$1") (pintype "passive"))
      (node (ref "U101") (pin "79") (pinfunction "PC11_79") (pintype "bidirectional"))
      (node (ref "U301") (pin "2") (pinfunction "D3_2") (pintype "bidirectional"))
    )
    (net (code "203") (name "SERIAL1_CTS") (class "Default")
      (node (ref "J201") (pin "P$4") (pinfunction "4_P$4") (pintype "passive"))
      (node (ref "R211") (pin "P$2") (pinfunction "2_P$2") (pintype "passive"))
    )
    (net (code "204") (name "SERIAL1_RTS") (class "Default")
      (node (ref "J201") (pin "P$5") (pinfunction "5_P$5") (pintype "passive"))
      (node (ref "R204") (pin "P$2") (pinfunction "2_P$2") (pintype "passive"))
    )
    (net (code "205") (name "SERIAL1_RX") (class "Default")
      (node (ref "J201") (pin "P$3") (pinfunction "3_P$3") (pintype "passive"))
      (node (ref "R203") (pin "P$2") (pinfunction "2_P$2") (pintype "passive"))
      (node (ref "S1RX") (pin "P$1") (pinfunction "P$1_P$1") (pintype "passive"))
    )
    (net (code "206") (name "SERIAL1_TX") (class "Default")
      (node (ref "J201") (pin "P$2") (pinfunction "2_P$2") (pintype "passive"))
      (node (ref "R210") (pin "P$2") (pinfunction "2_P$2") (pintype "passive"))
      (node (ref "S1TX") (pin "P$1") (pinfunction "P$1_P$1") (pintype "passive"))
    )
    (net (code "207") (name "SERIAL2_CTS") (class "Default")
      (node (ref "J202") (pin "P$4") (pinfunction "4_P$4") (pintype "passive"))
      (node (ref "R208") (pin "P$2") (pinfunction "2_P$2") (pintype "passive"))
    )
    (net (code "208") (name "SERIAL2_RTS") (class "Default")
      (node (ref "J202") (pin "P$5") (pinfunction "5_P$5") (pintype "passive"))
      (node (ref "R201") (pin "P$2") (pinfunction "2_P$2") (pintype "passive"))
    )
    (net (code "209") (name "SERIAL2_RX") (class "Default")
      (node (ref "J202") (pin "P$3") (pinfunction "3_P$3") (pintype "passive"))
      (node (ref "R202") (pin "P$2") (pinfunction "2_P$2") (pintype "passive"))
      (node (ref "S2RX") (pin "P$1") (pinfunction "P$1_P$1") (pintype "passive"))
    )
    (net (code "210") (name "SERIAL2_TX") (class "Default")
      (node (ref "J202") (pin "P$2") (pinfunction "2_P$2") (pintype "passive"))
      (node (ref "R209") (pin "P$2") (pinfunction "2_P$2") (pintype "passive"))
      (node (ref "S2TX") (pin "P$1") (pinfunction "P$1_P$1") (pintype "passive"))
    )
    (net (code "211") (name "SERIAL3_RX") (class "Default")
      (node (ref "J203") (pin "P$3") (pinfunction "3_P$3") (pintype "passive"))
      (node (ref "R207") (pin "P$2") (pinfunction "2_P$2") (pintype "passive"))
      (node (ref "S3RX") (pin "P$1") (pinfunction "P$1_P$1") (pintype "passive"))
    )
    (net (code "212") (name "SERIAL3_TX") (class "Default")
      (node (ref "J203") (pin "P$2") (pinfunction "2_P$2") (pintype "passive"))
      (node (ref "R214") (pin "P$2") (pinfunction "2_P$2") (pintype "passive"))
      (node (ref "S3TX") (pin "P$1") (pinfunction "P$1_P$1") (pintype "passive"))
    )
    (net (code "213") (name "SERIAL4_RX") (class "Default")
      (node (ref "J204") (pin "P$3") (pinfunction "3_P$3") (pintype "passive"))
      (node (ref "R206") (pin "P$2") (pinfunction "2_P$2") (pintype "passive"))
      (node (ref "S4RX") (pin "P$1") (pinfunction "P$1_P$1") (pintype "passive"))
    )
    (net (code "214") (name "SERIAL4_TX") (class "Default")
      (node (ref "J204") (pin "P$2") (pinfunction "2_P$2") (pintype "passive"))
      (node (ref "R213") (pin "P$2") (pinfunction "2_P$2") (pintype "passive"))
      (node (ref "S4TX") (pin "P$1") (pinfunction "P$1_P$1") (pintype "passive"))
    )
    (net (code "215") (name "SERIAL5_RX") (class "Default")
      (node (ref "J204") (pin "P$5") (pinfunction "5_P$5") (pintype "passive"))
      (node (ref "R205") (pin "P$2") (pinfunction "2_P$2") (pintype "passive"))
      (node (ref "S5_RX") (pin "P$1") (pinfunction "P$1_P$1") (pintype "passive"))
    )
    (net (code "216") (name "SERIAL5_TX") (class "Default")
      (node (ref "J204") (pin "P$4") (pinfunction "4_P$4") (pintype "passive"))
      (node (ref "R212") (pin "P$2") (pinfunction "2_P$2") (pintype "passive"))
      (node (ref "S5_TX") (pin "P$1") (pinfunction "P$1_P$1") (pintype "passive"))
    )
    (net (code "217") (name "SERIAL_FMU_TO_IO") (class "Default")
      (node (ref "R804") (pin "P$2") (pinfunction "2_P$2") (pintype "passive"))
      (node (ref "U101") (pin "63") (pinfunction "PC6_63") (pintype "bidirectional"))
    )
    (net (code "218") (name "SERIAL_IO_TO_FMU") (class "Default")
      (node (ref "R803") (pin "P$2") (pinfunction "2_P$2") (pintype "passive"))
      (node (ref "U101") (pin "64") (pinfunction "PC7_64") (pintype "bidirectional"))
    )
    (net (code "219") (name "SPI_EXT_MISO") (class "Default")
      (node (ref "J403") (pin "P$3") (pinfunction "3_P$3") (pintype "passive"))
      (node (ref "U101") (pin "4") (pinfunction "PE5_4") (pintype "bidirectional"))
    )
    (net (code "220") (name "SPI_EXT_MOSI") (class "Default")
      (node (ref "J403") (pin "P$4") (pinfunction "4_P$4") (pintype "passive"))
      (node (ref "U101") (pin "5") (pinfunction "PE6_5") (pintype "bidirectional"))
    )
    (net (code "221") (name "SPI_EXT_SCK") (class "Default")
      (node (ref "J403") (pin "P$2") (pinfunction "2_P$2") (pintype "passive"))
      (node (ref "U101") (pin "1") (pinfunction "PE2_1") (pintype "bidirectional"))
    )
    (net (code "222") (name "SPI_INT_MISO") (class "Default")
      (node (ref "U$1") (pin "9") (pinfunction "S_9") (pintype "passive"))
      (node (ref "U$501") (pin "7") (pinfunction "SDO/SA0_7") (pintype "bidirectional"))
      (node (ref "U101") (pin "31") (pinfunction "PA6_31") (pintype "bidirectional"))
      (node (ref "U501") (pin "4") (pinfunction "SDO/SA0_4") (pintype "bidirectional"))
      (node (ref "U502") (pin "4") (pinfunction "SDO/SA0_4") (pintype "bidirectional"))
      (node (ref "U503") (pin "6") (pinfunction "SDO_6") (pintype "bidirectional"))
    )
    (net (code "223") (name "SPI_INT_MOSI") (class "Default")
      (node (ref "U$1") (pin "8") (pinfunction "S_8") (pintype "passive"))
      (node (ref "U$501") (pin "6") (pinfunction "SDA/SDI/SDO_6") (pintype "bidirectional"))
      (node (ref "U101") (pin "32") (pinfunction "PA7_32") (pintype "bidirectional"))
      (node (ref "U501") (pin "3") (pinfunction "SDA/SDI/SDO_3") (pintype "bidirectional"))
      (node (ref "U502") (pin "3") (pinfunction "SDA/SDI/SDO_3") (pintype "bidirectional"))
      (node (ref "U503") (pin "7") (pinfunction "SDI/SDA_7") (pintype "bidirectional"))
    )
    (net (code "224") (name "SPI_INT_SCK") (class "Default")
      (node (ref "U$1") (pin "10") (pinfunction "S_10") (pintype "passive"))
      (node (ref "U$501") (pin "4") (pinfunction "SCL/SPC_4") (pintype "bidirectional"))
      (node (ref "U101") (pin "30") (pinfunction "PA5_30") (pintype "bidirectional"))
      (node (ref "U501") (pin "2") (pinfunction "SCL/SPC_2") (pintype "input"))
      (node (ref "U502") (pin "2") (pinfunction "SCL/SPC_2") (pintype "bidirectional"))
      (node (ref "U503") (pin "8") (pinfunction "SCLK_8") (pintype "bidirectional"))
    )
    (net (code "225") (name "VBAT") (class "Default")
      (node (ref "B601") (pin "1") (pinfunction "POS_1") (pintype "bidirectional"))
      (node (ref "R608") (pin "P$1") (pinfunction "1_P$1") (pintype "passive"))
      (node (ref "U101") (pin "6") (pinfunction "VBAT_6") (pintype "power_in"))
      (node (ref "U801") (pin "1") (pinfunction "VBAT_1") (pintype "power_in"))
    )
    (net (code "226") (name "VBUS") (class "Default")
      (node (ref "J301") (pin "VBUS") (pinfunction "1_VBUS") (pintype "power_in"))
      (node (ref "J302") (pin "P$1") (pinfunction "1_P$1") (pintype "passive"))
      (node (ref "R6") (pin "P$1") (pinfunction "1_P$1") (pintype "passive"))
      (node (ref "U$2") (pin "P$19") (pinfunction "V3_P$19") (pintype "bidirectional"))
      (node (ref "U$301") (pin "5") (pinfunction "VBUS_5") (pintype "bidirectional"))
      (node (ref "U$5") (pin "P$7") (pinfunction "D_P$7") (pintype "passive"))
      (node (ref "U$5") (pin "P$8") (pinfunction "D_P$8") (pintype "passive"))
      (node (ref "U101") (pin "68") (pinfunction "PA9_68") (pintype "bidirectional"))
    )
    (net (code "227") (name "VDD_3V3_SENSORS") (class "Default")
      (node (ref "C501") (pin "P$1") (pinfunction "1_P$1") (pintype "passive"))
      (node (ref "C502") (pin "P$1") (pinfunction "1_P$1") (pintype "passive"))
      (node (ref "C503") (pin "P$1") (pinfunction "1_P$1") (pintype "passive"))
      (node (ref "C506") (pin "P$1") (pinfunction "1_P$1") (pintype "passive"))
      (node (ref "C507") (pin "P$1") (pinfunction "1_P$1") (pintype "passive"))
      (node (ref "C508") (pin "P$1") (pinfunction "1_P$1") (pintype "passive"))
      (node (ref "C605") (pin "P$1") (pinfunction "1_P$1") (pintype "passive"))
      (node (ref "U$1") (pin "1") (pinfunction "S_1") (pintype "passive"))
      (node (ref "U$501") (pin "1") (pinfunction "VDD_IO_1") (pintype "bidirectional"))
      (node (ref "U$501") (pin "14") (pinfunction "VDD_14") (pintype "bidirectional"))
      (node (ref "U$605") (pin "8") (pinfunction "VOUT1_8") (pintype "bidirectional"))
      (node (ref "U501") (pin "1") (pinfunction "VDD_IO_1") (pintype "bidirectional"))
      (node (ref "U501") (pin "15") (pinfunction "RES_P15_VDD_15") (pintype "bidirectional"))
      (node (ref "U501") (pin "16") (pinfunction "VDD_16") (pintype "bidirectional"))
      (node (ref "U502") (pin "1") (pinfunction "VDD_IO_1") (pintype "bidirectional"))
      (node (ref "U502") (pin "15") (pinfunction "VDD_15") (pintype "bidirectional"))
      (node (ref "U502") (pin "16") (pinfunction "VDD_16") (pintype "bidirectional"))
      (node (ref "U503") (pin "1") (pinfunction "VDD_1") (pintype "bidirectional"))
      (node (ref "VDDA_3V1101") (pin "P$1") (pinfunction "P$1_P$1") (pintype "passive"))
    )
    (net (code "228") (name "VDD_3V3_SENSORS_EN") (class "Default")
      (node (ref "R603") (pin "P$1") (pinfunction "1_P$1") (pintype "passive"))
      (node (ref "U$605") (pin "5") (pinfunction "EN1_5") (pintype "bidirectional"))
      (node (ref "U101") (pin "2") (pinfunction "PE3_2") (pintype "bidirectional"))
    )
    (net (code "229") (name "VDD_3V3_SPEKTRUM") (class "Default")
      (node (ref "C1003") (pin "P$1") (pinfunction "1_P$1") (pintype "passive"))
      (node (ref "J801") (pin "P$1") (pinfunction "P$1_P$1") (pintype "bidirectional"))
      (node (ref "U$1002") (pin "8") (pinfunction "VOUT1_8") (pintype "bidirectional"))
      (node (ref "U$801") (pin "C") (pinfunction "C_C") (pintype "passive"))
    )
    (net (code "230") (name "VDD_3V3_SPEKTRUM_EN") (class "Default")
      (node (ref "R1002") (pin "P$2") (pinfunction "2_P$2") (pintype "passive"))
      (node (ref "U$1002") (pin "5") (pinfunction "EN1_5") (pintype "bidirectional"))
      (node (ref "U801") (pin "2") (pinfunction "PC13_2") (pintype "bidirectional"))
    )
    (net (code "231") (name "VDD_5V_BRICK") (class "Default")
      (node (ref "J601") (pin "P$1") (pinfunction "1_P$1") (pintype "passive"))
      (node (ref "J601") (pin "P$2") (pinfunction "2_P$2") (pintype "passive"))
      (node (ref "R1") (pin "P$1") (pinfunction "1_P$1") (pintype "passive"))
      (node (ref "U$2") (pin "P$21") (pinfunction "V1_P$21") (pintype "bidirectional"))
      (node (ref "U$3") (pin "P$7") (pinfunction "D_P$7") (pintype "passive"))
      (node (ref "U$3") (pin "P$8") (pinfunction "D_P$8") (pintype "passive"))
      (node (ref "VDD_5V_BRICK") (pin "P$1") (pinfunction "P$1_P$1") (pintype "passive"))
    )
    (net (code "232") (name "VDD_5V_HIPOWER") (class "Default")
      (node (ref "L201") (pin "P$1") (pinfunction "P$1_P$1") (pintype "bidirectional"))
      (node (ref "U$602") (pin "8") (pinfunction "OUT_8") (pintype "bidirectional"))
    )
    (net (code "233") (name "VDD_5V_IN") (class "Default")
      (node (ref "C702") (pin "P$1") (pinfunction "1_P$1") (pintype "passive"))
      (node (ref "F2") (pin "1") (pinfunction "1_1") (pintype "bidirectional"))
      (node (ref "L603") (pin "P$1") (pinfunction "P$1_P$1") (pintype "bidirectional"))
      (node (ref "L701") (pin "P$1") (pinfunction "1_P$1") (pintype "passive"))
      (node (ref "LED701") (pin "A") (pinfunction "A_A") (pintype "passive"))
      (node (ref "LED704") (pin "A") (pinfunction "A_A") (pintype "passive"))
      (node (ref "R609") (pin "P$2") (pinfunction "2_P$2") (pintype "passive"))
      (node (ref "U$2") (pin "P$12") (pinfunction "VOUT_P$12") (pintype "bidirectional"))
      (node (ref "U$3") (pin "P$5") (pinfunction "D_P$5") (pintype "passive"))
      (node (ref "U$3") (pin "P$6") (pinfunction "D_P$6") (pintype "passive"))
      (node (ref "U$4") (pin "P$5") (pinfunction "D_P$5") (pintype "passive"))
      (node (ref "U$4") (pin "P$6") (pinfunction "D_P$6") (pintype "passive"))
      (node (ref "U$5") (pin "P$5") (pinfunction "D_P$5") (pintype "passive"))
      (node (ref "U$5") (pin "P$6") (pinfunction "D_P$6") (pintype "passive"))
      (node (ref "U$602") (pin "1") (pinfunction "IN_1") (pintype "bidirectional"))
      (node (ref "U$604") (pin "1") (pinfunction "IN_1") (pintype "bidirectional"))
      (node (ref "U702") (pin "3") (pinfunction "VIN_3") (pintype "power_in"))
      (node (ref "U703") (pin "A1") (pinfunction "A_A1") (pintype "passive"))
      (node (ref "U703") (pin "A2") (pinfunction "A_A2") (pintype "passive"))
      (node (ref "U703") (pin "A3") (pinfunction "A_A3") (pintype "passive"))
    )
    (net (code "234") (name "VDD_5V_PERIPH") (class "Default")
      (node (ref "L202") (pin "P$1") (pinfunction "P$1_P$1") (pintype "bidirectional"))
      (node (ref "L203") (pin "P$1") (pinfunction "P$1_P$1") (pintype "bidirectional"))
      (node (ref "L401") (pin "P$1") (pinfunction "P$1_P$1") (pintype "bidirectional"))
      (node (ref "L402") (pin "P$1") (pinfunction "P$1_P$1") (pintype "bidirectional"))
      (node (ref "L403") (pin "P$1") (pinfunction "P$1_P$1") (pintype "bidirectional"))
      (node (ref "L404") (pin "P$1") (pinfunction "P$1_P$1") (pintype "bidirectional"))
      (node (ref "U$604") (pin "8") (pinfunction "OUT_8") (pintype "bidirectional"))
    )
    (net (code "235") (name "VDD_5V_SENS") (class "Default")
      (node (ref "R609") (pin "P$1") (pinfunction "1_P$1") (pintype "passive"))
      (node (ref "R610") (pin "P$1") (pinfunction "1_P$1") (pintype "passive"))
      (node (ref "U101") (pin "29") (pinfunction "PA4_29") (pintype "bidirectional"))
    )
    (net (code "236") (name "VDD_SERVO") (class "Default")
      (node (ref "D1") (pin "ANODE") (pinfunction "A_ANODE") (pintype "passive"))
      (node (ref "J901") (pin "11") (pinfunction "S_11") (pintype "passive"))
      (node (ref "J901") (pin "14") (pinfunction "S_14") (pintype "passive"))
      (node (ref "J901") (pin "17") (pinfunction "S_17") (pintype "passive"))
      (node (ref "J901") (pin "20") (pinfunction "S_20") (pintype "passive"))
      (node (ref "J901") (pin "23") (pinfunction "S_23") (pintype "passive"))
      (node (ref "J901") (pin "26") (pinfunction "S_26") (pintype "passive"))
      (node (ref "J901") (pin "29") (pinfunction "S_29") (pintype "passive"))
      (node (ref "J901") (pin "32") (pinfunction "S_32") (pintype "passive"))
      (node (ref "J901") (pin "35") (pinfunction "S_35") (pintype "passive"))
      (node (ref "J901") (pin "38") (pinfunction "S_38") (pintype "passive"))
      (node (ref "J901") (pin "41") (pinfunction "S_41") (pintype "passive"))
      (node (ref "J901") (pin "44") (pinfunction "S_44") (pintype "passive"))
      (node (ref "J901") (pin "47") (pinfunction "S_47") (pintype "passive"))
      (node (ref "J901") (pin "5") (pinfunction "S_5") (pintype "passive"))
      (node (ref "J901") (pin "8") (pinfunction "S_8") (pintype "passive"))
      (node (ref "R9") (pin "P$1") (pinfunction "1_P$1") (pintype "passive"))
      (node (ref "R922") (pin "P$2") (pinfunction "2_P$2") (pintype "passive"))
      (node (ref "U$2") (pin "P$20") (pinfunction "V2_P$20") (pintype "bidirectional"))
      (node (ref "U$4") (pin "P$7") (pinfunction "D_P$7") (pintype "passive"))
      (node (ref "U$4") (pin "P$8") (pinfunction "D_P$8") (pintype "passive"))
    )
    (net (code "237") (name "VDD_SERVO_IN") (class "Default")
      (node (ref "L901") (pin "P$2") (pinfunction "P$2_P$2") (pintype "bidirectional"))
      (node (ref "U$1001") (pin "1") (pinfunction "IN_1") (pintype "bidirectional"))
    )
    (net (code "238") (name "VDD_SERVO_SENS") (class "Default")
      (node (ref "R918") (pin "P$1") (pinfunction "1_P$1") (pintype "passive"))
      (node (ref "R919") (pin "P$2") (pinfunction "2_P$2") (pintype "passive"))
      (node (ref "U801") (pin "14") (pinfunction "PA4_14") (pintype "bidirectional"))
    )
    (net (code "239") (name "unconnected-(J301-4-PadID)") (class "Default")
      (node (ref "J301") (pin "ID") (pinfunction "4_ID") (pintype "passive"))
    )
    (net (code "240") (name "unconnected-(JX301A-S-Pad10)") (class "Default")
      (node (ref "JX301") (pin "10") (pinfunction "S_10") (pintype "passive"))
    )
    (net (code "241") (name "unconnected-(JX301F-S-Pad8)") (class "Default")
      (node (ref "JX301") (pin "8") (pinfunction "S_8") (pintype "passive"))
    )
    (net (code "242") (name "unconnected-(JX802A-S-Pad10)") (class "Default")
      (node (ref "JX802") (pin "10") (pinfunction "S_10") (pintype "passive"))
    )
    (net (code "243") (name "unconnected-(JX802F-S-Pad8)") (class "Default")
      (node (ref "JX802") (pin "8") (pinfunction "S_8") (pintype "passive"))
    )
    (net (code "244") (name "unconnected-(U$2-CAS-PadP$11)") (class "Default")
      (node (ref "U$2") (pin "P$11") (pinfunction "CAS_P$11") (pintype "bidirectional"))
    )
    (net (code "245") (name "unconnected-(U$2-EN-PadP$22)") (class "Default")
      (node (ref "U$2") (pin "P$22") (pinfunction "EN_P$22") (pintype "bidirectional"))
    )
    (net (code "246") (name "unconnected-(U$2-~{SHDN}-PadP$23)") (class "Default")
      (node (ref "U$2") (pin "P$23") (pinfunction "~{SHDN}_P$23") (pintype "bidirectional"))
    )
    (net (code "247") (name "unconnected-(U101I-PC0-Pad15)") (class "Default")
      (node (ref "U101") (pin "15") (pinfunction "PC0_15") (pintype "bidirectional"))
    )
    (net (code "248") (name "unconnected-(U101I-PC1-Pad16)") (class "Default")
      (node (ref "U101") (pin "16") (pinfunction "PC1_16") (pintype "bidirectional"))
    )
    (net (code "249") (name "unconnected-(U101I-PC2-Pad17)") (class "Default")
      (node (ref "U101") (pin "17") (pinfunction "PC2_17") (pintype "bidirectional"))
    )
    (net (code "250") (name "unconnected-(U101J-PD15-Pad62)") (class "Default")
      (node (ref "U101") (pin "62") (pinfunction "PD15_62") (pintype "bidirectional"))
    )
    (net (code "251") (name "unconnected-(U202-A1-Pad1)") (class "Default")
      (node (ref "U202") (pin "1") (pinfunction "A1_1") (pintype "bidirectional"))
    )
    (net (code "252") (name "unconnected-(U202-A2-Pad3)") (class "Default")
      (node (ref "U202") (pin "3") (pinfunction "A2_3") (pintype "bidirectional"))
    )
    (net (code "253") (name "unconnected-(U202-B1-Pad20)") (class "Default")
      (node (ref "U202") (pin "20") (pinfunction "B1_20") (pintype "bidirectional"))
    )
    (net (code "254") (name "unconnected-(U202-B2-Pad18)") (class "Default")
      (node (ref "U202") (pin "18") (pinfunction "B2_18") (pintype "bidirectional"))
    )
    (net (code "255") (name "unconnected-(U501-INT1-Pad7)") (class "Default")
      (node (ref "U501") (pin "7") (pinfunction "INT1_7") (pintype "output"))
    )
    (net (code "256") (name "unconnected-(U502-DEN-Pad8)") (class "Default")
      (node (ref "U502") (pin "8") (pinfunction "DEN_8") (pintype "bidirectional"))
    )
    (net (code "257") (name "unconnected-(U502-INT1-Pad7)") (class "Default")
      (node (ref "U502") (pin "7") (pinfunction "INT1_7") (pintype "bidirectional"))
    )
    (net (code "258") (name "unconnected-(U503-CSB1-Pad4)") (class "Default")
      (node (ref "U503") (pin "4") (pinfunction "CSB1_4") (pintype "bidirectional"))
    )
    (net (code "259") (name "unconnected-(U801B-PA11-Pad32)") (class "Default")
      (node (ref "U801") (pin "32") (pinfunction "PA11_32") (pintype "bidirectional"))
    )
    (net (code "260") (name "unconnected-(U801D-PB12-Pad25)") (class "Default")
      (node (ref "U801") (pin "25") (pinfunction "PB12_25") (pintype "bidirectional"))
    )
    (net (code "261") (name "unconnected-(U801E-PB6-Pad42)") (class "Default")
      (node (ref "U801") (pin "42") (pinfunction "PB6_42") (pintype "bidirectional"))
    )
    (net (code "262") (name "unconnected-(U801E-PB7-Pad43)") (class "Default")
      (node (ref "U801") (pin "43") (pinfunction "PB7_43") (pintype "bidirectional"))
    )
    (net (code "263") (name "unconnected-(U801F-PC14-Pad3)") (class "Default")
      (node (ref "U801") (pin "3") (pinfunction "PC14_3") (pintype "bidirectional"))
    )
    (net (code "264") (name "unconnected-(U801F-PC15-Pad4)") (class "Default")
      (node (ref "U801") (pin "4") (pinfunction "PC15_4") (pintype "bidirectional"))
    )
    (net (code "265") (name "unconnected-(U901-A7-Pad8)") (class "Default")
      (node (ref "U901") (pin "8") (pinfunction "A7_8") (pintype "bidirectional"))
    )
    (net (code "266") (name "unconnected-(U901-A8-Pad9)") (class "Default")
      (node (ref "U901") (pin "9") (pinfunction "A8_9") (pintype "bidirectional"))
    )
    (net (code "267") (name "unconnected-(U901-B7-Pad13)") (class "Default")
      (node (ref "U901") (pin "13") (pinfunction "B7_13") (pintype "bidirectional"))
    )
    (net (code "268") (name "unconnected-(U901-B8-Pad12)") (class "Default")
      (node (ref "U901") (pin "12") (pinfunction "B8_12") (pintype "bidirectional"))
    )
    (net (code "269") (name "~{ACCEL_MAG_CS}") (class "Default")
      (node (ref "U$1") (pin "6") (pinfunction "S_6") (pintype "passive"))
      (node (ref "U$501") (pin "8") (pinfunction "CS_8") (pintype "bidirectional"))
      (node (ref "U101") (pin "9") (pinfunction "PC15_9") (pintype "bidirectional"))
    )
    (net (code "270") (name "~{BARO_CS}") (class "Default")
      (node (ref "U101") (pin "88") (pinfunction "PD7_88") (pintype "bidirectional"))
      (node (ref "U503") (pin "5") (pinfunction "CSB2_5") (pintype "bidirectional"))
    )
    (net (code "271") (name "~{FMU-LED_AMBER}") (class "Default")
      (node (ref "R707") (pin "P$1") (pinfunction "1_P$1") (pintype "passive"))
      (node (ref "U101") (pin "43") (pinfunction "PE12_43") (pintype "bidirectional"))
    )
    (net (code "272") (name "~{FRAM_CS}") (class "Default")
      (node (ref "U101") (pin "57") (pinfunction "PD10_57") (pintype "bidirectional"))
      (node (ref "U102") (pin "1") (pinfunction "~{S}_1") (pintype "bidirectional"))
    )
    (net (code "273") (name "~{GYRO_CS}") (class "Default")
      (node (ref "U$1") (pin "7") (pinfunction "S_7") (pintype "passive"))
      (node (ref "U101") (pin "7") (pinfunction "PC13_7") (pintype "bidirectional"))
      (node (ref "U501") (pin "5") (pinfunction "CS_5") (pintype "input"))
      (node (ref "U502") (pin "5") (pinfunction "CS_5") (pintype "bidirectional"))
    )
    (net (code "274") (name "~{IO-LED_AMBER}") (class "Default")
      (node (ref "R709") (pin "P$1") (pinfunction "1_P$1") (pintype "passive"))
      (node (ref "U801") (pin "28") (pinfunction "PB15_28") (pintype "bidirectional"))
    )
    (net (code "275") (name "~{IO-LED_BLUE}") (class "Default")
      (node (ref "R712") (pin "P$1") (pinfunction "1_P$1") (pintype "passive"))
      (node (ref "U801") (pin "27") (pinfunction "PB14_27") (pintype "bidirectional"))
    )
    (net (code "276") (name "~{IO-LED_SAFETY}") (class "Default")
      (node (ref "R710") (pin "P$2") (pinfunction "2_P$2") (pintype "passive"))
      (node (ref "U801") (pin "26") (pinfunction "PB13_26") (pintype "bidirectional"))
    )
    (net (code "277") (name "~{SBUS_OUTPUT_EN}") (class "Default")
      (node (ref "U801") (pin "40") (pinfunction "PB4_40") (pintype "bidirectional"))
      (node (ref "U903") (pin "7") (pinfunction "~{2OE}_7") (pintype "input"))
    )
    (net (code "278") (name "~{SPI_EXT_NSS}") (class "Default")
      (node (ref "J403") (pin "P$5") (pinfunction "5_P$5") (pintype "passive"))
      (node (ref "U101") (pin "3") (pinfunction "PE4_3") (pintype "bidirectional"))
    )
    (net (code "279") (name "~{VBUS_VALID}") (class "Default")
      (node (ref "U$2") (pin "P$9") (pinfunction "~{VALID3}_P$9") (pintype "bidirectional"))
    )
    (net (code "280") (name "~{VDD_5V_HIPOWER_OC}") (class "Default")
      (node (ref "U$602") (pin "4") (pinfunction "~{FAULT}_4") (pintype "bidirectional"))
      (node (ref "U101") (pin "41") (pinfunction "PE10_41") (pintype "bidirectional"))
    )
    (net (code "281") (name "~{VDD_5V_PERIPH_EN}") (class "Default")
      (node (ref "R607") (pin "P$1") (pinfunction "1_P$1") (pintype "passive"))
      (node (ref "U$602") (pin "5") (pinfunction "~{CE}_5") (pintype "bidirectional"))
      (node (ref "U$604") (pin "5") (pinfunction "~{CE}_5") (pintype "bidirectional"))
      (node (ref "U101") (pin "67") (pinfunction "PA8_67") (pintype "bidirectional"))
    )
    (net (code "282") (name "~{VDD_5V_PERIPH_OC}") (class "Default")
      (node (ref "U$604") (pin "4") (pinfunction "~{FAULT}_4") (pintype "bidirectional"))
      (node (ref "U101") (pin "46") (pinfunction "PE15_46") (pintype "bidirectional"))
    )
    (net (code "283") (name "~{VDD_BRICK_VALID}") (class "Default")
      (node (ref "U$2") (pin "P$7") (pinfunction "~{VALID1}_P$7") (pintype "bidirectional"))
      (node (ref "U101") (pin "91") (pinfunction "PB5_91") (pintype "bidirectional"))
    )
    (net (code "284") (name "~{VDD_SERVO_VALID}") (class "Default")
      (node (ref "U$2") (pin "P$8") (pinfunction "~{VALID2}_P$8") (pintype "bidirectional"))
      (node (ref "U101") (pin "93") (pinfunction "PB7_93") (pintype "bidirectional"))
    )
  )
)
